# Sprite_Sail_1mx1m.net
KiCad netlist of a schematic drawn in EAGLE
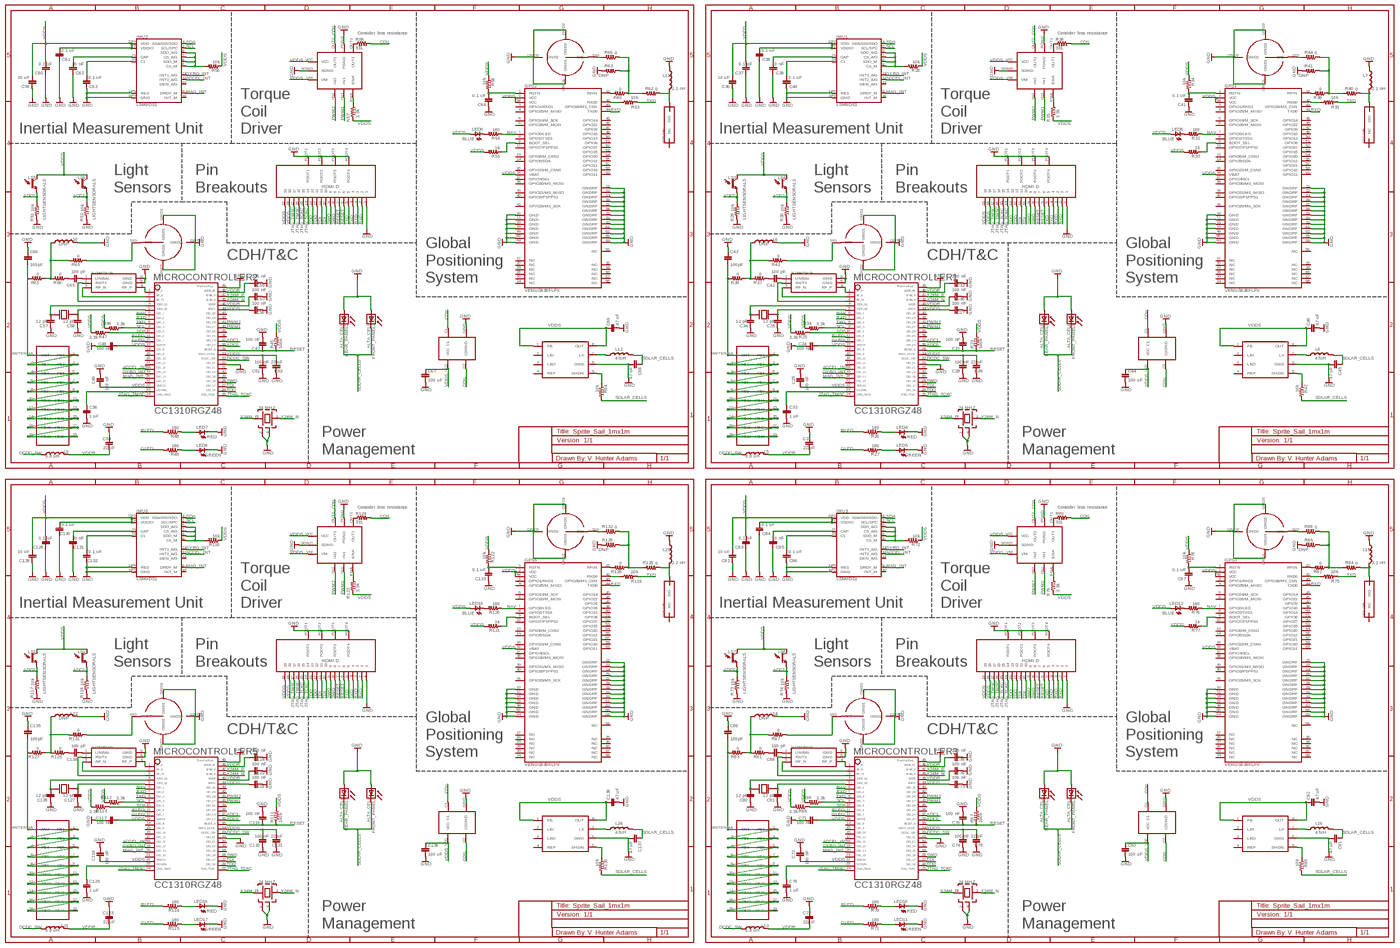
[diagram p0: schematic, sheet 1, overview]
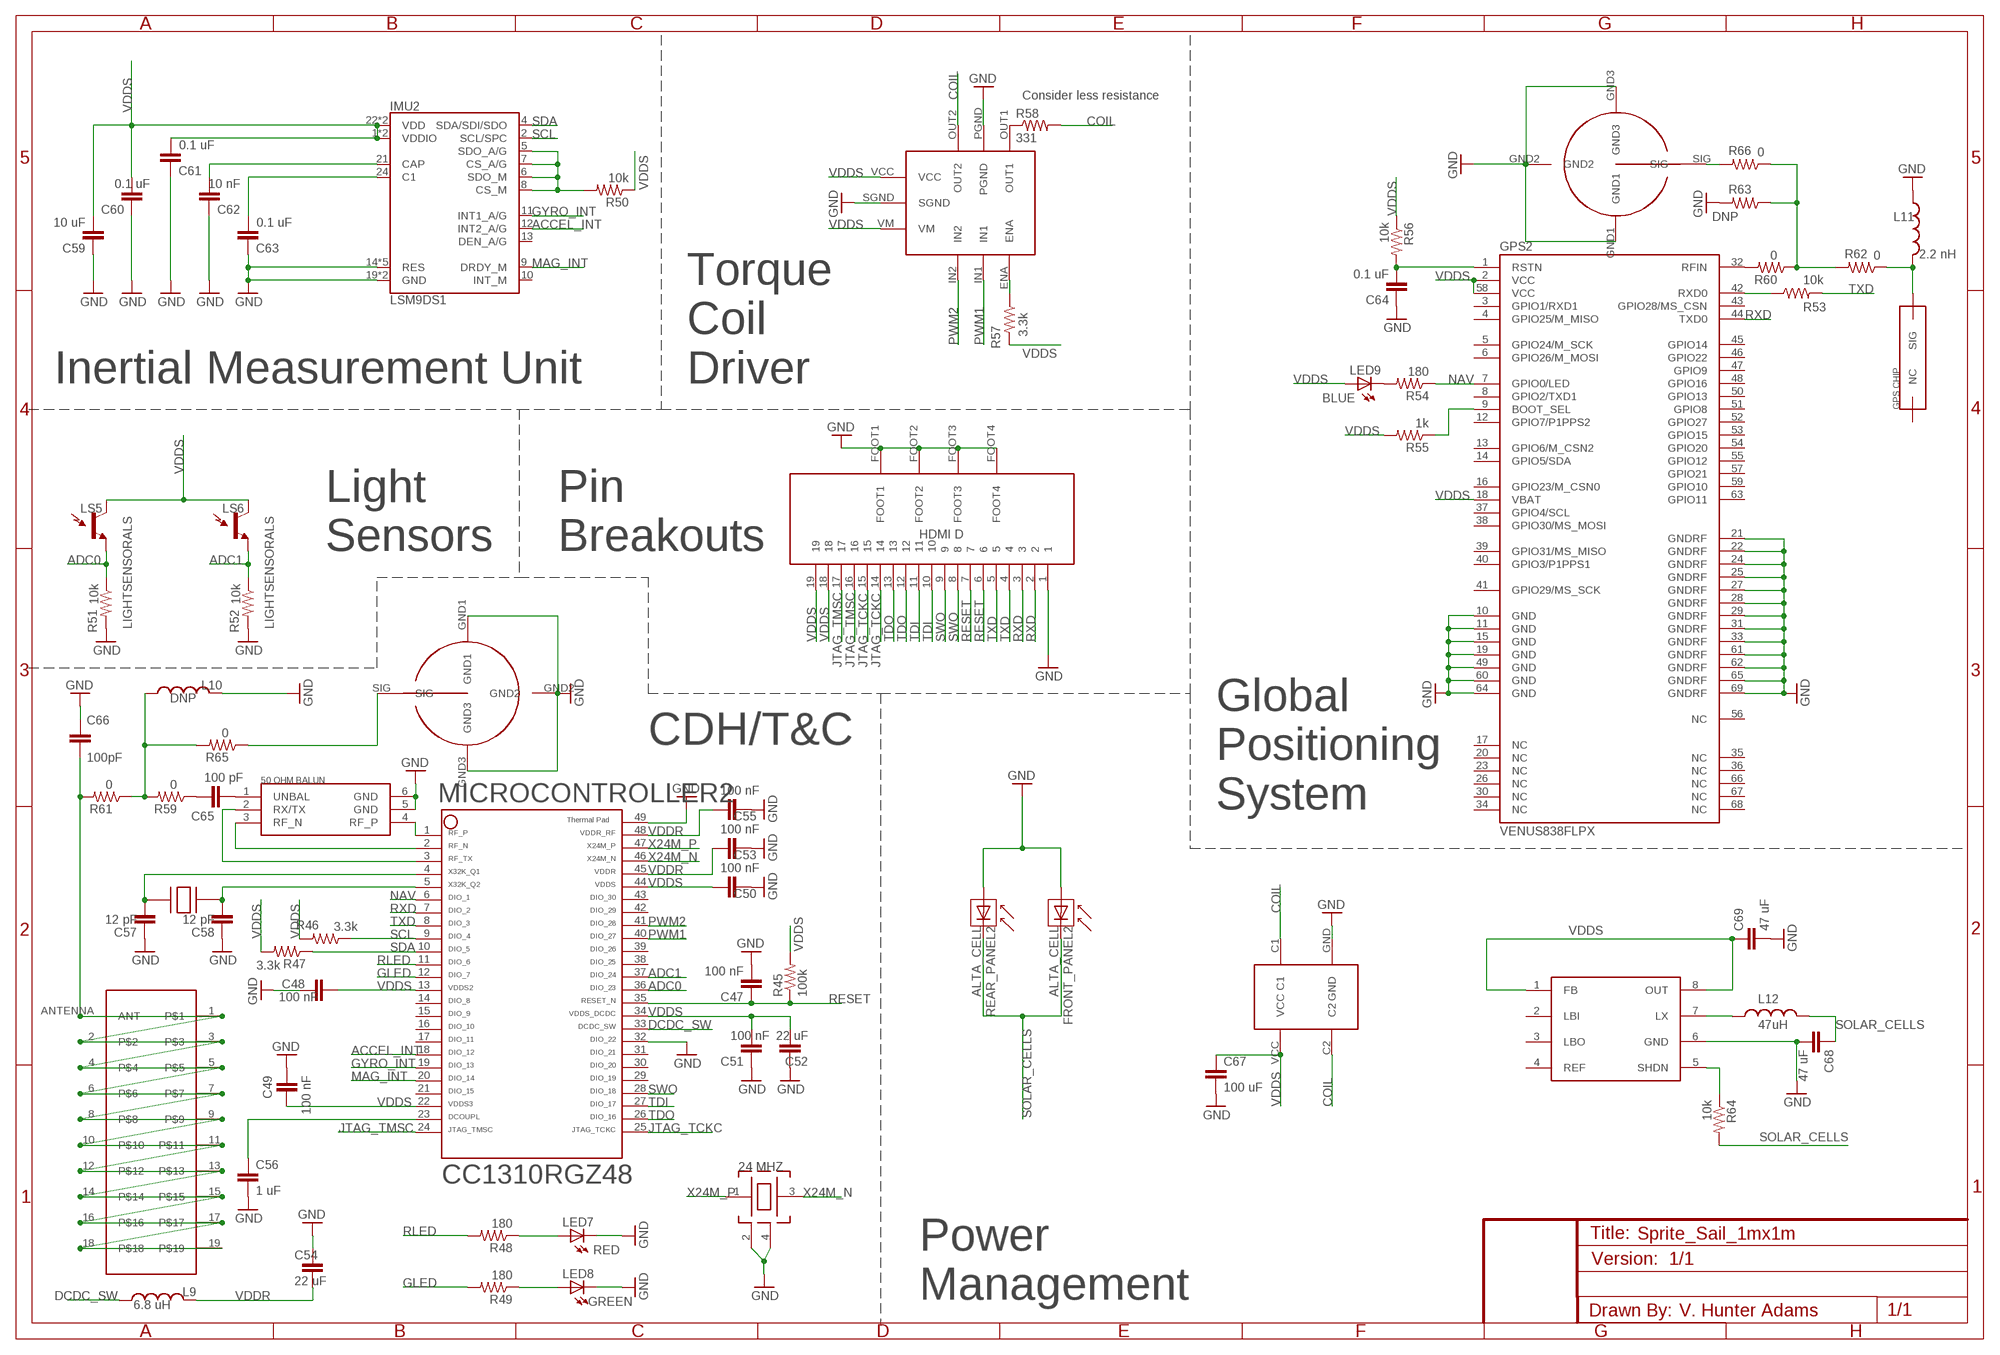
[diagram p1: schematic, sheet 1, part 1 of 4]
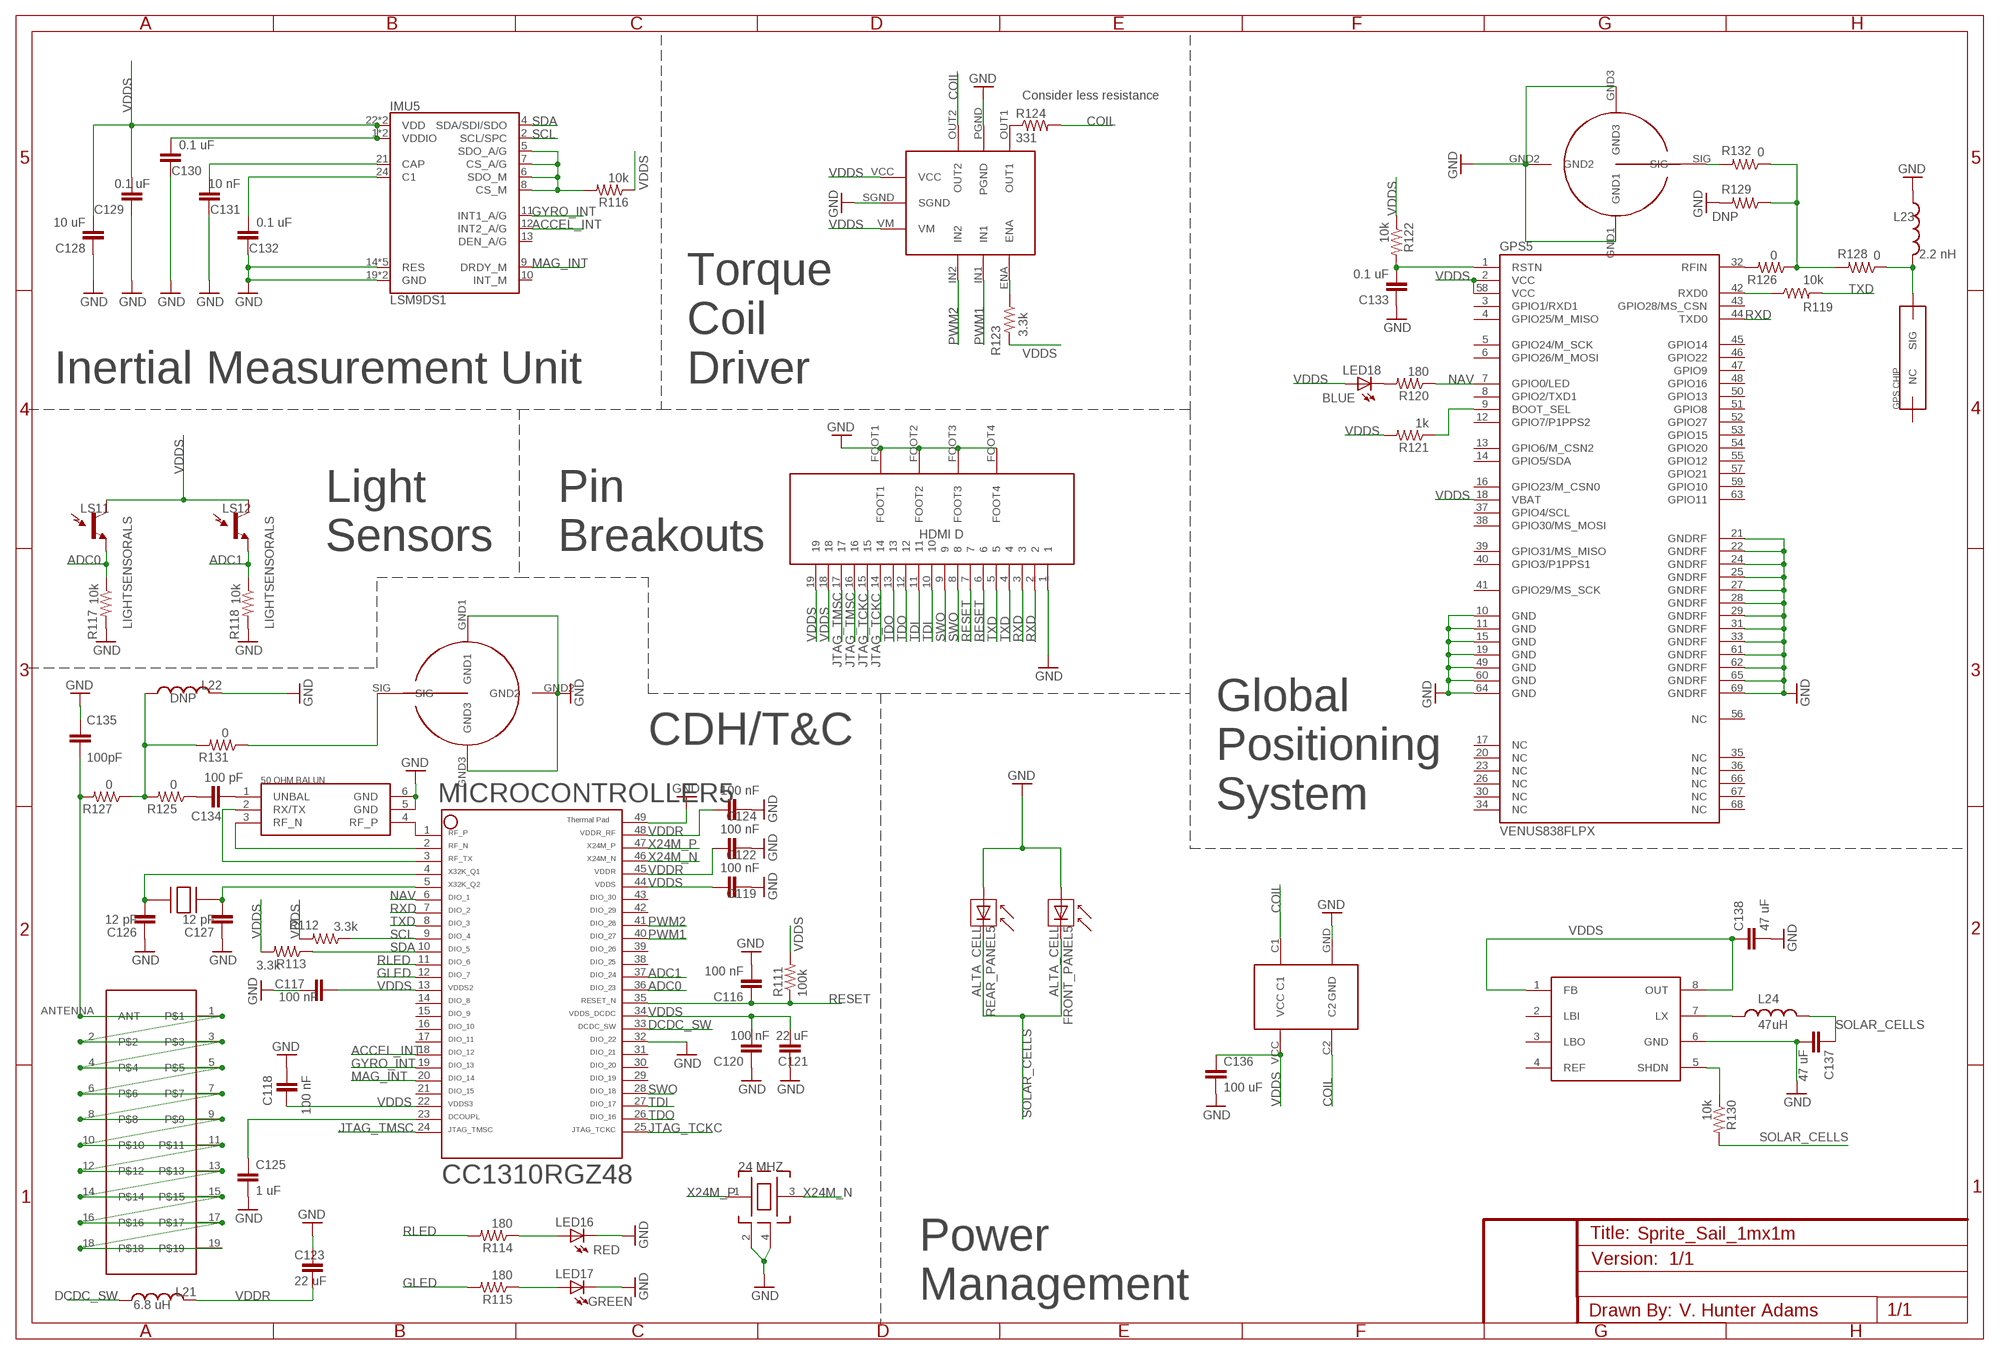
[diagram p2: schematic, sheet 1, part 2 of 4]
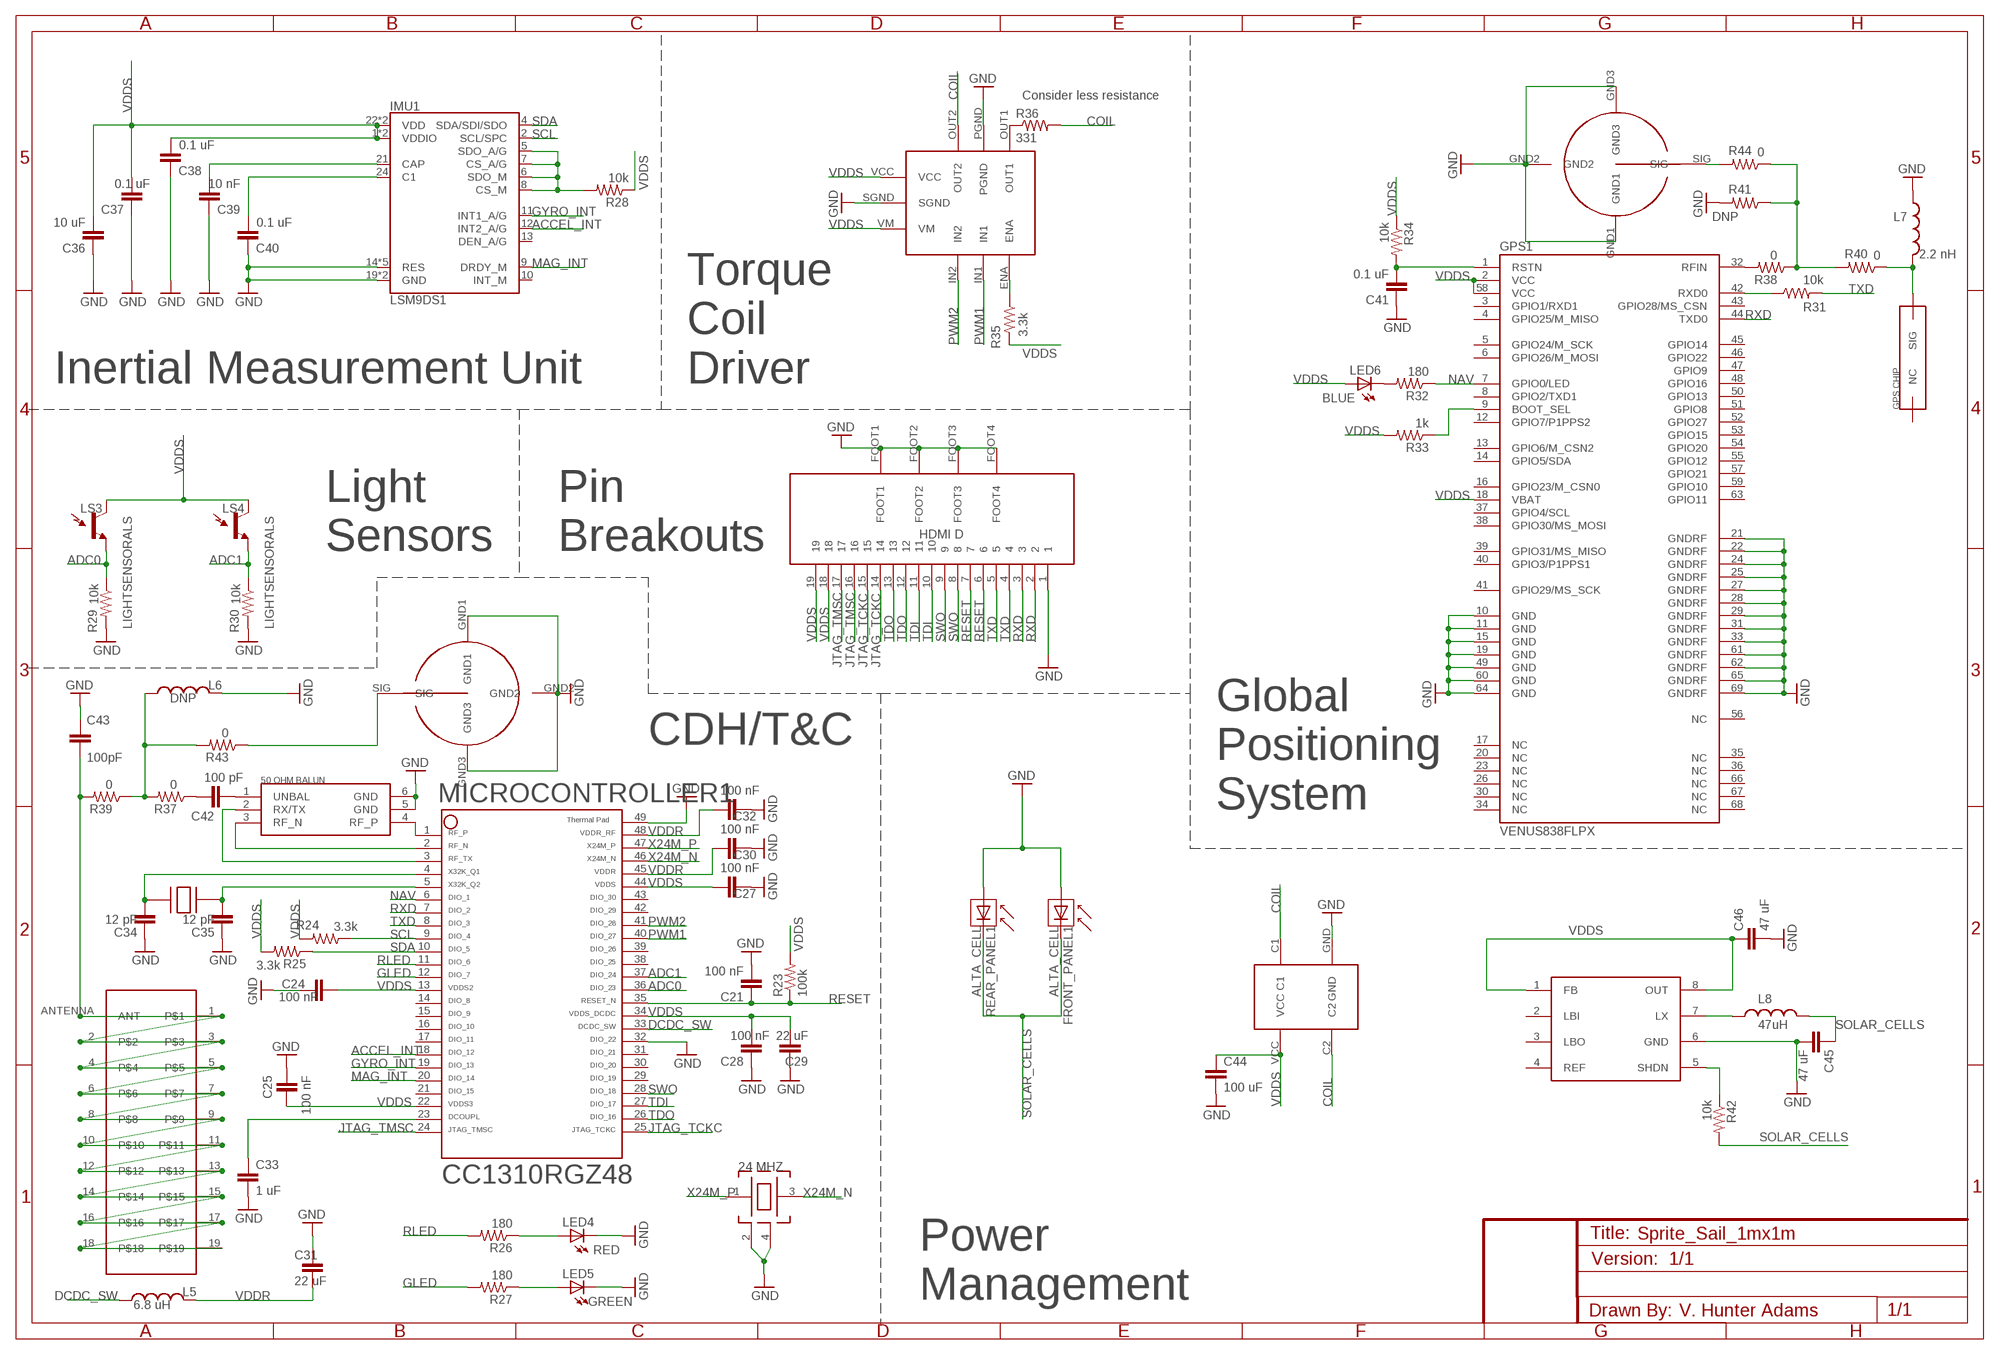
[diagram p3: schematic, sheet 1, part 3 of 4]
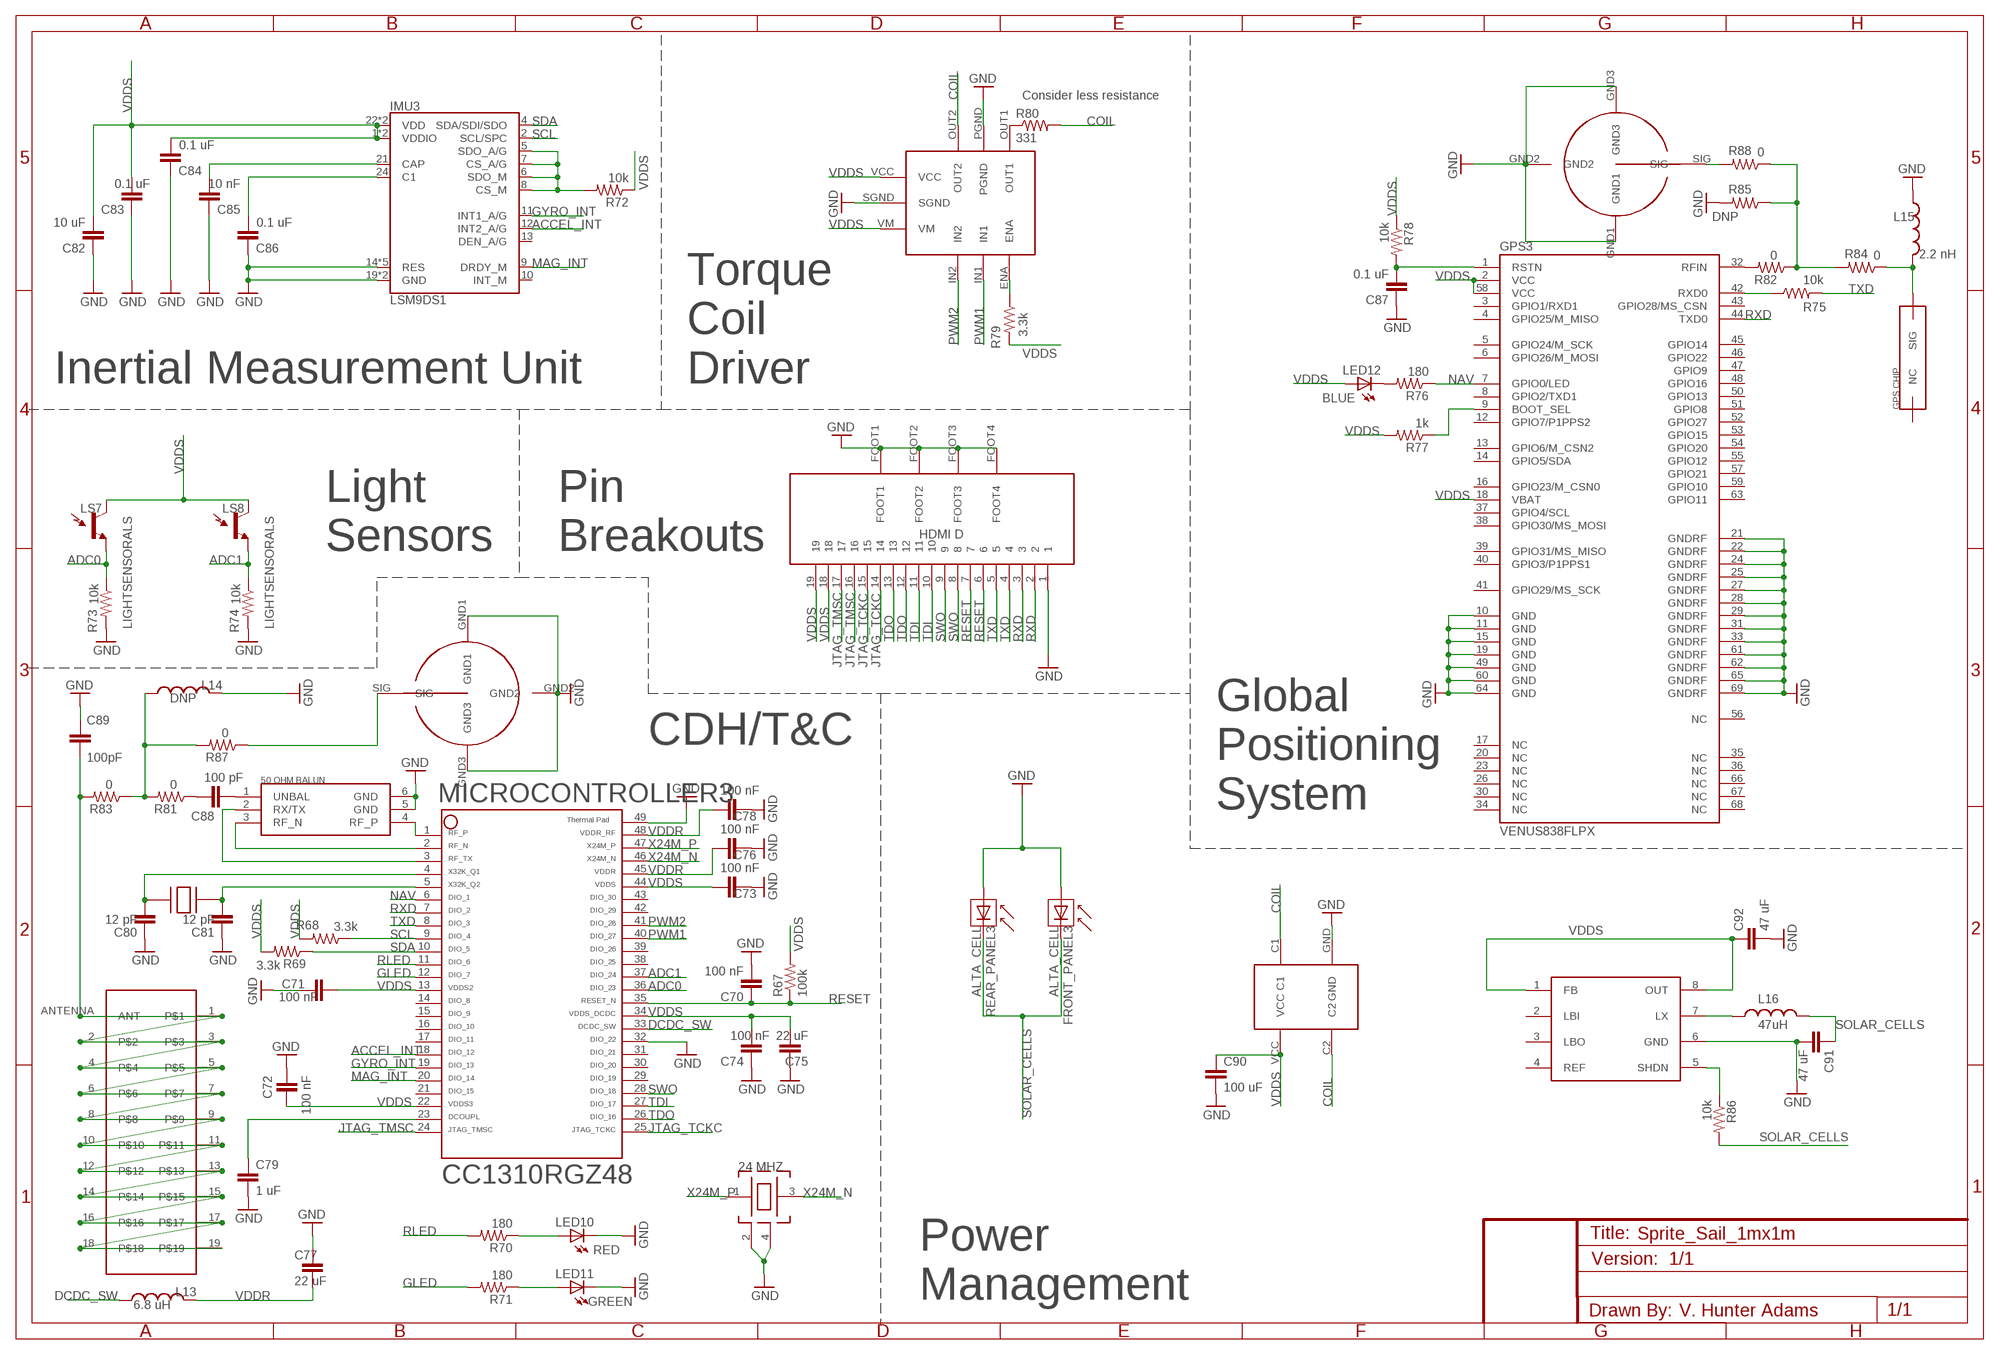
[diagram p4: schematic, sheet 1, part 4 of 4]

(export (version "E")
  (design (tool "Eeschema 10.0.6"))
  (components
    (comp (ref "32.1")
      (value "FC-135")
      (footprint "eagle-import:FC-135")
      (libsource (lib "eagle-import") (part "FC-135"))
    )
    (comp (ref "32.2")
      (value "FC-135")
      (footprint "eagle-import:FC-135")
      (libsource (lib "eagle-import") (part "FC-135"))
    )
    (comp (ref "32.3")
      (value "FC-135")
      (footprint "eagle-import:FC-135")
      (libsource (lib "eagle-import") (part "FC-135"))
    )
    (comp (ref "32.5")
      (value "FC-135")
      (footprint "eagle-import:FC-135")
      (libsource (lib "eagle-import") (part "FC-135"))
    )
    (comp (ref "BALUN1")
      (value "JOHANSON_BALUN")
      (footprint "eagle-import:JOHANSON_BALUN")
      (libsource (lib "eagle-import") (part "JOHANSON_BALUN"))
    )
    (comp (ref "BALUN2")
      (value "JOHANSON_BALUN")
      (footprint "eagle-import:JOHANSON_BALUN")
      (libsource (lib "eagle-import") (part "JOHANSON_BALUN"))
    )
    (comp (ref "BALUN3")
      (value "JOHANSON_BALUN")
      (footprint "eagle-import:JOHANSON_BALUN")
      (libsource (lib "eagle-import") (part "JOHANSON_BALUN"))
    )
    (comp (ref "BALUN5")
      (value "JOHANSON_BALUN")
      (footprint "eagle-import:JOHANSON_BALUN")
      (libsource (lib "eagle-import") (part "JOHANSON_BALUN"))
    )
    (comp (ref "C21")
      (value "100 nF")
      (footprint "eagle-import:0402-CAP")
      (libsource (lib "eagle-import") (part "CAP0402-CAP"))
    )
    (comp (ref "C24")
      (value "100 nF")
      (footprint "eagle-import:0402-CAP")
      (libsource (lib "eagle-import") (part "CAP0402-CAP"))
    )
    (comp (ref "C25")
      (value "100 nF")
      (footprint "eagle-import:0402-CAP")
      (libsource (lib "eagle-import") (part "CAP0402-CAP"))
    )
    (comp (ref "C27")
      (value "100 nF")
      (footprint "eagle-import:0402-CAP")
      (libsource (lib "eagle-import") (part "CAP0402-CAP"))
    )
    (comp (ref "C28")
      (value "100 nF")
      (footprint "eagle-import:0402-CAP")
      (libsource (lib "eagle-import") (part "CAP0402-CAP"))
    )
    (comp (ref "C29")
      (value "22 uF")
      (footprint "eagle-import:0402-CAP")
      (libsource (lib "eagle-import") (part "CAP0402-CAP"))
    )
    (comp (ref "C30")
      (value "100 nF")
      (footprint "eagle-import:0402-CAP")
      (libsource (lib "eagle-import") (part "CAP0402-CAP"))
    )
    (comp (ref "C31")
      (value "22 uF")
      (footprint "eagle-import:0402-CAP")
      (libsource (lib "eagle-import") (part "CAP0402-CAP"))
    )
    (comp (ref "C32")
      (value "100 nF")
      (footprint "eagle-import:0402-CAP")
      (libsource (lib "eagle-import") (part "CAP0402-CAP"))
    )
    (comp (ref "C33")
      (value "1 uF")
      (footprint "eagle-import:0402-CAP")
      (libsource (lib "eagle-import") (part "CAP0402-CAP"))
    )
    (comp (ref "C34")
      (value "12 pF")
      (footprint "eagle-import:0402-CAP")
      (libsource (lib "eagle-import") (part "CAP0402-CAP"))
    )
    (comp (ref "C35")
      (value "12 pF")
      (footprint "eagle-import:0402-CAP")
      (libsource (lib "eagle-import") (part "CAP0402-CAP"))
    )
    (comp (ref "C36")
      (value "10 uF")
      (footprint "eagle-import:0402-CAP")
      (libsource (lib "eagle-import") (part "CAP0402-CAP"))
    )
    (comp (ref "C37")
      (value "0.1 uF")
      (footprint "eagle-import:0402-CAP")
      (libsource (lib "eagle-import") (part "CAP0402-CAP"))
    )
    (comp (ref "C38")
      (value "0.1 uF")
      (footprint "eagle-import:0402-CAP")
      (libsource (lib "eagle-import") (part "CAP0402-CAP"))
    )
    (comp (ref "C39")
      (value "10 nF")
      (footprint "eagle-import:0402-CAP")
      (libsource (lib "eagle-import") (part "CAP0402-CAP"))
    )
    (comp (ref "C40")
      (value "0.1 uF")
      (footprint "eagle-import:0402-CAP")
      (libsource (lib "eagle-import") (part "CAP0402-CAP"))
    )
    (comp (ref "C41")
      (value "0.1 uF")
      (footprint "eagle-import:0402-CAP")
      (libsource (lib "eagle-import") (part "CAP0402-CAP"))
    )
    (comp (ref "C42")
      (value "100 pF")
      (footprint "eagle-import:0402-CAP")
      (libsource (lib "eagle-import") (part "CAP0402-CAP"))
    )
    (comp (ref "C43")
      (value "100pF")
      (footprint "eagle-import:0603-CAP")
      (libsource (lib "eagle-import") (part "CAP0603-CAP"))
    )
    (comp (ref "C44")
      (value "100 uF")
      (footprint "eagle-import:0805")
      (libsource (lib "eagle-import") (part "CAP0805"))
    )
    (comp (ref "C45")
      (value "47 uF")
      (footprint "eagle-import:0805")
      (libsource (lib "eagle-import") (part "CAP0805"))
    )
    (comp (ref "C46")
      (value "47 uF")
      (footprint "eagle-import:0805")
      (libsource (lib "eagle-import") (part "CAP0805"))
    )
    (comp (ref "C47")
      (value "100 nF")
      (footprint "eagle-import:0402-CAP")
      (libsource (lib "eagle-import") (part "CAP0402-CAP"))
    )
    (comp (ref "C48")
      (value "100 nF")
      (footprint "eagle-import:0402-CAP")
      (libsource (lib "eagle-import") (part "CAP0402-CAP"))
    )
    (comp (ref "C49")
      (value "100 nF")
      (footprint "eagle-import:0402-CAP")
      (libsource (lib "eagle-import") (part "CAP0402-CAP"))
    )
    (comp (ref "C50")
      (value "100 nF")
      (footprint "eagle-import:0402-CAP")
      (libsource (lib "eagle-import") (part "CAP0402-CAP"))
    )
    (comp (ref "C51")
      (value "100 nF")
      (footprint "eagle-import:0402-CAP")
      (libsource (lib "eagle-import") (part "CAP0402-CAP"))
    )
    (comp (ref "C52")
      (value "22 uF")
      (footprint "eagle-import:0402-CAP")
      (libsource (lib "eagle-import") (part "CAP0402-CAP"))
    )
    (comp (ref "C53")
      (value "100 nF")
      (footprint "eagle-import:0402-CAP")
      (libsource (lib "eagle-import") (part "CAP0402-CAP"))
    )
    (comp (ref "C54")
      (value "22 uF")
      (footprint "eagle-import:0402-CAP")
      (libsource (lib "eagle-import") (part "CAP0402-CAP"))
    )
    (comp (ref "C55")
      (value "100 nF")
      (footprint "eagle-import:0402-CAP")
      (libsource (lib "eagle-import") (part "CAP0402-CAP"))
    )
    (comp (ref "C56")
      (value "1 uF")
      (footprint "eagle-import:0402-CAP")
      (libsource (lib "eagle-import") (part "CAP0402-CAP"))
    )
    (comp (ref "C57")
      (value "12 pF")
      (footprint "eagle-import:0402-CAP")
      (libsource (lib "eagle-import") (part "CAP0402-CAP"))
    )
    (comp (ref "C58")
      (value "12 pF")
      (footprint "eagle-import:0402-CAP")
      (libsource (lib "eagle-import") (part "CAP0402-CAP"))
    )
    (comp (ref "C59")
      (value "10 uF")
      (footprint "eagle-import:0402-CAP")
      (libsource (lib "eagle-import") (part "CAP0402-CAP"))
    )
    (comp (ref "C60")
      (value "0.1 uF")
      (footprint "eagle-import:0402-CAP")
      (libsource (lib "eagle-import") (part "CAP0402-CAP"))
    )
    (comp (ref "C61")
      (value "0.1 uF")
      (footprint "eagle-import:0402-CAP")
      (libsource (lib "eagle-import") (part "CAP0402-CAP"))
    )
    (comp (ref "C62")
      (value "10 nF")
      (footprint "eagle-import:0402-CAP")
      (libsource (lib "eagle-import") (part "CAP0402-CAP"))
    )
    (comp (ref "C63")
      (value "0.1 uF")
      (footprint "eagle-import:0402-CAP")
      (libsource (lib "eagle-import") (part "CAP0402-CAP"))
    )
    (comp (ref "C64")
      (value "0.1 uF")
      (footprint "eagle-import:0402-CAP")
      (libsource (lib "eagle-import") (part "CAP0402-CAP"))
    )
    (comp (ref "C65")
      (value "100 pF")
      (footprint "eagle-import:0402-CAP")
      (libsource (lib "eagle-import") (part "CAP0402-CAP"))
    )
    (comp (ref "C66")
      (value "100pF")
      (footprint "eagle-import:0603-CAP")
      (libsource (lib "eagle-import") (part "CAP0603-CAP"))
    )
    (comp (ref "C67")
      (value "100 uF")
      (footprint "eagle-import:0805")
      (libsource (lib "eagle-import") (part "CAP0805"))
    )
    (comp (ref "C68")
      (value "47 uF")
      (footprint "eagle-import:0805")
      (libsource (lib "eagle-import") (part "CAP0805"))
    )
    (comp (ref "C69")
      (value "47 uF")
      (footprint "eagle-import:0805")
      (libsource (lib "eagle-import") (part "CAP0805"))
    )
    (comp (ref "C70")
      (value "100 nF")
      (footprint "eagle-import:0402-CAP")
      (libsource (lib "eagle-import") (part "CAP0402-CAP"))
    )
    (comp (ref "C71")
      (value "100 nF")
      (footprint "eagle-import:0402-CAP")
      (libsource (lib "eagle-import") (part "CAP0402-CAP"))
    )
    (comp (ref "C72")
      (value "100 nF")
      (footprint "eagle-import:0402-CAP")
      (libsource (lib "eagle-import") (part "CAP0402-CAP"))
    )
    (comp (ref "C73")
      (value "100 nF")
      (footprint "eagle-import:0402-CAP")
      (libsource (lib "eagle-import") (part "CAP0402-CAP"))
    )
    (comp (ref "C74")
      (value "100 nF")
      (footprint "eagle-import:0402-CAP")
      (libsource (lib "eagle-import") (part "CAP0402-CAP"))
    )
    (comp (ref "C75")
      (value "22 uF")
      (footprint "eagle-import:0402-CAP")
      (libsource (lib "eagle-import") (part "CAP0402-CAP"))
    )
    (comp (ref "C76")
      (value "100 nF")
      (footprint "eagle-import:0402-CAP")
      (libsource (lib "eagle-import") (part "CAP0402-CAP"))
    )
    (comp (ref "C77")
      (value "22 uF")
      (footprint "eagle-import:0402-CAP")
      (libsource (lib "eagle-import") (part "CAP0402-CAP"))
    )
    (comp (ref "C78")
      (value "100 nF")
      (footprint "eagle-import:0402-CAP")
      (libsource (lib "eagle-import") (part "CAP0402-CAP"))
    )
    (comp (ref "C79")
      (value "1 uF")
      (footprint "eagle-import:0402-CAP")
      (libsource (lib "eagle-import") (part "CAP0402-CAP"))
    )
    (comp (ref "C80")
      (value "12 pF")
      (footprint "eagle-import:0402-CAP")
      (libsource (lib "eagle-import") (part "CAP0402-CAP"))
    )
    (comp (ref "C81")
      (value "12 pF")
      (footprint "eagle-import:0402-CAP")
      (libsource (lib "eagle-import") (part "CAP0402-CAP"))
    )
    (comp (ref "C82")
      (value "10 uF")
      (footprint "eagle-import:0402-CAP")
      (libsource (lib "eagle-import") (part "CAP0402-CAP"))
    )
    (comp (ref "C83")
      (value "0.1 uF")
      (footprint "eagle-import:0402-CAP")
      (libsource (lib "eagle-import") (part "CAP0402-CAP"))
    )
    (comp (ref "C84")
      (value "0.1 uF")
      (footprint "eagle-import:0402-CAP")
      (libsource (lib "eagle-import") (part "CAP0402-CAP"))
    )
    (comp (ref "C85")
      (value "10 nF")
      (footprint "eagle-import:0402-CAP")
      (libsource (lib "eagle-import") (part "CAP0402-CAP"))
    )
    (comp (ref "C86")
      (value "0.1 uF")
      (footprint "eagle-import:0402-CAP")
      (libsource (lib "eagle-import") (part "CAP0402-CAP"))
    )
    (comp (ref "C87")
      (value "0.1 uF")
      (footprint "eagle-import:0402-CAP")
      (libsource (lib "eagle-import") (part "CAP0402-CAP"))
    )
    (comp (ref "C88")
      (value "100 pF")
      (footprint "eagle-import:0402-CAP")
      (libsource (lib "eagle-import") (part "CAP0402-CAP"))
    )
    (comp (ref "C89")
      (value "100pF")
      (footprint "eagle-import:0603-CAP")
      (libsource (lib "eagle-import") (part "CAP0603-CAP"))
    )
    (comp (ref "C90")
      (value "100 uF")
      (footprint "eagle-import:0805")
      (libsource (lib "eagle-import") (part "CAP0805"))
    )
    (comp (ref "C91")
      (value "47 uF")
      (footprint "eagle-import:0805")
      (libsource (lib "eagle-import") (part "CAP0805"))
    )
    (comp (ref "C92")
      (value "47 uF")
      (footprint "eagle-import:0805")
      (libsource (lib "eagle-import") (part "CAP0805"))
    )
    (comp (ref "C116")
      (value "100 nF")
      (footprint "eagle-import:0402-CAP")
      (libsource (lib "eagle-import") (part "CAP0402-CAP"))
    )
    (comp (ref "C117")
      (value "100 nF")
      (footprint "eagle-import:0402-CAP")
      (libsource (lib "eagle-import") (part "CAP0402-CAP"))
    )
    (comp (ref "C118")
      (value "100 nF")
      (footprint "eagle-import:0402-CAP")
      (libsource (lib "eagle-import") (part "CAP0402-CAP"))
    )
    (comp (ref "C119")
      (value "100 nF")
      (footprint "eagle-import:0402-CAP")
      (libsource (lib "eagle-import") (part "CAP0402-CAP"))
    )
    (comp (ref "C120")
      (value "100 nF")
      (footprint "eagle-import:0402-CAP")
      (libsource (lib "eagle-import") (part "CAP0402-CAP"))
    )
    (comp (ref "C121")
      (value "22 uF")
      (footprint "eagle-import:0402-CAP")
      (libsource (lib "eagle-import") (part "CAP0402-CAP"))
    )
    (comp (ref "C122")
      (value "100 nF")
      (footprint "eagle-import:0402-CAP")
      (libsource (lib "eagle-import") (part "CAP0402-CAP"))
    )
    (comp (ref "C123")
      (value "22 uF")
      (footprint "eagle-import:0402-CAP")
      (libsource (lib "eagle-import") (part "CAP0402-CAP"))
    )
    (comp (ref "C124")
      (value "100 nF")
      (footprint "eagle-import:0402-CAP")
      (libsource (lib "eagle-import") (part "CAP0402-CAP"))
    )
    (comp (ref "C125")
      (value "1 uF")
      (footprint "eagle-import:0402-CAP")
      (libsource (lib "eagle-import") (part "CAP0402-CAP"))
    )
    (comp (ref "C126")
      (value "12 pF")
      (footprint "eagle-import:0402-CAP")
      (libsource (lib "eagle-import") (part "CAP0402-CAP"))
    )
    (comp (ref "C127")
      (value "12 pF")
      (footprint "eagle-import:0402-CAP")
      (libsource (lib "eagle-import") (part "CAP0402-CAP"))
    )
    (comp (ref "C128")
      (value "10 uF")
      (footprint "eagle-import:0402-CAP")
      (libsource (lib "eagle-import") (part "CAP0402-CAP"))
    )
    (comp (ref "C129")
      (value "0.1 uF")
      (footprint "eagle-import:0402-CAP")
      (libsource (lib "eagle-import") (part "CAP0402-CAP"))
    )
    (comp (ref "C130")
      (value "0.1 uF")
      (footprint "eagle-import:0402-CAP")
      (libsource (lib "eagle-import") (part "CAP0402-CAP"))
    )
    (comp (ref "C131")
      (value "10 nF")
      (footprint "eagle-import:0402-CAP")
      (libsource (lib "eagle-import") (part "CAP0402-CAP"))
    )
    (comp (ref "C132")
      (value "0.1 uF")
      (footprint "eagle-import:0402-CAP")
      (libsource (lib "eagle-import") (part "CAP0402-CAP"))
    )
    (comp (ref "C133")
      (value "0.1 uF")
      (footprint "eagle-import:0402-CAP")
      (libsource (lib "eagle-import") (part "CAP0402-CAP"))
    )
    (comp (ref "C134")
      (value "100 pF")
      (footprint "eagle-import:0402-CAP")
      (libsource (lib "eagle-import") (part "CAP0402-CAP"))
    )
    (comp (ref "C135")
      (value "100pF")
      (footprint "eagle-import:0603-CAP")
      (libsource (lib "eagle-import") (part "CAP0603-CAP"))
    )
    (comp (ref "C136")
      (value "100 uF")
      (footprint "eagle-import:0805")
      (libsource (lib "eagle-import") (part "CAP0805"))
    )
    (comp (ref "C137")
      (value "47 uF")
      (footprint "eagle-import:0805")
      (libsource (lib "eagle-import") (part "CAP0805"))
    )
    (comp (ref "C138")
      (value "47 uF")
      (footprint "eagle-import:0805")
      (libsource (lib "eagle-import") (part "CAP0805"))
    )
    (comp (ref "FRONT_PANEL1")
      (value "ALTA_CELL")
      (footprint "eagle-import:ALTA_CELL")
      (libsource (lib "eagle-import") (part "ALTA_CELL"))
    )
    (comp (ref "FRONT_PANEL2")
      (value "ALTA_CELL")
      (footprint "eagle-import:ALTA_CELL")
      (libsource (lib "eagle-import") (part "ALTA_CELL"))
    )
    (comp (ref "FRONT_PANEL3")
      (value "ALTA_CELL")
      (footprint "eagle-import:ALTA_CELL")
      (libsource (lib "eagle-import") (part "ALTA_CELL"))
    )
    (comp (ref "FRONT_PANEL5")
      (value "ALTA_CELL")
      (footprint "eagle-import:ALTA_CELL")
      (libsource (lib "eagle-import") (part "ALTA_CELL"))
    )
    (comp (ref "GPS1")
      (value "VENUS838FLPX")
      (footprint "eagle-import:VENUS838FLPX")
      (libsource (lib "eagle-import") (part "VENUS838FLPX"))
    )
    (comp (ref "GPS2")
      (value "VENUS838FLPX")
      (footprint "eagle-import:VENUS838FLPX")
      (libsource (lib "eagle-import") (part "VENUS838FLPX"))
    )
    (comp (ref "GPS3")
      (value "VENUS838FLPX")
      (footprint "eagle-import:VENUS838FLPX")
      (libsource (lib "eagle-import") (part "VENUS838FLPX"))
    )
    (comp (ref "GPS5")
      (value "VENUS838FLPX")
      (footprint "eagle-import:VENUS838FLPX")
      (libsource (lib "eagle-import") (part "VENUS838FLPX"))
    )
    (comp (ref "IMU1")
      (value "LSM9DS1")
      (footprint "eagle-import:LGA24-8X4")
      (libsource (lib "eagle-import") (part "LSM9DS1"))
    )
    (comp (ref "IMU2")
      (value "LSM9DS1")
      (footprint "eagle-import:LGA24-8X4")
      (libsource (lib "eagle-import") (part "LSM9DS1"))
    )
    (comp (ref "IMU3")
      (value "LSM9DS1")
      (footprint "eagle-import:LGA24-8X4")
      (libsource (lib "eagle-import") (part "LSM9DS1"))
    )
    (comp (ref "IMU5")
      (value "LSM9DS1")
      (footprint "eagle-import:LGA24-8X4")
      (libsource (lib "eagle-import") (part "LSM9DS1"))
    )
    (comp (ref "L5")
      (value "6.8 uH")
      (footprint "eagle-import:0603")
      (libsource (lib "eagle-import") (part "INDUCTOR0603"))
    )
    (comp (ref "L6")
      (value "DNP")
      (footprint "eagle-import:0603")
      (libsource (lib "eagle-import") (part "INDUCTOR0603"))
    )
    (comp (ref "L7")
      (value "2.2 nH")
      (footprint "eagle-import:0603")
      (libsource (lib "eagle-import") (part "INDUCTOR0603"))
    )
    (comp (ref "L8")
      (value "47uH")
      (footprint "eagle-import:0603")
      (libsource (lib "eagle-import") (part "INDUCTOR0603"))
    )
    (comp (ref "L9")
      (value "6.8 uH")
      (footprint "eagle-import:0603")
      (libsource (lib "eagle-import") (part "INDUCTOR0603"))
    )
    (comp (ref "L10")
      (value "DNP")
      (footprint "eagle-import:0603")
      (libsource (lib "eagle-import") (part "INDUCTOR0603"))
    )
    (comp (ref "L11")
      (value "2.2 nH")
      (footprint "eagle-import:0603")
      (libsource (lib "eagle-import") (part "INDUCTOR0603"))
    )
    (comp (ref "L12")
      (value "47uH")
      (footprint "eagle-import:0603")
      (libsource (lib "eagle-import") (part "INDUCTOR0603"))
    )
    (comp (ref "L13")
      (value "6.8 uH")
      (footprint "eagle-import:0603")
      (libsource (lib "eagle-import") (part "INDUCTOR0603"))
    )
    (comp (ref "L14")
      (value "DNP")
      (footprint "eagle-import:0603")
      (libsource (lib "eagle-import") (part "INDUCTOR0603"))
    )
    (comp (ref "L15")
      (value "2.2 nH")
      (footprint "eagle-import:0603")
      (libsource (lib "eagle-import") (part "INDUCTOR0603"))
    )
    (comp (ref "L16")
      (value "47uH")
      (footprint "eagle-import:0603")
      (libsource (lib "eagle-import") (part "INDUCTOR0603"))
    )
    (comp (ref "L21")
      (value "6.8 uH")
      (footprint "eagle-import:0603")
      (libsource (lib "eagle-import") (part "INDUCTOR0603"))
    )
    (comp (ref "L22")
      (value "DNP")
      (footprint "eagle-import:0603")
      (libsource (lib "eagle-import") (part "INDUCTOR0603"))
    )
    (comp (ref "L23")
      (value "2.2 nH")
      (footprint "eagle-import:0603")
      (libsource (lib "eagle-import") (part "INDUCTOR0603"))
    )
    (comp (ref "L24")
      (value "47uH")
      (footprint "eagle-import:0603")
      (libsource (lib "eagle-import") (part "INDUCTOR0603"))
    )
    (comp (ref "LED4")
      (value "RED")
      (footprint "eagle-import:LED-0603")
      (libsource (lib "eagle-import") (part "LED0603"))
    )
    (comp (ref "LED5")
      (value "GREEN")
      (footprint "eagle-import:LED-0603")
      (libsource (lib "eagle-import") (part "LED0603"))
    )
    (comp (ref "LED6")
      (value "BLUE")
      (footprint "eagle-import:LED-0603")
      (libsource (lib "eagle-import") (part "LED0603"))
    )
    (comp (ref "LED7")
      (value "RED")
      (footprint "eagle-import:LED-0603")
      (libsource (lib "eagle-import") (part "LED0603"))
    )
    (comp (ref "LED8")
      (value "GREEN")
      (footprint "eagle-import:LED-0603")
      (libsource (lib "eagle-import") (part "LED0603"))
    )
    (comp (ref "LED9")
      (value "BLUE")
      (footprint "eagle-import:LED-0603")
      (libsource (lib "eagle-import") (part "LED0603"))
    )
    (comp (ref "LED10")
      (value "RED")
      (footprint "eagle-import:LED-0603")
      (libsource (lib "eagle-import") (part "LED0603"))
    )
    (comp (ref "LED11")
      (value "GREEN")
      (footprint "eagle-import:LED-0603")
      (libsource (lib "eagle-import") (part "LED0603"))
    )
    (comp (ref "LED12")
      (value "BLUE")
      (footprint "eagle-import:LED-0603")
      (libsource (lib "eagle-import") (part "LED0603"))
    )
    (comp (ref "LED16")
      (value "RED")
      (footprint "eagle-import:LED-0603")
      (libsource (lib "eagle-import") (part "LED0603"))
    )
    (comp (ref "LED17")
      (value "GREEN")
      (footprint "eagle-import:LED-0603")
      (libsource (lib "eagle-import") (part "LED0603"))
    )
    (comp (ref "LED18")
      (value "BLUE")
      (footprint "eagle-import:LED-0603")
      (libsource (lib "eagle-import") (part "LED0603"))
    )
    (comp (ref "LS3")
      (value "LIGHTSENSORALS")
      (footprint "eagle-import:ALS-PT19")
      (libsource (lib "eagle-import") (part "LIGHTSENSORALS"))
    )
    (comp (ref "LS4")
      (value "LIGHTSENSORALS")
      (footprint "eagle-import:ALS-PT19")
      (libsource (lib "eagle-import") (part "LIGHTSENSORALS"))
    )
    (comp (ref "LS5")
      (value "LIGHTSENSORALS")
      (footprint "eagle-import:ALS-PT19")
      (libsource (lib "eagle-import") (part "LIGHTSENSORALS"))
    )
    (comp (ref "LS6")
      (value "LIGHTSENSORALS")
      (footprint "eagle-import:ALS-PT19")
      (libsource (lib "eagle-import") (part "LIGHTSENSORALS"))
    )
    (comp (ref "LS7")
      (value "LIGHTSENSORALS")
      (footprint "eagle-import:ALS-PT19")
      (libsource (lib "eagle-import") (part "LIGHTSENSORALS"))
    )
    (comp (ref "LS8")
      (value "LIGHTSENSORALS")
      (footprint "eagle-import:ALS-PT19")
      (libsource (lib "eagle-import") (part "LIGHTSENSORALS"))
    )
    (comp (ref "LS11")
      (value "LIGHTSENSORALS")
      (footprint "eagle-import:ALS-PT19")
      (libsource (lib "eagle-import") (part "LIGHTSENSORALS"))
    )
    (comp (ref "LS12")
      (value "LIGHTSENSORALS")
      (footprint "eagle-import:ALS-PT19")
      (libsource (lib "eagle-import") (part "LIGHTSENSORALS"))
    )
    (comp (ref "MICROCONTROLLER1")
      (value "CC1310")
      (footprint "eagle-import:CC1310")
      (libsource (lib "eagle-import") (part "CC1310"))
    )
    (comp (ref "MICROCONTROLLER2")
      (value "CC1310")
      (footprint "eagle-import:CC1310")
      (libsource (lib "eagle-import") (part "CC1310"))
    )
    (comp (ref "MICROCONTROLLER3")
      (value "CC1310")
      (footprint "eagle-import:CC1310")
      (libsource (lib "eagle-import") (part "CC1310"))
    )
    (comp (ref "MICROCONTROLLER5")
      (value "CC1310")
      (footprint "eagle-import:CC1310")
      (libsource (lib "eagle-import") (part "CC1310"))
    )
    (comp (ref "R23")
      (value "100k")
      (footprint "eagle-import:0402-RES")
      (libsource (lib "eagle-import") (part "RESISTOR0402-RES"))
    )
    (comp (ref "R24")
      (value "3.3k")
      (footprint "eagle-import:0402-RES")
      (libsource (lib "eagle-import") (part "RESISTOR0402-RES"))
    )
    (comp (ref "R25")
      (value "3.3k")
      (footprint "eagle-import:0402-RES")
      (libsource (lib "eagle-import") (part "RESISTOR0402-RES"))
    )
    (comp (ref "R26")
      (value "180")
      (footprint "eagle-import:0402-RES")
      (libsource (lib "eagle-import") (part "RESISTOR0402-RES"))
    )
    (comp (ref "R27")
      (value "180")
      (footprint "eagle-import:0402-RES")
      (libsource (lib "eagle-import") (part "RESISTOR0402-RES"))
    )
    (comp (ref "R28")
      (value "10k")
      (footprint "eagle-import:0402-RES")
      (libsource (lib "eagle-import") (part "RESISTOR0402-RES"))
    )
    (comp (ref "R29")
      (value "10k")
      (footprint "eagle-import:0402-RES")
      (libsource (lib "eagle-import") (part "RESISTOR0402-RES"))
    )
    (comp (ref "R30")
      (value "10k")
      (footprint "eagle-import:0402-RES")
      (libsource (lib "eagle-import") (part "RESISTOR0402-RES"))
    )
    (comp (ref "R31")
      (value "10k")
      (footprint "eagle-import:0402-RES")
      (libsource (lib "eagle-import") (part "RESISTOR0402-RES"))
    )
    (comp (ref "R32")
      (value "180")
      (footprint "eagle-import:0402-RES")
      (libsource (lib "eagle-import") (part "RESISTOR0402-RES"))
    )
    (comp (ref "R33")
      (value "1k")
      (footprint "eagle-import:0402-RES")
      (libsource (lib "eagle-import") (part "RESISTOR0402-RES"))
    )
    (comp (ref "R34")
      (value "10k")
      (footprint "eagle-import:0402-RES")
      (libsource (lib "eagle-import") (part "RESISTOR0402-RES"))
    )
    (comp (ref "R35")
      (value "3.3k")
      (footprint "eagle-import:0402-RES")
      (libsource (lib "eagle-import") (part "RESISTOR0402-RES"))
    )
    (comp (ref "R36")
      (value "331")
      (footprint "eagle-import:0402-RES")
      (libsource (lib "eagle-import") (part "RESISTOR0402-RES"))
    )
    (comp (ref "R37")
      (value "0")
      (footprint "eagle-import:0603-RES")
      (libsource (lib "eagle-import") (part "RESISTOR0603-RES"))
    )
    (comp (ref "R38")
      (value "0")
      (footprint "eagle-import:0603-RES")
      (libsource (lib "eagle-import") (part "RESISTOR0603-RES"))
    )
    (comp (ref "R39")
      (value "0")
      (footprint "eagle-import:0603-RES")
      (libsource (lib "eagle-import") (part "RESISTOR0603-RES"))
    )
    (comp (ref "R40")
      (value "0")
      (footprint "eagle-import:0603-RES")
      (libsource (lib "eagle-import") (part "RESISTOR0603-RES"))
    )
    (comp (ref "R41")
      (value "DNP")
      (footprint "eagle-import:0603-RES")
      (libsource (lib "eagle-import") (part "RESISTOR0603-RES"))
    )
    (comp (ref "R42")
      (value "10k")
      (footprint "eagle-import:0402-RES")
      (libsource (lib "eagle-import") (part "RESISTOR0402-RES"))
    )
    (comp (ref "R43")
      (value "0")
      (footprint "eagle-import:0603-RES")
      (libsource (lib "eagle-import") (part "RESISTOR0603-RES"))
    )
    (comp (ref "R44")
      (value "0")
      (footprint "eagle-import:0603-RES")
      (libsource (lib "eagle-import") (part "RESISTOR0603-RES"))
    )
    (comp (ref "R45")
      (value "100k")
      (footprint "eagle-import:0402-RES")
      (libsource (lib "eagle-import") (part "RESISTOR0402-RES"))
    )
    (comp (ref "R46")
      (value "3.3k")
      (footprint "eagle-import:0402-RES")
      (libsource (lib "eagle-import") (part "RESISTOR0402-RES"))
    )
    (comp (ref "R47")
      (value "3.3k")
      (footprint "eagle-import:0402-RES")
      (libsource (lib "eagle-import") (part "RESISTOR0402-RES"))
    )
    (comp (ref "R48")
      (value "180")
      (footprint "eagle-import:0402-RES")
      (libsource (lib "eagle-import") (part "RESISTOR0402-RES"))
    )
    (comp (ref "R49")
      (value "180")
      (footprint "eagle-import:0402-RES")
      (libsource (lib "eagle-import") (part "RESISTOR0402-RES"))
    )
    (comp (ref "R50")
      (value "10k")
      (footprint "eagle-import:0402-RES")
      (libsource (lib "eagle-import") (part "RESISTOR0402-RES"))
    )
    (comp (ref "R51")
      (value "10k")
      (footprint "eagle-import:0402-RES")
      (libsource (lib "eagle-import") (part "RESISTOR0402-RES"))
    )
    (comp (ref "R52")
      (value "10k")
      (footprint "eagle-import:0402-RES")
      (libsource (lib "eagle-import") (part "RESISTOR0402-RES"))
    )
    (comp (ref "R53")
      (value "10k")
      (footprint "eagle-import:0402-RES")
      (libsource (lib "eagle-import") (part "RESISTOR0402-RES"))
    )
    (comp (ref "R54")
      (value "180")
      (footprint "eagle-import:0402-RES")
      (libsource (lib "eagle-import") (part "RESISTOR0402-RES"))
    )
    (comp (ref "R55")
      (value "1k")
      (footprint "eagle-import:0402-RES")
      (libsource (lib "eagle-import") (part "RESISTOR0402-RES"))
    )
    (comp (ref "R56")
      (value "10k")
      (footprint "eagle-import:0402-RES")
      (libsource (lib "eagle-import") (part "RESISTOR0402-RES"))
    )
    (comp (ref "R57")
      (value "3.3k")
      (footprint "eagle-import:0402-RES")
      (libsource (lib "eagle-import") (part "RESISTOR0402-RES"))
    )
    (comp (ref "R58")
      (value "331")
      (footprint "eagle-import:0402-RES")
      (libsource (lib "eagle-import") (part "RESISTOR0402-RES"))
    )
    (comp (ref "R59")
      (value "0")
      (footprint "eagle-import:0603-RES")
      (libsource (lib "eagle-import") (part "RESISTOR0603-RES"))
    )
    (comp (ref "R60")
      (value "0")
      (footprint "eagle-import:0603-RES")
      (libsource (lib "eagle-import") (part "RESISTOR0603-RES"))
    )
    (comp (ref "R61")
      (value "0")
      (footprint "eagle-import:0603-RES")
      (libsource (lib "eagle-import") (part "RESISTOR0603-RES"))
    )
    (comp (ref "R62")
      (value "0")
      (footprint "eagle-import:0603-RES")
      (libsource (lib "eagle-import") (part "RESISTOR0603-RES"))
    )
    (comp (ref "R63")
      (value "DNP")
      (footprint "eagle-import:0603-RES")
      (libsource (lib "eagle-import") (part "RESISTOR0603-RES"))
    )
    (comp (ref "R64")
      (value "10k")
      (footprint "eagle-import:0402-RES")
      (libsource (lib "eagle-import") (part "RESISTOR0402-RES"))
    )
    (comp (ref "R65")
      (value "0")
      (footprint "eagle-import:0603-RES")
      (libsource (lib "eagle-import") (part "RESISTOR0603-RES"))
    )
    (comp (ref "R66")
      (value "0")
      (footprint "eagle-import:0603-RES")
      (libsource (lib "eagle-import") (part "RESISTOR0603-RES"))
    )
    (comp (ref "R67")
      (value "100k")
      (footprint "eagle-import:0402-RES")
      (libsource (lib "eagle-import") (part "RESISTOR0402-RES"))
    )
    (comp (ref "R68")
      (value "3.3k")
      (footprint "eagle-import:0402-RES")
      (libsource (lib "eagle-import") (part "RESISTOR0402-RES"))
    )
    (comp (ref "R69")
      (value "3.3k")
      (footprint "eagle-import:0402-RES")
      (libsource (lib "eagle-import") (part "RESISTOR0402-RES"))
    )
    (comp (ref "R70")
      (value "180")
      (footprint "eagle-import:0402-RES")
      (libsource (lib "eagle-import") (part "RESISTOR0402-RES"))
    )
    (comp (ref "R71")
      (value "180")
      (footprint "eagle-import:0402-RES")
      (libsource (lib "eagle-import") (part "RESISTOR0402-RES"))
    )
    (comp (ref "R72")
      (value "10k")
      (footprint "eagle-import:0402-RES")
      (libsource (lib "eagle-import") (part "RESISTOR0402-RES"))
    )
    (comp (ref "R73")
      (value "10k")
      (footprint "eagle-import:0402-RES")
      (libsource (lib "eagle-import") (part "RESISTOR0402-RES"))
    )
    (comp (ref "R74")
      (value "10k")
      (footprint "eagle-import:0402-RES")
      (libsource (lib "eagle-import") (part "RESISTOR0402-RES"))
    )
    (comp (ref "R75")
      (value "10k")
      (footprint "eagle-import:0402-RES")
      (libsource (lib "eagle-import") (part "RESISTOR0402-RES"))
    )
    (comp (ref "R76")
      (value "180")
      (footprint "eagle-import:0402-RES")
      (libsource (lib "eagle-import") (part "RESISTOR0402-RES"))
    )
    (comp (ref "R77")
      (value "1k")
      (footprint "eagle-import:0402-RES")
      (libsource (lib "eagle-import") (part "RESISTOR0402-RES"))
    )
    (comp (ref "R78")
      (value "10k")
      (footprint "eagle-import:0402-RES")
      (libsource (lib "eagle-import") (part "RESISTOR0402-RES"))
    )
    (comp (ref "R79")
      (value "3.3k")
      (footprint "eagle-import:0402-RES")
      (libsource (lib "eagle-import") (part "RESISTOR0402-RES"))
    )
    (comp (ref "R80")
      (value "331")
      (footprint "eagle-import:0402-RES")
      (libsource (lib "eagle-import") (part "RESISTOR0402-RES"))
    )
    (comp (ref "R81")
      (value "0")
      (footprint "eagle-import:0603-RES")
      (libsource (lib "eagle-import") (part "RESISTOR0603-RES"))
    )
    (comp (ref "R82")
      (value "0")
      (footprint "eagle-import:0603-RES")
      (libsource (lib "eagle-import") (part "RESISTOR0603-RES"))
    )
    (comp (ref "R83")
      (value "0")
      (footprint "eagle-import:0603-RES")
      (libsource (lib "eagle-import") (part "RESISTOR0603-RES"))
    )
    (comp (ref "R84")
      (value "0")
      (footprint "eagle-import:0603-RES")
      (libsource (lib "eagle-import") (part "RESISTOR0603-RES"))
    )
    (comp (ref "R85")
      (value "DNP")
      (footprint "eagle-import:0603-RES")
      (libsource (lib "eagle-import") (part "RESISTOR0603-RES"))
    )
    (comp (ref "R86")
      (value "10k")
      (footprint "eagle-import:0402-RES")
      (libsource (lib "eagle-import") (part "RESISTOR0402-RES"))
    )
    (comp (ref "R87")
      (value "0")
      (footprint "eagle-import:0603-RES")
      (libsource (lib "eagle-import") (part "RESISTOR0603-RES"))
    )
    (comp (ref "R88")
      (value "0")
      (footprint "eagle-import:0603-RES")
      (libsource (lib "eagle-import") (part "RESISTOR0603-RES"))
    )
    (comp (ref "R111")
      (value "100k")
      (footprint "eagle-import:0402-RES")
      (libsource (lib "eagle-import") (part "RESISTOR0402-RES"))
    )
    (comp (ref "R112")
      (value "3.3k")
      (footprint "eagle-import:0402-RES")
      (libsource (lib "eagle-import") (part "RESISTOR0402-RES"))
    )
    (comp (ref "R113")
      (value "3.3k")
      (footprint "eagle-import:0402-RES")
      (libsource (lib "eagle-import") (part "RESISTOR0402-RES"))
    )
    (comp (ref "R114")
      (value "180")
      (footprint "eagle-import:0402-RES")
      (libsource (lib "eagle-import") (part "RESISTOR0402-RES"))
    )
    (comp (ref "R115")
      (value "180")
      (footprint "eagle-import:0402-RES")
      (libsource (lib "eagle-import") (part "RESISTOR0402-RES"))
    )
    (comp (ref "R116")
      (value "10k")
      (footprint "eagle-import:0402-RES")
      (libsource (lib "eagle-import") (part "RESISTOR0402-RES"))
    )
    (comp (ref "R117")
      (value "10k")
      (footprint "eagle-import:0402-RES")
      (libsource (lib "eagle-import") (part "RESISTOR0402-RES"))
    )
    (comp (ref "R118")
      (value "10k")
      (footprint "eagle-import:0402-RES")
      (libsource (lib "eagle-import") (part "RESISTOR0402-RES"))
    )
    (comp (ref "R119")
      (value "10k")
      (footprint "eagle-import:0402-RES")
      (libsource (lib "eagle-import") (part "RESISTOR0402-RES"))
    )
    (comp (ref "R120")
      (value "180")
      (footprint "eagle-import:0402-RES")
      (libsource (lib "eagle-import") (part "RESISTOR0402-RES"))
    )
    (comp (ref "R121")
      (value "1k")
      (footprint "eagle-import:0402-RES")
      (libsource (lib "eagle-import") (part "RESISTOR0402-RES"))
    )
    (comp (ref "R122")
      (value "10k")
      (footprint "eagle-import:0402-RES")
      (libsource (lib "eagle-import") (part "RESISTOR0402-RES"))
    )
    (comp (ref "R123")
      (value "3.3k")
      (footprint "eagle-import:0402-RES")
      (libsource (lib "eagle-import") (part "RESISTOR0402-RES"))
    )
    (comp (ref "R124")
      (value "331")
      (footprint "eagle-import:0402-RES")
      (libsource (lib "eagle-import") (part "RESISTOR0402-RES"))
    )
    (comp (ref "R125")
      (value "0")
      (footprint "eagle-import:0603-RES")
      (libsource (lib "eagle-import") (part "RESISTOR0603-RES"))
    )
    (comp (ref "R126")
      (value "0")
      (footprint "eagle-import:0603-RES")
      (libsource (lib "eagle-import") (part "RESISTOR0603-RES"))
    )
    (comp (ref "R127")
      (value "0")
      (footprint "eagle-import:0603-RES")
      (libsource (lib "eagle-import") (part "RESISTOR0603-RES"))
    )
    (comp (ref "R128")
      (value "0")
      (footprint "eagle-import:0603-RES")
      (libsource (lib "eagle-import") (part "RESISTOR0603-RES"))
    )
    (comp (ref "R129")
      (value "DNP")
      (footprint "eagle-import:0603-RES")
      (libsource (lib "eagle-import") (part "RESISTOR0603-RES"))
    )
    (comp (ref "R130")
      (value "10k")
      (footprint "eagle-import:0402-RES")
      (libsource (lib "eagle-import") (part "RESISTOR0402-RES"))
    )
    (comp (ref "R131")
      (value "0")
      (footprint "eagle-import:0603-RES")
      (libsource (lib "eagle-import") (part "RESISTOR0603-RES"))
    )
    (comp (ref "R132")
      (value "0")
      (footprint "eagle-import:0603-RES")
      (libsource (lib "eagle-import") (part "RESISTOR0603-RES"))
    )
    (comp (ref "REAR_PANEL1")
      (value "ALTA_CELL")
      (footprint "eagle-import:ALTA_CELL")
      (libsource (lib "eagle-import") (part "ALTA_CELL"))
    )
    (comp (ref "REAR_PANEL2")
      (value "ALTA_CELL")
      (footprint "eagle-import:ALTA_CELL")
      (libsource (lib "eagle-import") (part "ALTA_CELL"))
    )
    (comp (ref "REAR_PANEL3")
      (value "ALTA_CELL")
      (footprint "eagle-import:ALTA_CELL")
      (libsource (lib "eagle-import") (part "ALTA_CELL"))
    )
    (comp (ref "REAR_PANEL5")
      (value "ALTA_CELL")
      (footprint "eagle-import:ALTA_CELL")
      (libsource (lib "eagle-import") (part "ALTA_CELL"))
    )
    (comp (ref "TSX1")
      (value "TSX-3225")
      (footprint "eagle-import:TSX-3225")
      (libsource (lib "eagle-import") (part "TSX-3225"))
    )
    (comp (ref "TSX2")
      (value "TSX-3225")
      (footprint "eagle-import:TSX-3225")
      (libsource (lib "eagle-import") (part "TSX-3225"))
    )
    (comp (ref "TSX3")
      (value "TSX-3225")
      (footprint "eagle-import:TSX-3225")
      (libsource (lib "eagle-import") (part "TSX-3225"))
    )
    (comp (ref "TSX5")
      (value "TSX-3225")
      (footprint "eagle-import:TSX-3225")
      (libsource (lib "eagle-import") (part "TSX-3225"))
    )
    (comp (ref "U$1")
      (value "LV8417CS")
      (footprint "eagle-import:LV8417CS")
      (libsource (lib "eagle-import") (part "LV8417CS"))
    )
    (comp (ref "U$10")
      (value "JOHANSON_GPS_CHIP")
      (footprint "eagle-import:JOHANSON_GPS_CHIP")
      (libsource (lib "eagle-import") (part "JOHANSON_GPS_CHIP"))
    )
    (comp (ref "U$11")
      (value "PANASONIC_RECTIFIER")
      (footprint "eagle-import:PANASONIC_RECTIFIER")
      (libsource (lib "eagle-import") (part "PANASONIC_RECTIFIER"))
    )
    (comp (ref "U$12")
      (value "PCB_ANTENNA")
      (footprint "eagle-import:PCB_ANTENNA")
      (libsource (lib "eagle-import") (part "PCB_ANTENNA"))
    )
    (comp (ref "U$13")
      (value "MM5329-2700")
      (footprint "eagle-import:MM5829-2700")
      (libsource (lib "eagle-import") (part "MM5329-2700"))
    )
    (comp (ref "U$14")
      (value "MM5329-2700")
      (footprint "eagle-import:MM5829-2700")
      (libsource (lib "eagle-import") (part "MM5329-2700"))
    )
    (comp (ref "U$15")
      (value "L6920")
      (footprint "eagle-import:L6920")
      (libsource (lib "eagle-import") (part "L6920"))
    )
    (comp (ref "U$16")
      (value "HDMID")
      (footprint "eagle-import:HDMID")
      (libsource (lib "eagle-import") (part "HDMID"))
    )
    (comp (ref "U$17")
      (value "LV8417CS")
      (footprint "eagle-import:LV8417CS")
      (libsource (lib "eagle-import") (part "LV8417CS"))
    )
    (comp (ref "U$18")
      (value "JOHANSON_GPS_CHIP")
      (footprint "eagle-import:JOHANSON_GPS_CHIP")
      (libsource (lib "eagle-import") (part "JOHANSON_GPS_CHIP"))
    )
    (comp (ref "U$19")
      (value "PANASONIC_RECTIFIER")
      (footprint "eagle-import:PANASONIC_RECTIFIER")
      (libsource (lib "eagle-import") (part "PANASONIC_RECTIFIER"))
    )
    (comp (ref "U$20")
      (value "PCB_ANTENNA")
      (footprint "eagle-import:PCB_ANTENNA")
      (libsource (lib "eagle-import") (part "PCB_ANTENNA"))
    )
    (comp (ref "U$21")
      (value "MM5329-2700")
      (footprint "eagle-import:MM5829-2700")
      (libsource (lib "eagle-import") (part "MM5329-2700"))
    )
    (comp (ref "U$22")
      (value "MM5329-2700")
      (footprint "eagle-import:MM5829-2700")
      (libsource (lib "eagle-import") (part "MM5329-2700"))
    )
    (comp (ref "U$23")
      (value "L6920")
      (footprint "eagle-import:L6920")
      (libsource (lib "eagle-import") (part "L6920"))
    )
    (comp (ref "U$24")
      (value "HDMID")
      (footprint "eagle-import:HDMID")
      (libsource (lib "eagle-import") (part "HDMID"))
    )
    (comp (ref "U$25")
      (value "LV8417CS")
      (footprint "eagle-import:LV8417CS")
      (libsource (lib "eagle-import") (part "LV8417CS"))
    )
    (comp (ref "U$26")
      (value "JOHANSON_GPS_CHIP")
      (footprint "eagle-import:JOHANSON_GPS_CHIP")
      (libsource (lib "eagle-import") (part "JOHANSON_GPS_CHIP"))
    )
    (comp (ref "U$27")
      (value "PANASONIC_RECTIFIER")
      (footprint "eagle-import:PANASONIC_RECTIFIER")
      (libsource (lib "eagle-import") (part "PANASONIC_RECTIFIER"))
    )
    (comp (ref "U$28")
      (value "PCB_ANTENNA")
      (footprint "eagle-import:PCB_ANTENNA")
      (libsource (lib "eagle-import") (part "PCB_ANTENNA"))
    )
    (comp (ref "U$29")
      (value "MM5329-2700")
      (footprint "eagle-import:MM5829-2700")
      (libsource (lib "eagle-import") (part "MM5329-2700"))
    )
    (comp (ref "U$30")
      (value "MM5329-2700")
      (footprint "eagle-import:MM5829-2700")
      (libsource (lib "eagle-import") (part "MM5329-2700"))
    )
    (comp (ref "U$31")
      (value "L6920")
      (footprint "eagle-import:L6920")
      (libsource (lib "eagle-import") (part "L6920"))
    )
    (comp (ref "U$32")
      (value "HDMID")
      (footprint "eagle-import:HDMID")
      (libsource (lib "eagle-import") (part "HDMID"))
    )
    (comp (ref "U$41")
      (value "LV8417CS")
      (footprint "eagle-import:LV8417CS")
      (libsource (lib "eagle-import") (part "LV8417CS"))
    )
    (comp (ref "U$42")
      (value "JOHANSON_GPS_CHIP")
      (footprint "eagle-import:JOHANSON_GPS_CHIP")
      (libsource (lib "eagle-import") (part "JOHANSON_GPS_CHIP"))
    )
    (comp (ref "U$43")
      (value "PANASONIC_RECTIFIER")
      (footprint "eagle-import:PANASONIC_RECTIFIER")
      (libsource (lib "eagle-import") (part "PANASONIC_RECTIFIER"))
    )
    (comp (ref "U$44")
      (value "PCB_ANTENNA")
      (footprint "eagle-import:PCB_ANTENNA")
      (libsource (lib "eagle-import") (part "PCB_ANTENNA"))
    )
    (comp (ref "U$45")
      (value "MM5329-2700")
      (footprint "eagle-import:MM5829-2700")
      (libsource (lib "eagle-import") (part "MM5329-2700"))
    )
    (comp (ref "U$46")
      (value "MM5329-2700")
      (footprint "eagle-import:MM5829-2700")
      (libsource (lib "eagle-import") (part "MM5329-2700"))
    )
    (comp (ref "U$47")
      (value "L6920")
      (footprint "eagle-import:L6920")
      (libsource (lib "eagle-import") (part "L6920"))
    )
    (comp (ref "U$48")
      (value "HDMID")
      (footprint "eagle-import:HDMID")
      (libsource (lib "eagle-import") (part "HDMID"))
    )
  )
  (nets
    (net (code "1") (name "/ACCEL_INT") (class "Default")
      (node (ref "IMU1") (pin "12") (pinfunction "INT2_A/G_12") (pintype "bidirectional"))
      (node (ref "IMU2") (pin "12") (pinfunction "INT2_A/G_12") (pintype "bidirectional"))
      (node (ref "IMU3") (pin "12") (pinfunction "INT2_A/G_12") (pintype "bidirectional"))
      (node (ref "IMU5") (pin "12") (pinfunction "INT2_A/G_12") (pintype "bidirectional"))
      (node (ref "MICROCONTROLLER1") (pin "18") (pinfunction "18_18") (pintype "bidirectional"))
      (node (ref "MICROCONTROLLER2") (pin "18") (pinfunction "18_18") (pintype "bidirectional"))
      (node (ref "MICROCONTROLLER3") (pin "18") (pinfunction "18_18") (pintype "bidirectional"))
      (node (ref "MICROCONTROLLER5") (pin "18") (pinfunction "18_18") (pintype "bidirectional"))
    )
    (net (code "2") (name "/ADC0") (class "Default")
      (node (ref "LS11") (pin "E") (pinfunction "E1_E") (pintype "passive"))
      (node (ref "LS3") (pin "E") (pinfunction "E1_E") (pintype "passive"))
      (node (ref "LS5") (pin "E") (pinfunction "E1_E") (pintype "passive"))
      (node (ref "LS7") (pin "E") (pinfunction "E1_E") (pintype "passive"))
      (node (ref "MICROCONTROLLER1") (pin "36") (pinfunction "36_36") (pintype "bidirectional"))
      (node (ref "MICROCONTROLLER2") (pin "36") (pinfunction "36_36") (pintype "bidirectional"))
      (node (ref "MICROCONTROLLER3") (pin "36") (pinfunction "36_36") (pintype "bidirectional"))
      (node (ref "MICROCONTROLLER5") (pin "36") (pinfunction "36_36") (pintype "bidirectional"))
      (node (ref "R117") (pin "1") (pinfunction "1_1") (pintype "passive"))
      (node (ref "R29") (pin "1") (pinfunction "1_1") (pintype "passive"))
      (node (ref "R51") (pin "1") (pinfunction "1_1") (pintype "passive"))
      (node (ref "R73") (pin "1") (pinfunction "1_1") (pintype "passive"))
    )
    (net (code "3") (name "/ADC1") (class "Default")
      (node (ref "LS12") (pin "E") (pinfunction "E1_E") (pintype "passive"))
      (node (ref "LS4") (pin "E") (pinfunction "E1_E") (pintype "passive"))
      (node (ref "LS6") (pin "E") (pinfunction "E1_E") (pintype "passive"))
      (node (ref "LS8") (pin "E") (pinfunction "E1_E") (pintype "passive"))
      (node (ref "MICROCONTROLLER1") (pin "37") (pinfunction "37_37") (pintype "bidirectional"))
      (node (ref "MICROCONTROLLER2") (pin "37") (pinfunction "37_37") (pintype "bidirectional"))
      (node (ref "MICROCONTROLLER3") (pin "37") (pinfunction "37_37") (pintype "bidirectional"))
      (node (ref "MICROCONTROLLER5") (pin "37") (pinfunction "37_37") (pintype "bidirectional"))
      (node (ref "R118") (pin "1") (pinfunction "1_1") (pintype "passive"))
      (node (ref "R30") (pin "1") (pinfunction "1_1") (pintype "passive"))
      (node (ref "R52") (pin "1") (pinfunction "1_1") (pintype "passive"))
      (node (ref "R74") (pin "1") (pinfunction "1_1") (pintype "passive"))
    )
    (net (code "4") (name "/COIL") (class "Default")
      (node (ref "R124") (pin "2") (pinfunction "2_2") (pintype "passive"))
      (node (ref "R36") (pin "2") (pinfunction "2_2") (pintype "passive"))
      (node (ref "R58") (pin "2") (pinfunction "2_2") (pintype "passive"))
      (node (ref "R80") (pin "2") (pinfunction "2_2") (pintype "passive"))
      (node (ref "U$1") (pin "OUT2") (pinfunction "OUT2_OUT2") (pintype "bidirectional"))
      (node (ref "U$11") (pin "C1") (pinfunction "C1_C1") (pintype "bidirectional"))
      (node (ref "U$11") (pin "C2") (pinfunction "C2_C2") (pintype "bidirectional"))
      (node (ref "U$17") (pin "OUT2") (pinfunction "OUT2_OUT2") (pintype "bidirectional"))
      (node (ref "U$19") (pin "C1") (pinfunction "C1_C1") (pintype "bidirectional"))
      (node (ref "U$19") (pin "C2") (pinfunction "C2_C2") (pintype "bidirectional"))
      (node (ref "U$25") (pin "OUT2") (pinfunction "OUT2_OUT2") (pintype "bidirectional"))
      (node (ref "U$27") (pin "C1") (pinfunction "C1_C1") (pintype "bidirectional"))
      (node (ref "U$27") (pin "C2") (pinfunction "C2_C2") (pintype "bidirectional"))
      (node (ref "U$41") (pin "OUT2") (pinfunction "OUT2_OUT2") (pintype "bidirectional"))
      (node (ref "U$43") (pin "C1") (pinfunction "C1_C1") (pintype "bidirectional"))
      (node (ref "U$43") (pin "C2") (pinfunction "C2_C2") (pintype "bidirectional"))
    )
    (net (code "5") (name "/DCDC_SW") (class "Default")
      (node (ref "L13") (pin "1") (pinfunction "1_1") (pintype "passive"))
      (node (ref "L21") (pin "1") (pinfunction "1_1") (pintype "passive"))
      (node (ref "L5") (pin "1") (pinfunction "1_1") (pintype "passive"))
      (node (ref "L9") (pin "1") (pinfunction "1_1") (pintype "passive"))
      (node (ref "MICROCONTROLLER1") (pin "33") (pinfunction "33_33") (pintype "power_in"))
      (node (ref "MICROCONTROLLER2") (pin "33") (pinfunction "33_33") (pintype "power_in"))
      (node (ref "MICROCONTROLLER3") (pin "33") (pinfunction "33_33") (pintype "power_in"))
      (node (ref "MICROCONTROLLER5") (pin "33") (pinfunction "33_33") (pintype "power_in"))
    )
    (net (code "6") (name "/GLED") (class "Default")
      (node (ref "MICROCONTROLLER1") (pin "12") (pinfunction "12_12") (pintype "bidirectional"))
      (node (ref "MICROCONTROLLER2") (pin "12") (pinfunction "12_12") (pintype "bidirectional"))
      (node (ref "MICROCONTROLLER3") (pin "12") (pinfunction "12_12") (pintype "bidirectional"))
      (node (ref "MICROCONTROLLER5") (pin "12") (pinfunction "12_12") (pintype "bidirectional"))
      (node (ref "R115") (pin "2") (pinfunction "2_2") (pintype "passive"))
      (node (ref "R27") (pin "2") (pinfunction "2_2") (pintype "passive"))
      (node (ref "R49") (pin "2") (pinfunction "2_2") (pintype "passive"))
      (node (ref "R71") (pin "2") (pinfunction "2_2") (pintype "passive"))
    )
    (net (code "7") (name "/GYRO_INT") (class "Default")
      (node (ref "IMU1") (pin "11") (pinfunction "INT1_A/G_11") (pintype "bidirectional"))
      (node (ref "IMU2") (pin "11") (pinfunction "INT1_A/G_11") (pintype "bidirectional"))
      (node (ref "IMU3") (pin "11") (pinfunction "INT1_A/G_11") (pintype "bidirectional"))
      (node (ref "IMU5") (pin "11") (pinfunction "INT1_A/G_11") (pintype "bidirectional"))
      (node (ref "MICROCONTROLLER1") (pin "19") (pinfunction "19_19") (pintype "bidirectional"))
      (node (ref "MICROCONTROLLER2") (pin "19") (pinfunction "19_19") (pintype "bidirectional"))
      (node (ref "MICROCONTROLLER3") (pin "19") (pinfunction "19_19") (pintype "bidirectional"))
      (node (ref "MICROCONTROLLER5") (pin "19") (pinfunction "19_19") (pintype "bidirectional"))
    )
    (net (code "8") (name "/JTAG_TCKC") (class "Default")
      (node (ref "MICROCONTROLLER1") (pin "25") (pinfunction "25_25") (pintype "input"))
      (node (ref "MICROCONTROLLER2") (pin "25") (pinfunction "25_25") (pintype "input"))
      (node (ref "MICROCONTROLLER3") (pin "25") (pinfunction "25_25") (pintype "input"))
      (node (ref "MICROCONTROLLER5") (pin "25") (pinfunction "25_25") (pintype "input"))
      (node (ref "U$16") (pin "14") (pinfunction "14_14") (pintype "bidirectional"))
      (node (ref "U$16") (pin "15") (pinfunction "15_15") (pintype "bidirectional"))
      (node (ref "U$24") (pin "14") (pinfunction "14_14") (pintype "bidirectional"))
      (node (ref "U$24") (pin "15") (pinfunction "15_15") (pintype "bidirectional"))
      (node (ref "U$32") (pin "14") (pinfunction "14_14") (pintype "bidirectional"))
      (node (ref "U$32") (pin "15") (pinfunction "15_15") (pintype "bidirectional"))
      (node (ref "U$48") (pin "14") (pinfunction "14_14") (pintype "bidirectional"))
      (node (ref "U$48") (pin "15") (pinfunction "15_15") (pintype "bidirectional"))
    )
    (net (code "9") (name "/JTAG_TMSC") (class "Default")
      (node (ref "MICROCONTROLLER1") (pin "24") (pinfunction "24_24") (pintype "bidirectional"))
      (node (ref "MICROCONTROLLER2") (pin "24") (pinfunction "24_24") (pintype "bidirectional"))
      (node (ref "MICROCONTROLLER3") (pin "24") (pinfunction "24_24") (pintype "bidirectional"))
      (node (ref "MICROCONTROLLER5") (pin "24") (pinfunction "24_24") (pintype "bidirectional"))
      (node (ref "U$16") (pin "16") (pinfunction "16_16") (pintype "bidirectional"))
      (node (ref "U$16") (pin "17") (pinfunction "17_17") (pintype "bidirectional"))
      (node (ref "U$24") (pin "16") (pinfunction "16_16") (pintype "bidirectional"))
      (node (ref "U$24") (pin "17") (pinfunction "17_17") (pintype "bidirectional"))
      (node (ref "U$32") (pin "16") (pinfunction "16_16") (pintype "bidirectional"))
      (node (ref "U$32") (pin "17") (pinfunction "17_17") (pintype "bidirectional"))
      (node (ref "U$48") (pin "16") (pinfunction "16_16") (pintype "bidirectional"))
      (node (ref "U$48") (pin "17") (pinfunction "17_17") (pintype "bidirectional"))
    )
    (net (code "10") (name "/MAG_INT") (class "Default")
      (node (ref "IMU1") (pin "9") (pinfunction "DRDY_M_9") (pintype "bidirectional"))
      (node (ref "IMU2") (pin "9") (pinfunction "DRDY_M_9") (pintype "bidirectional"))
      (node (ref "IMU3") (pin "9") (pinfunction "DRDY_M_9") (pintype "bidirectional"))
      (node (ref "IMU5") (pin "9") (pinfunction "DRDY_M_9") (pintype "bidirectional"))
      (node (ref "MICROCONTROLLER1") (pin "20") (pinfunction "20_20") (pintype "bidirectional"))
      (node (ref "MICROCONTROLLER2") (pin "20") (pinfunction "20_20") (pintype "bidirectional"))
      (node (ref "MICROCONTROLLER3") (pin "20") (pinfunction "20_20") (pintype "bidirectional"))
      (node (ref "MICROCONTROLLER5") (pin "20") (pinfunction "20_20") (pintype "bidirectional"))
    )
    (net (code "11") (name "/NAV") (class "Default")
      (node (ref "GPS1") (pin "7") (pinfunction "GPIO0/LED_7") (pintype "bidirectional"))
      (node (ref "GPS2") (pin "7") (pinfunction "GPIO0/LED_7") (pintype "bidirectional"))
      (node (ref "GPS3") (pin "7") (pinfunction "GPIO0/LED_7") (pintype "bidirectional"))
      (node (ref "GPS5") (pin "7") (pinfunction "GPIO0/LED_7") (pintype "bidirectional"))
      (node (ref "MICROCONTROLLER1") (pin "6") (pinfunction "6_6") (pintype "bidirectional"))
      (node (ref "MICROCONTROLLER2") (pin "6") (pinfunction "6_6") (pintype "bidirectional"))
      (node (ref "MICROCONTROLLER3") (pin "6") (pinfunction "6_6") (pintype "bidirectional"))
      (node (ref "MICROCONTROLLER5") (pin "6") (pinfunction "6_6") (pintype "bidirectional"))
      (node (ref "R120") (pin "1") (pinfunction "1_1") (pintype "passive"))
      (node (ref "R32") (pin "1") (pinfunction "1_1") (pintype "passive"))
      (node (ref "R54") (pin "1") (pinfunction "1_1") (pintype "passive"))
      (node (ref "R76") (pin "1") (pinfunction "1_1") (pintype "passive"))
    )
    (net (code "12") (name "/PWM1") (class "Default")
      (node (ref "MICROCONTROLLER1") (pin "40") (pinfunction "40_40") (pintype "bidirectional"))
      (node (ref "MICROCONTROLLER2") (pin "40") (pinfunction "40_40") (pintype "bidirectional"))
      (node (ref "MICROCONTROLLER3") (pin "40") (pinfunction "40_40") (pintype "bidirectional"))
      (node (ref "MICROCONTROLLER5") (pin "40") (pinfunction "40_40") (pintype "bidirectional"))
      (node (ref "U$1") (pin "IN1") (pinfunction "IN1_IN1") (pintype "bidirectional"))
      (node (ref "U$17") (pin "IN1") (pinfunction "IN1_IN1") (pintype "bidirectional"))
      (node (ref "U$25") (pin "IN1") (pinfunction "IN1_IN1") (pintype "bidirectional"))
      (node (ref "U$41") (pin "IN1") (pinfunction "IN1_IN1") (pintype "bidirectional"))
    )
    (net (code "13") (name "/PWM2") (class "Default")
      (node (ref "MICROCONTROLLER1") (pin "41") (pinfunction "41_41") (pintype "bidirectional"))
      (node (ref "MICROCONTROLLER2") (pin "41") (pinfunction "41_41") (pintype "bidirectional"))
      (node (ref "MICROCONTROLLER3") (pin "41") (pinfunction "41_41") (pintype "bidirectional"))
      (node (ref "MICROCONTROLLER5") (pin "41") (pinfunction "41_41") (pintype "bidirectional"))
      (node (ref "U$1") (pin "IN2") (pinfunction "IN2_IN2") (pintype "bidirectional"))
      (node (ref "U$17") (pin "IN2") (pinfunction "IN2_IN2") (pintype "bidirectional"))
      (node (ref "U$25") (pin "IN2") (pinfunction "IN2_IN2") (pintype "bidirectional"))
      (node (ref "U$41") (pin "IN2") (pinfunction "IN2_IN2") (pintype "bidirectional"))
    )
    (net (code "14") (name "/RESET") (class "Default")
      (node (ref "C116") (pin "1") (pinfunction "1_1") (pintype "passive"))
      (node (ref "C21") (pin "1") (pinfunction "1_1") (pintype "passive"))
      (node (ref "C47") (pin "1") (pinfunction "1_1") (pintype "passive"))
      (node (ref "C70") (pin "1") (pinfunction "1_1") (pintype "passive"))
      (node (ref "MICROCONTROLLER1") (pin "35") (pinfunction "35_35") (pintype "input"))
      (node (ref "MICROCONTROLLER2") (pin "35") (pinfunction "35_35") (pintype "input"))
      (node (ref "MICROCONTROLLER3") (pin "35") (pinfunction "35_35") (pintype "input"))
      (node (ref "MICROCONTROLLER5") (pin "35") (pinfunction "35_35") (pintype "input"))
      (node (ref "R111") (pin "1") (pinfunction "1_1") (pintype "passive"))
      (node (ref "R23") (pin "1") (pinfunction "1_1") (pintype "passive"))
      (node (ref "R45") (pin "1") (pinfunction "1_1") (pintype "passive"))
      (node (ref "R67") (pin "1") (pinfunction "1_1") (pintype "passive"))
      (node (ref "U$16") (pin "6") (pinfunction "6_6") (pintype "bidirectional"))
      (node (ref "U$16") (pin "7") (pinfunction "7_7") (pintype "bidirectional"))
      (node (ref "U$24") (pin "6") (pinfunction "6_6") (pintype "bidirectional"))
      (node (ref "U$24") (pin "7") (pinfunction "7_7") (pintype "bidirectional"))
      (node (ref "U$32") (pin "6") (pinfunction "6_6") (pintype "bidirectional"))
      (node (ref "U$32") (pin "7") (pinfunction "7_7") (pintype "bidirectional"))
      (node (ref "U$48") (pin "6") (pinfunction "6_6") (pintype "bidirectional"))
      (node (ref "U$48") (pin "7") (pinfunction "7_7") (pintype "bidirectional"))
    )
    (net (code "15") (name "/RLED") (class "Default")
      (node (ref "MICROCONTROLLER1") (pin "11") (pinfunction "11_11") (pintype "bidirectional"))
      (node (ref "MICROCONTROLLER2") (pin "11") (pinfunction "11_11") (pintype "bidirectional"))
      (node (ref "MICROCONTROLLER3") (pin "11") (pinfunction "11_11") (pintype "bidirectional"))
      (node (ref "MICROCONTROLLER5") (pin "11") (pinfunction "11_11") (pintype "bidirectional"))
      (node (ref "R114") (pin "2") (pinfunction "2_2") (pintype "passive"))
      (node (ref "R26") (pin "2") (pinfunction "2_2") (pintype "passive"))
      (node (ref "R48") (pin "2") (pinfunction "2_2") (pintype "passive"))
      (node (ref "R70") (pin "2") (pinfunction "2_2") (pintype "passive"))
    )
    (net (code "16") (name "/RXD") (class "Default")
      (node (ref "GPS1") (pin "44") (pinfunction "TXD0_44") (pintype "bidirectional"))
      (node (ref "GPS2") (pin "44") (pinfunction "TXD0_44") (pintype "bidirectional"))
      (node (ref "GPS3") (pin "44") (pinfunction "TXD0_44") (pintype "bidirectional"))
      (node (ref "GPS5") (pin "44") (pinfunction "TXD0_44") (pintype "bidirectional"))
      (node (ref "MICROCONTROLLER1") (pin "7") (pinfunction "7_7") (pintype "bidirectional"))
      (node (ref "MICROCONTROLLER2") (pin "7") (pinfunction "7_7") (pintype "bidirectional"))
      (node (ref "MICROCONTROLLER3") (pin "7") (pinfunction "7_7") (pintype "bidirectional"))
      (node (ref "MICROCONTROLLER5") (pin "7") (pinfunction "7_7") (pintype "bidirectional"))
      (node (ref "U$16") (pin "2") (pinfunction "2_2") (pintype "bidirectional"))
      (node (ref "U$16") (pin "3") (pinfunction "3_3") (pintype "bidirectional"))
      (node (ref "U$24") (pin "2") (pinfunction "2_2") (pintype "bidirectional"))
      (node (ref "U$24") (pin "3") (pinfunction "3_3") (pintype "bidirectional"))
      (node (ref "U$32") (pin "2") (pinfunction "2_2") (pintype "bidirectional"))
      (node (ref "U$32") (pin "3") (pinfunction "3_3") (pintype "bidirectional"))
      (node (ref "U$48") (pin "2") (pinfunction "2_2") (pintype "bidirectional"))
      (node (ref "U$48") (pin "3") (pinfunction "3_3") (pintype "bidirectional"))
    )
    (net (code "17") (name "/SCL") (class "Default")
      (node (ref "IMU1") (pin "2") (pinfunction "SCL/SPC_2") (pintype "bidirectional"))
      (node (ref "IMU2") (pin "2") (pinfunction "SCL/SPC_2") (pintype "bidirectional"))
      (node (ref "IMU3") (pin "2") (pinfunction "SCL/SPC_2") (pintype "bidirectional"))
      (node (ref "IMU5") (pin "2") (pinfunction "SCL/SPC_2") (pintype "bidirectional"))
      (node (ref "MICROCONTROLLER1") (pin "9") (pinfunction "9_9") (pintype "bidirectional"))
      (node (ref "MICROCONTROLLER2") (pin "9") (pinfunction "9_9") (pintype "bidirectional"))
      (node (ref "MICROCONTROLLER3") (pin "9") (pinfunction "9_9") (pintype "bidirectional"))
      (node (ref "MICROCONTROLLER5") (pin "9") (pinfunction "9_9") (pintype "bidirectional"))
      (node (ref "R112") (pin "1") (pinfunction "1_1") (pintype "passive"))
      (node (ref "R24") (pin "1") (pinfunction "1_1") (pintype "passive"))
      (node (ref "R46") (pin "1") (pinfunction "1_1") (pintype "passive"))
      (node (ref "R68") (pin "1") (pinfunction "1_1") (pintype "passive"))
    )
    (net (code "18") (name "/SDA") (class "Default")
      (node (ref "IMU1") (pin "4") (pinfunction "SDA/SDI/SDO_4") (pintype "bidirectional"))
      (node (ref "IMU2") (pin "4") (pinfunction "SDA/SDI/SDO_4") (pintype "bidirectional"))
      (node (ref "IMU3") (pin "4") (pinfunction "SDA/SDI/SDO_4") (pintype "bidirectional"))
      (node (ref "IMU5") (pin "4") (pinfunction "SDA/SDI/SDO_4") (pintype "bidirectional"))
      (node (ref "MICROCONTROLLER1") (pin "10") (pinfunction "10_10") (pintype "bidirectional"))
      (node (ref "MICROCONTROLLER2") (pin "10") (pinfunction "10_10") (pintype "bidirectional"))
      (node (ref "MICROCONTROLLER3") (pin "10") (pinfunction "10_10") (pintype "bidirectional"))
      (node (ref "MICROCONTROLLER5") (pin "10") (pinfunction "10_10") (pintype "bidirectional"))
      (node (ref "R113") (pin "1") (pinfunction "1_1") (pintype "passive"))
      (node (ref "R25") (pin "1") (pinfunction "1_1") (pintype "passive"))
      (node (ref "R47") (pin "1") (pinfunction "1_1") (pintype "passive"))
      (node (ref "R69") (pin "1") (pinfunction "1_1") (pintype "passive"))
    )
    (net (code "19") (name "/SOLAR_CELLS") (class "Default")
      (node (ref "C137") (pin "1") (pinfunction "1_1") (pintype "passive"))
      (node (ref "C45") (pin "1") (pinfunction "1_1") (pintype "passive"))
      (node (ref "C68") (pin "1") (pinfunction "1_1") (pintype "passive"))
      (node (ref "C91") (pin "1") (pinfunction "1_1") (pintype "passive"))
      (node (ref "FRONT_PANEL1") (pin "+") (pinfunction "+_+") (pintype "passive"))
      (node (ref "FRONT_PANEL2") (pin "+") (pinfunction "+_+") (pintype "passive"))
      (node (ref "FRONT_PANEL3") (pin "+") (pinfunction "+_+") (pintype "passive"))
      (node (ref "FRONT_PANEL5") (pin "+") (pinfunction "+_+") (pintype "passive"))
      (node (ref "L12") (pin "2") (pinfunction "2_2") (pintype "passive"))
      (node (ref "L16") (pin "2") (pinfunction "2_2") (pintype "passive"))
      (node (ref "L24") (pin "2") (pinfunction "2_2") (pintype "passive"))
      (node (ref "L8") (pin "2") (pinfunction "2_2") (pintype "passive"))
      (node (ref "R130") (pin "2") (pinfunction "2_2") (pintype "passive"))
      (node (ref "R42") (pin "2") (pinfunction "2_2") (pintype "passive"))
      (node (ref "R64") (pin "2") (pinfunction "2_2") (pintype "passive"))
      (node (ref "R86") (pin "2") (pinfunction "2_2") (pintype "passive"))
      (node (ref "REAR_PANEL1") (pin "+") (pinfunction "+_+") (pintype "passive"))
      (node (ref "REAR_PANEL2") (pin "+") (pinfunction "+_+") (pintype "passive"))
      (node (ref "REAR_PANEL3") (pin "+") (pinfunction "+_+") (pintype "passive"))
      (node (ref "REAR_PANEL5") (pin "+") (pinfunction "+_+") (pintype "passive"))
    )
    (net (code "20") (name "/SWO") (class "Default")
      (node (ref "MICROCONTROLLER1") (pin "28") (pinfunction "28_28") (pintype "bidirectional"))
      (node (ref "MICROCONTROLLER2") (pin "28") (pinfunction "28_28") (pintype "bidirectional"))
      (node (ref "MICROCONTROLLER3") (pin "28") (pinfunction "28_28") (pintype "bidirectional"))
      (node (ref "MICROCONTROLLER5") (pin "28") (pinfunction "28_28") (pintype "bidirectional"))
      (node (ref "U$16") (pin "8") (pinfunction "8_8") (pintype "bidirectional"))
      (node (ref "U$16") (pin "9") (pinfunction "9_9") (pintype "bidirectional"))
      (node (ref "U$24") (pin "8") (pinfunction "8_8") (pintype "bidirectional"))
      (node (ref "U$24") (pin "9") (pinfunction "9_9") (pintype "bidirectional"))
      (node (ref "U$32") (pin "8") (pinfunction "8_8") (pintype "bidirectional"))
      (node (ref "U$32") (pin "9") (pinfunction "9_9") (pintype "bidirectional"))
      (node (ref "U$48") (pin "8") (pinfunction "8_8") (pintype "bidirectional"))
      (node (ref "U$48") (pin "9") (pinfunction "9_9") (pintype "bidirectional"))
    )
    (net (code "21") (name "/TDI") (class "Default")
      (node (ref "MICROCONTROLLER1") (pin "27") (pinfunction "27_27") (pintype "bidirectional"))
      (node (ref "MICROCONTROLLER2") (pin "27") (pinfunction "27_27") (pintype "bidirectional"))
      (node (ref "MICROCONTROLLER3") (pin "27") (pinfunction "27_27") (pintype "bidirectional"))
      (node (ref "MICROCONTROLLER5") (pin "27") (pinfunction "27_27") (pintype "bidirectional"))
      (node (ref "U$16") (pin "10") (pinfunction "10_10") (pintype "bidirectional"))
      (node (ref "U$16") (pin "11") (pinfunction "11_11") (pintype "bidirectional"))
      (node (ref "U$24") (pin "10") (pinfunction "10_10") (pintype "bidirectional"))
      (node (ref "U$24") (pin "11") (pinfunction "11_11") (pintype "bidirectional"))
      (node (ref "U$32") (pin "10") (pinfunction "10_10") (pintype "bidirectional"))
      (node (ref "U$32") (pin "11") (pinfunction "11_11") (pintype "bidirectional"))
      (node (ref "U$48") (pin "10") (pinfunction "10_10") (pintype "bidirectional"))
      (node (ref "U$48") (pin "11") (pinfunction "11_11") (pintype "bidirectional"))
    )
    (net (code "22") (name "/TDO") (class "Default")
      (node (ref "MICROCONTROLLER1") (pin "26") (pinfunction "26_26") (pintype "bidirectional"))
      (node (ref "MICROCONTROLLER2") (pin "26") (pinfunction "26_26") (pintype "bidirectional"))
      (node (ref "MICROCONTROLLER3") (pin "26") (pinfunction "26_26") (pintype "bidirectional"))
      (node (ref "MICROCONTROLLER5") (pin "26") (pinfunction "26_26") (pintype "bidirectional"))
      (node (ref "U$16") (pin "12") (pinfunction "12_12") (pintype "bidirectional"))
      (node (ref "U$16") (pin "13") (pinfunction "13_13") (pintype "bidirectional"))
      (node (ref "U$24") (pin "12") (pinfunction "12_12") (pintype "bidirectional"))
      (node (ref "U$24") (pin "13") (pinfunction "13_13") (pintype "bidirectional"))
      (node (ref "U$32") (pin "12") (pinfunction "12_12") (pintype "bidirectional"))
      (node (ref "U$32") (pin "13") (pinfunction "13_13") (pintype "bidirectional"))
      (node (ref "U$48") (pin "12") (pinfunction "12_12") (pintype "bidirectional"))
      (node (ref "U$48") (pin "13") (pinfunction "13_13") (pintype "bidirectional"))
    )
    (net (code "23") (name "/TXD") (class "Default")
      (node (ref "MICROCONTROLLER1") (pin "8") (pinfunction "8_8") (pintype "bidirectional"))
      (node (ref "MICROCONTROLLER2") (pin "8") (pinfunction "8_8") (pintype "bidirectional"))
      (node (ref "MICROCONTROLLER3") (pin "8") (pinfunction "8_8") (pintype "bidirectional"))
      (node (ref "MICROCONTROLLER5") (pin "8") (pinfunction "8_8") (pintype "bidirectional"))
      (node (ref "R119") (pin "2") (pinfunction "2_2") (pintype "passive"))
      (node (ref "R31") (pin "2") (pinfunction "2_2") (pintype "passive"))
      (node (ref "R53") (pin "2") (pinfunction "2_2") (pintype "passive"))
      (node (ref "R75") (pin "2") (pinfunction "2_2") (pintype "passive"))
      (node (ref "U$16") (pin "4") (pinfunction "4_4") (pintype "bidirectional"))
      (node (ref "U$16") (pin "5") (pinfunction "5_5") (pintype "bidirectional"))
      (node (ref "U$24") (pin "4") (pinfunction "4_4") (pintype "bidirectional"))
      (node (ref "U$24") (pin "5") (pinfunction "5_5") (pintype "bidirectional"))
      (node (ref "U$32") (pin "4") (pinfunction "4_4") (pintype "bidirectional"))
      (node (ref "U$32") (pin "5") (pinfunction "5_5") (pintype "bidirectional"))
      (node (ref "U$48") (pin "4") (pinfunction "4_4") (pintype "bidirectional"))
      (node (ref "U$48") (pin "5") (pinfunction "5_5") (pintype "bidirectional"))
    )
    (net (code "24") (name "/VDDR") (class "Default")
      (node (ref "C122") (pin "1") (pinfunction "1_1") (pintype "passive"))
      (node (ref "C123") (pin "1") (pinfunction "1_1") (pintype "passive"))
      (node (ref "C124") (pin "1") (pinfunction "1_1") (pintype "passive"))
      (node (ref "C30") (pin "1") (pinfunction "1_1") (pintype "passive"))
      (node (ref "C31") (pin "1") (pinfunction "1_1") (pintype "passive"))
      (node (ref "C32") (pin "1") (pinfunction "1_1") (pintype "passive"))
      (node (ref "C53") (pin "1") (pinfunction "1_1") (pintype "passive"))
      (node (ref "C54") (pin "1") (pinfunction "1_1") (pintype "passive"))
      (node (ref "C55") (pin "1") (pinfunction "1_1") (pintype "passive"))
      (node (ref "C76") (pin "1") (pinfunction "1_1") (pintype "passive"))
      (node (ref "C77") (pin "1") (pinfunction "1_1") (pintype "passive"))
      (node (ref "C78") (pin "1") (pinfunction "1_1") (pintype "passive"))
      (node (ref "L13") (pin "2") (pinfunction "2_2") (pintype "passive"))
      (node (ref "L21") (pin "2") (pinfunction "2_2") (pintype "passive"))
      (node (ref "L5") (pin "2") (pinfunction "2_2") (pintype "passive"))
      (node (ref "L9") (pin "2") (pinfunction "2_2") (pintype "passive"))
      (node (ref "MICROCONTROLLER1") (pin "45") (pinfunction "45_45") (pintype "power_in"))
      (node (ref "MICROCONTROLLER1") (pin "48") (pinfunction "48_48") (pintype "power_in"))
      (node (ref "MICROCONTROLLER2") (pin "45") (pinfunction "45_45") (pintype "power_in"))
      (node (ref "MICROCONTROLLER2") (pin "48") (pinfunction "48_48") (pintype "power_in"))
      (node (ref "MICROCONTROLLER3") (pin "45") (pinfunction "45_45") (pintype "power_in"))
      (node (ref "MICROCONTROLLER3") (pin "48") (pinfunction "48_48") (pintype "power_in"))
      (node (ref "MICROCONTROLLER5") (pin "45") (pinfunction "45_45") (pintype "power_in"))
      (node (ref "MICROCONTROLLER5") (pin "48") (pinfunction "48_48") (pintype "power_in"))
    )
    (net (code "25") (name "/VDDS") (class "Default")
      (node (ref "C117") (pin "1") (pinfunction "1_1") (pintype "passive"))
      (node (ref "C118") (pin "1") (pinfunction "1_1") (pintype "passive"))
      (node (ref "C119") (pin "1") (pinfunction "1_1") (pintype "passive"))
      (node (ref "C120") (pin "1") (pinfunction "1_1") (pintype "passive"))
      (node (ref "C121") (pin "1") (pinfunction "1_1") (pintype "passive"))
      (node (ref "C128") (pin "1") (pinfunction "1_1") (pintype "passive"))
      (node (ref "C129") (pin "1") (pinfunction "1_1") (pintype "passive"))
      (node (ref "C130") (pin "1") (pinfunction "1_1") (pintype "passive"))
      (node (ref "C136") (pin "1") (pinfunction "1_1") (pintype "passive"))
      (node (ref "C138") (pin "1") (pinfunction "1_1") (pintype "passive"))
      (node (ref "C24") (pin "1") (pinfunction "1_1") (pintype "passive"))
      (node (ref "C25") (pin "1") (pinfunction "1_1") (pintype "passive"))
      (node (ref "C27") (pin "1") (pinfunction "1_1") (pintype "passive"))
      (node (ref "C28") (pin "1") (pinfunction "1_1") (pintype "passive"))
      (node (ref "C29") (pin "1") (pinfunction "1_1") (pintype "passive"))
      (node (ref "C36") (pin "1") (pinfunction "1_1") (pintype "passive"))
      (node (ref "C37") (pin "1") (pinfunction "1_1") (pintype "passive"))
      (node (ref "C38") (pin "1") (pinfunction "1_1") (pintype "passive"))
      (node (ref "C44") (pin "1") (pinfunction "1_1") (pintype "passive"))
      (node (ref "C46") (pin "1") (pinfunction "1_1") (pintype "passive"))
      (node (ref "C48") (pin "1") (pinfunction "1_1") (pintype "passive"))
      (node (ref "C49") (pin "1") (pinfunction "1_1") (pintype "passive"))
      (node (ref "C50") (pin "1") (pinfunction "1_1") (pintype "passive"))
      (node (ref "C51") (pin "1") (pinfunction "1_1") (pintype "passive"))
      (node (ref "C52") (pin "1") (pinfunction "1_1") (pintype "passive"))
      (node (ref "C59") (pin "1") (pinfunction "1_1") (pintype "passive"))
      (node (ref "C60") (pin "1") (pinfunction "1_1") (pintype "passive"))
      (node (ref "C61") (pin "1") (pinfunction "1_1") (pintype "passive"))
      (node (ref "C67") (pin "1") (pinfunction "1_1") (pintype "passive"))
      (node (ref "C69") (pin "1") (pinfunction "1_1") (pintype "passive"))
      (node (ref "C71") (pin "1") (pinfunction "1_1") (pintype "passive"))
      (node (ref "C72") (pin "1") (pinfunction "1_1") (pintype "passive"))
      (node (ref "C73") (pin "1") (pinfunction "1_1") (pintype "passive"))
      (node (ref "C74") (pin "1") (pinfunction "1_1") (pintype "passive"))
      (node (ref "C75") (pin "1") (pinfunction "1_1") (pintype "passive"))
      (node (ref "C82") (pin "1") (pinfunction "1_1") (pintype "passive"))
      (node (ref "C83") (pin "1") (pinfunction "1_1") (pintype "passive"))
      (node (ref "C84") (pin "1") (pinfunction "1_1") (pintype "passive"))
      (node (ref "C90") (pin "1") (pinfunction "1_1") (pintype "passive"))
      (node (ref "C92") (pin "1") (pinfunction "1_1") (pintype "passive"))
      (node (ref "GPS1") (pin "18") (pinfunction "VBAT_18") (pintype "bidirectional"))
      (node (ref "GPS1") (pin "2") (pinfunction "VCC_2") (pintype "bidirectional"))
      (node (ref "GPS1") (pin "58") (pinfunction "VCC_58") (pintype "bidirectional"))
      (node (ref "GPS2") (pin "18") (pinfunction "VBAT_18") (pintype "bidirectional"))
      (node (ref "GPS2") (pin "2") (pinfunction "VCC_2") (pintype "bidirectional"))
      (node (ref "GPS2") (pin "58") (pinfunction "VCC_58") (pintype "bidirectional"))
      (node (ref "GPS3") (pin "18") (pinfunction "VBAT_18") (pintype "bidirectional"))
      (node (ref "GPS3") (pin "2") (pinfunction "VCC_2") (pintype "bidirectional"))
      (node (ref "GPS3") (pin "58") (pinfunction "VCC_58") (pintype "bidirectional"))
      (node (ref "GPS5") (pin "18") (pinfunction "VBAT_18") (pintype "bidirectional"))
      (node (ref "GPS5") (pin "2") (pinfunction "VCC_2") (pintype "bidirectional"))
      (node (ref "GPS5") (pin "58") (pinfunction "VCC_58") (pintype "bidirectional"))
      (node (ref "IMU1") (pin "1") (pinfunction "VDDIO_1") (pintype "bidirectional"))
      (node (ref "IMU1") (pin "22") (pinfunction "VDD_22") (pintype "bidirectional"))
      (node (ref "IMU1") (pin "23") (pinfunction "VDD_23") (pintype "bidirectional"))
      (node (ref "IMU1") (pin "3") (pinfunction "VDDIO_3") (pintype "bidirectional"))
      (node (ref "IMU2") (pin "1") (pinfunction "VDDIO_1") (pintype "bidirectional"))
      (node (ref "IMU2") (pin "22") (pinfunction "VDD_22") (pintype "bidirectional"))
      (node (ref "IMU2") (pin "23") (pinfunction "VDD_23") (pintype "bidirectional"))
      (node (ref "IMU2") (pin "3") (pinfunction "VDDIO_3") (pintype "bidirectional"))
      (node (ref "IMU3") (pin "1") (pinfunction "VDDIO_1") (pintype "bidirectional"))
      (node (ref "IMU3") (pin "22") (pinfunction "VDD_22") (pintype "bidirectional"))
      (node (ref "IMU3") (pin "23") (pinfunction "VDD_23") (pintype "bidirectional"))
      (node (ref "IMU3") (pin "3") (pinfunction "VDDIO_3") (pintype "bidirectional"))
      (node (ref "IMU5") (pin "1") (pinfunction "VDDIO_1") (pintype "bidirectional"))
      (node (ref "IMU5") (pin "22") (pinfunction "VDD_22") (pintype "bidirectional"))
      (node (ref "IMU5") (pin "23") (pinfunction "VDD_23") (pintype "bidirectional"))
      (node (ref "IMU5") (pin "3") (pinfunction "VDDIO_3") (pintype "bidirectional"))
      (node (ref "LED12") (pin "A") (pinfunction "A_A") (pintype "passive"))
      (node (ref "LED18") (pin "A") (pinfunction "A_A") (pintype "passive"))
      (node (ref "LED6") (pin "A") (pinfunction "A_A") (pintype "passive"))
      (node (ref "LED9") (pin "A") (pinfunction "A_A") (pintype "passive"))
      (node (ref "LS11") (pin "C") (pinfunction "C1_C") (pintype "passive"))
      (node (ref "LS12") (pin "C") (pinfunction "C1_C") (pintype "passive"))
      (node (ref "LS3") (pin "C") (pinfunction "C1_C") (pintype "passive"))
      (node (ref "LS4") (pin "C") (pinfunction "C1_C") (pintype "passive"))
      (node (ref "LS5") (pin "C") (pinfunction "C1_C") (pintype "passive"))
      (node (ref "LS6") (pin "C") (pinfunction "C1_C") (pintype "passive"))
      (node (ref "LS7") (pin "C") (pinfunction "C1_C") (pintype "passive"))
      (node (ref "LS8") (pin "C") (pinfunction "C1_C") (pintype "passive"))
      (node (ref "MICROCONTROLLER1") (pin "13") (pinfunction "13_13") (pintype "bidirectional"))
      (node (ref "MICROCONTROLLER1") (pin "22") (pinfunction "22_22") (pintype "power_in"))
      (node (ref "MICROCONTROLLER1") (pin "34") (pinfunction "34_34") (pintype "power_in"))
      (node (ref "MICROCONTROLLER1") (pin "44") (pinfunction "44_44") (pintype "power_in"))
      (node (ref "MICROCONTROLLER2") (pin "13") (pinfunction "13_13") (pintype "bidirectional"))
      (node (ref "MICROCONTROLLER2") (pin "22") (pinfunction "22_22") (pintype "power_in"))
      (node (ref "MICROCONTROLLER2") (pin "34") (pinfunction "34_34") (pintype "power_in"))
      (node (ref "MICROCONTROLLER2") (pin "44") (pinfunction "44_44") (pintype "power_in"))
      (node (ref "MICROCONTROLLER3") (pin "13") (pinfunction "13_13") (pintype "bidirectional"))
      (node (ref "MICROCONTROLLER3") (pin "22") (pinfunction "22_22") (pintype "power_in"))
      (node (ref "MICROCONTROLLER3") (pin "34") (pinfunction "34_34") (pintype "power_in"))
      (node (ref "MICROCONTROLLER3") (pin "44") (pinfunction "44_44") (pintype "power_in"))
      (node (ref "MICROCONTROLLER5") (pin "13") (pinfunction "13_13") (pintype "bidirectional"))
      (node (ref "MICROCONTROLLER5") (pin "22") (pinfunction "22_22") (pintype "power_in"))
      (node (ref "MICROCONTROLLER5") (pin "34") (pinfunction "34_34") (pintype "power_in"))
      (node (ref "MICROCONTROLLER5") (pin "44") (pinfunction "44_44") (pintype "power_in"))
      (node (ref "R111") (pin "2") (pinfunction "2_2") (pintype "passive"))
      (node (ref "R112") (pin "2") (pinfunction "2_2") (pintype "passive"))
      (node (ref "R113") (pin "2") (pinfunction "2_2") (pintype "passive"))
      (node (ref "R116") (pin "1") (pinfunction "1_1") (pintype "passive"))
      (node (ref "R121") (pin "2") (pinfunction "2_2") (pintype "passive"))
      (node (ref "R122") (pin "1") (pinfunction "1_1") (pintype "passive"))
      (node (ref "R123") (pin "2") (pinfunction "2_2") (pintype "passive"))
      (node (ref "R23") (pin "2") (pinfunction "2_2") (pintype "passive"))
      (node (ref "R24") (pin "2") (pinfunction "2_2") (pintype "passive"))
      (node (ref "R25") (pin "2") (pinfunction "2_2") (pintype "passive"))
      (node (ref "R28") (pin "1") (pinfunction "1_1") (pintype "passive"))
      (node (ref "R33") (pin "2") (pinfunction "2_2") (pintype "passive"))
      (node (ref "R34") (pin "1") (pinfunction "1_1") (pintype "passive"))
      (node (ref "R35") (pin "2") (pinfunction "2_2") (pintype "passive"))
      (node (ref "R45") (pin "2") (pinfunction "2_2") (pintype "passive"))
      (node (ref "R46") (pin "2") (pinfunction "2_2") (pintype "passive"))
      (node (ref "R47") (pin "2") (pinfunction "2_2") (pintype "passive"))
      (node (ref "R50") (pin "1") (pinfunction "1_1") (pintype "passive"))
      (node (ref "R55") (pin "2") (pinfunction "2_2") (pintype "passive"))
      (node (ref "R56") (pin "1") (pinfunction "1_1") (pintype "passive"))
      (node (ref "R57") (pin "2") (pinfunction "2_2") (pintype "passive"))
      (node (ref "R67") (pin "2") (pinfunction "2_2") (pintype "passive"))
      (node (ref "R68") (pin "2") (pinfunction "2_2") (pintype "passive"))
      (node (ref "R69") (pin "2") (pinfunction "2_2") (pintype "passive"))
      (node (ref "R72") (pin "1") (pinfunction "1_1") (pintype "passive"))
      (node (ref "R77") (pin "2") (pinfunction "2_2") (pintype "passive"))
      (node (ref "R78") (pin "1") (pinfunction "1_1") (pintype "passive"))
      (node (ref "R79") (pin "2") (pinfunction "2_2") (pintype "passive"))
      (node (ref "U$1") (pin "VCC") (pinfunction "VCC_VCC") (pintype "bidirectional"))
      (node (ref "U$1") (pin "VM") (pinfunction "VM_VM") (pintype "bidirectional"))
      (node (ref "U$11") (pin "VCC") (pinfunction "VCC_VCC") (pintype "bidirectional"))
      (node (ref "U$15") (pin "1") (pinfunction "FB_1") (pintype "bidirectional"))
      (node (ref "U$15") (pin "8") (pinfunction "OUT_8") (pintype "bidirectional"))
      (node (ref "U$16") (pin "18") (pinfunction "18_18") (pintype "bidirectional"))
      (node (ref "U$16") (pin "19") (pinfunction "19_19") (pintype "bidirectional"))
      (node (ref "U$17") (pin "VCC") (pinfunction "VCC_VCC") (pintype "bidirectional"))
      (node (ref "U$17") (pin "VM") (pinfunction "VM_VM") (pintype "bidirectional"))
      (node (ref "U$19") (pin "VCC") (pinfunction "VCC_VCC") (pintype "bidirectional"))
      (node (ref "U$23") (pin "1") (pinfunction "FB_1") (pintype "bidirectional"))
      (node (ref "U$23") (pin "8") (pinfunction "OUT_8") (pintype "bidirectional"))
      (node (ref "U$24") (pin "18") (pinfunction "18_18") (pintype "bidirectional"))
      (node (ref "U$24") (pin "19") (pinfunction "19_19") (pintype "bidirectional"))
      (node (ref "U$25") (pin "VCC") (pinfunction "VCC_VCC") (pintype "bidirectional"))
      (node (ref "U$25") (pin "VM") (pinfunction "VM_VM") (pintype "bidirectional"))
      (node (ref "U$27") (pin "VCC") (pinfunction "VCC_VCC") (pintype "bidirectional"))
      (node (ref "U$31") (pin "1") (pinfunction "FB_1") (pintype "bidirectional"))
      (node (ref "U$31") (pin "8") (pinfunction "OUT_8") (pintype "bidirectional"))
      (node (ref "U$32") (pin "18") (pinfunction "18_18") (pintype "bidirectional"))
      (node (ref "U$32") (pin "19") (pinfunction "19_19") (pintype "bidirectional"))
      (node (ref "U$41") (pin "VCC") (pinfunction "VCC_VCC") (pintype "bidirectional"))
      (node (ref "U$41") (pin "VM") (pinfunction "VM_VM") (pintype "bidirectional"))
      (node (ref "U$43") (pin "VCC") (pinfunction "VCC_VCC") (pintype "bidirectional"))
      (node (ref "U$47") (pin "1") (pinfunction "FB_1") (pintype "bidirectional"))
      (node (ref "U$47") (pin "8") (pinfunction "OUT_8") (pintype "bidirectional"))
      (node (ref "U$48") (pin "18") (pinfunction "18_18") (pintype "bidirectional"))
      (node (ref "U$48") (pin "19") (pinfunction "19_19") (pintype "bidirectional"))
    )
    (net (code "26") (name "/X24M_N") (class "Default")
      (node (ref "MICROCONTROLLER1") (pin "46") (pinfunction "46_46") (pintype "bidirectional"))
      (node (ref "MICROCONTROLLER2") (pin "46") (pinfunction "46_46") (pintype "bidirectional"))
      (node (ref "MICROCONTROLLER3") (pin "46") (pinfunction "46_46") (pintype "bidirectional"))
      (node (ref "MICROCONTROLLER5") (pin "46") (pinfunction "46_46") (pintype "bidirectional"))
      (node (ref "TSX1") (pin "3") (pinfunction "3_3") (pintype "bidirectional"))
      (node (ref "TSX2") (pin "3") (pinfunction "3_3") (pintype "bidirectional"))
      (node (ref "TSX3") (pin "3") (pinfunction "3_3") (pintype "bidirectional"))
      (node (ref "TSX5") (pin "3") (pinfunction "3_3") (pintype "bidirectional"))
    )
    (net (code "27") (name "/X24M_P") (class "Default")
      (node (ref "MICROCONTROLLER1") (pin "47") (pinfunction "47_47") (pintype "input"))
      (node (ref "MICROCONTROLLER2") (pin "47") (pinfunction "47_47") (pintype "input"))
      (node (ref "MICROCONTROLLER3") (pin "47") (pinfunction "47_47") (pintype "input"))
      (node (ref "MICROCONTROLLER5") (pin "47") (pinfunction "47_47") (pintype "input"))
      (node (ref "TSX1") (pin "1") (pinfunction "1_1") (pintype "bidirectional"))
      (node (ref "TSX2") (pin "1") (pinfunction "1_1") (pintype "bidirectional"))
      (node (ref "TSX3") (pin "1") (pinfunction "1_1") (pintype "bidirectional"))
      (node (ref "TSX5") (pin "1") (pinfunction "1_1") (pintype "bidirectional"))
    )
    (net (code "28") (name "GND") (class "Default")
      (node (ref "BALUN1") (pin "5") (pinfunction "GND_5") (pintype "bidirectional"))
      (node (ref "BALUN1") (pin "6") (pinfunction "GND_6") (pintype "bidirectional"))
      (node (ref "BALUN2") (pin "5") (pinfunction "GND_5") (pintype "bidirectional"))
      (node (ref "BALUN2") (pin "6") (pinfunction "GND_6") (pintype "bidirectional"))
      (node (ref "BALUN3") (pin "5") (pinfunction "GND_5") (pintype "bidirectional"))
      (node (ref "BALUN3") (pin "6") (pinfunction "GND_6") (pintype "bidirectional"))
      (node (ref "BALUN5") (pin "5") (pinfunction "GND_5") (pintype "bidirectional"))
      (node (ref "BALUN5") (pin "6") (pinfunction "GND_6") (pintype "bidirectional"))
      (node (ref "C116") (pin "2") (pinfunction "2_2") (pintype "passive"))
      (node (ref "C117") (pin "2") (pinfunction "2_2") (pintype "passive"))
      (node (ref "C118") (pin "2") (pinfunction "2_2") (pintype "passive"))
      (node (ref "C119") (pin "2") (pinfunction "2_2") (pintype "passive"))
      (node (ref "C120") (pin "2") (pinfunction "2_2") (pintype "passive"))
      (node (ref "C121") (pin "2") (pinfunction "2_2") (pintype "passive"))
      (node (ref "C122") (pin "2") (pinfunction "2_2") (pintype "passive"))
      (node (ref "C123") (pin "2") (pinfunction "2_2") (pintype "passive"))
      (node (ref "C124") (pin "2") (pinfunction "2_2") (pintype "passive"))
      (node (ref "C125") (pin "2") (pinfunction "2_2") (pintype "passive"))
      (node (ref "C126") (pin "2") (pinfunction "2_2") (pintype "passive"))
      (node (ref "C127") (pin "2") (pinfunction "2_2") (pintype "passive"))
      (node (ref "C128") (pin "2") (pinfunction "2_2") (pintype "passive"))
      (node (ref "C129") (pin "2") (pinfunction "2_2") (pintype "passive"))
      (node (ref "C130") (pin "2") (pinfunction "2_2") (pintype "passive"))
      (node (ref "C131") (pin "2") (pinfunction "2_2") (pintype "passive"))
      (node (ref "C132") (pin "2") (pinfunction "2_2") (pintype "passive"))
      (node (ref "C133") (pin "2") (pinfunction "2_2") (pintype "passive"))
      (node (ref "C135") (pin "1") (pinfunction "1_1") (pintype "passive"))
      (node (ref "C136") (pin "2") (pinfunction "2_2") (pintype "passive"))
      (node (ref "C137") (pin "2") (pinfunction "2_2") (pintype "passive"))
      (node (ref "C138") (pin "2") (pinfunction "2_2") (pintype "passive"))
      (node (ref "C21") (pin "2") (pinfunction "2_2") (pintype "passive"))
      (node (ref "C24") (pin "2") (pinfunction "2_2") (pintype "passive"))
      (node (ref "C25") (pin "2") (pinfunction "2_2") (pintype "passive"))
      (node (ref "C27") (pin "2") (pinfunction "2_2") (pintype "passive"))
      (node (ref "C28") (pin "2") (pinfunction "2_2") (pintype "passive"))
      (node (ref "C29") (pin "2") (pinfunction "2_2") (pintype "passive"))
      (node (ref "C30") (pin "2") (pinfunction "2_2") (pintype "passive"))
      (node (ref "C31") (pin "2") (pinfunction "2_2") (pintype "passive"))
      (node (ref "C32") (pin "2") (pinfunction "2_2") (pintype "passive"))
      (node (ref "C33") (pin "2") (pinfunction "2_2") (pintype "passive"))
      (node (ref "C34") (pin "2") (pinfunction "2_2") (pintype "passive"))
      (node (ref "C35") (pin "2") (pinfunction "2_2") (pintype "passive"))
      (node (ref "C36") (pin "2") (pinfunction "2_2") (pintype "passive"))
      (node (ref "C37") (pin "2") (pinfunction "2_2") (pintype "passive"))
      (node (ref "C38") (pin "2") (pinfunction "2_2") (pintype "passive"))
      (node (ref "C39") (pin "2") (pinfunction "2_2") (pintype "passive"))
      (node (ref "C40") (pin "2") (pinfunction "2_2") (pintype "passive"))
      (node (ref "C41") (pin "2") (pinfunction "2_2") (pintype "passive"))
      (node (ref "C43") (pin "1") (pinfunction "1_1") (pintype "passive"))
      (node (ref "C44") (pin "2") (pinfunction "2_2") (pintype "passive"))
      (node (ref "C45") (pin "2") (pinfunction "2_2") (pintype "passive"))
      (node (ref "C46") (pin "2") (pinfunction "2_2") (pintype "passive"))
      (node (ref "C47") (pin "2") (pinfunction "2_2") (pintype "passive"))
      (node (ref "C48") (pin "2") (pinfunction "2_2") (pintype "passive"))
      (node (ref "C49") (pin "2") (pinfunction "2_2") (pintype "passive"))
      (node (ref "C50") (pin "2") (pinfunction "2_2") (pintype "passive"))
      (node (ref "C51") (pin "2") (pinfunction "2_2") (pintype "passive"))
      (node (ref "C52") (pin "2") (pinfunction "2_2") (pintype "passive"))
      (node (ref "C53") (pin "2") (pinfunction "2_2") (pintype "passive"))
      (node (ref "C54") (pin "2") (pinfunction "2_2") (pintype "passive"))
      (node (ref "C55") (pin "2") (pinfunction "2_2") (pintype "passive"))
      (node (ref "C56") (pin "2") (pinfunction "2_2") (pintype "passive"))
      (node (ref "C57") (pin "2") (pinfunction "2_2") (pintype "passive"))
      (node (ref "C58") (pin "2") (pinfunction "2_2") (pintype "passive"))
      (node (ref "C59") (pin "2") (pinfunction "2_2") (pintype "passive"))
      (node (ref "C60") (pin "2") (pinfunction "2_2") (pintype "passive"))
      (node (ref "C61") (pin "2") (pinfunction "2_2") (pintype "passive"))
      (node (ref "C62") (pin "2") (pinfunction "2_2") (pintype "passive"))
      (node (ref "C63") (pin "2") (pinfunction "2_2") (pintype "passive"))
      (node (ref "C64") (pin "2") (pinfunction "2_2") (pintype "passive"))
      (node (ref "C66") (pin "1") (pinfunction "1_1") (pintype "passive"))
      (node (ref "C67") (pin "2") (pinfunction "2_2") (pintype "passive"))
      (node (ref "C68") (pin "2") (pinfunction "2_2") (pintype "passive"))
      (node (ref "C69") (pin "2") (pinfunction "2_2") (pintype "passive"))
      (node (ref "C70") (pin "2") (pinfunction "2_2") (pintype "passive"))
      (node (ref "C71") (pin "2") (pinfunction "2_2") (pintype "passive"))
      (node (ref "C72") (pin "2") (pinfunction "2_2") (pintype "passive"))
      (node (ref "C73") (pin "2") (pinfunction "2_2") (pintype "passive"))
      (node (ref "C74") (pin "2") (pinfunction "2_2") (pintype "passive"))
      (node (ref "C75") (pin "2") (pinfunction "2_2") (pintype "passive"))
      (node (ref "C76") (pin "2") (pinfunction "2_2") (pintype "passive"))
      (node (ref "C77") (pin "2") (pinfunction "2_2") (pintype "passive"))
      (node (ref "C78") (pin "2") (pinfunction "2_2") (pintype "passive"))
      (node (ref "C79") (pin "2") (pinfunction "2_2") (pintype "passive"))
      (node (ref "C80") (pin "2") (pinfunction "2_2") (pintype "passive"))
      (node (ref "C81") (pin "2") (pinfunction "2_2") (pintype "passive"))
      (node (ref "C82") (pin "2") (pinfunction "2_2") (pintype "passive"))
      (node (ref "C83") (pin "2") (pinfunction "2_2") (pintype "passive"))
      (node (ref "C84") (pin "2") (pinfunction "2_2") (pintype "passive"))
      (node (ref "C85") (pin "2") (pinfunction "2_2") (pintype "passive"))
      (node (ref "C86") (pin "2") (pinfunction "2_2") (pintype "passive"))
      (node (ref "C87") (pin "2") (pinfunction "2_2") (pintype "passive"))
      (node (ref "C89") (pin "1") (pinfunction "1_1") (pintype "passive"))
      (node (ref "C90") (pin "2") (pinfunction "2_2") (pintype "passive"))
      (node (ref "C91") (pin "2") (pinfunction "2_2") (pintype "passive"))
      (node (ref "C92") (pin "2") (pinfunction "2_2") (pintype "passive"))
      (node (ref "FRONT_PANEL1") (pin "-") (pinfunction "-_-") (pintype "passive"))
      (node (ref "FRONT_PANEL2") (pin "-") (pinfunction "-_-") (pintype "passive"))
      (node (ref "FRONT_PANEL3") (pin "-") (pinfunction "-_-") (pintype "passive"))
      (node (ref "FRONT_PANEL5") (pin "-") (pinfunction "-_-") (pintype "passive"))
      (node (ref "GPS1") (pin "10") (pinfunction "GND_10") (pintype "bidirectional"))
      (node (ref "GPS1") (pin "11") (pinfunction "GND_11") (pintype "bidirectional"))
      (node (ref "GPS1") (pin "15") (pinfunction "GND_15") (pintype "bidirectional"))
      (node (ref "GPS1") (pin "19") (pinfunction "GND_19") (pintype "bidirectional"))
      (node (ref "GPS1") (pin "21") (pinfunction "GNDRF_21") (pintype "bidirectional"))
      (node (ref "GPS1") (pin "22") (pinfunction "GNDRF_22") (pintype "bidirectional"))
      (node (ref "GPS1") (pin "24") (pinfunction "GNDRF_24") (pintype "bidirectional"))
      (node (ref "GPS1") (pin "25") (pinfunction "GNDRF_25") (pintype "bidirectional"))
      (node (ref "GPS1") (pin "27") (pinfunction "GNDRF_27") (pintype "bidirectional"))
      (node (ref "GPS1") (pin "28") (pinfunction "GNDRF_28") (pintype "bidirectional"))
      (node (ref "GPS1") (pin "29") (pinfunction "GNDRF_29") (pintype "bidirectional"))
      (node (ref "GPS1") (pin "31") (pinfunction "GNDRF_31") (pintype "bidirectional"))
      (node (ref "GPS1") (pin "33") (pinfunction "GNDRF_33") (pintype "bidirectional"))
      (node (ref "GPS1") (pin "49") (pinfunction "GND_49") (pintype "bidirectional"))
      (node (ref "GPS1") (pin "60") (pinfunction "GND_60") (pintype "bidirectional"))
      (node (ref "GPS1") (pin "61") (pinfunction "GNDRF_61") (pintype "bidirectional"))
      (node (ref "GPS1") (pin "62") (pinfunction "GNDRF_62") (pintype "bidirectional"))
      (node (ref "GPS1") (pin "64") (pinfunction "GND_64") (pintype "bidirectional"))
      (node (ref "GPS1") (pin "65") (pinfunction "GNDRF_65") (pintype "bidirectional"))
      (node (ref "GPS1") (pin "69") (pinfunction "GNDRF_69") (pintype "bidirectional"))
      (node (ref "GPS2") (pin "10") (pinfunction "GND_10") (pintype "bidirectional"))
      (node (ref "GPS2") (pin "11") (pinfunction "GND_11") (pintype "bidirectional"))
      (node (ref "GPS2") (pin "15") (pinfunction "GND_15") (pintype "bidirectional"))
      (node (ref "GPS2") (pin "19") (pinfunction "GND_19") (pintype "bidirectional"))
      (node (ref "GPS2") (pin "21") (pinfunction "GNDRF_21") (pintype "bidirectional"))
      (node (ref "GPS2") (pin "22") (pinfunction "GNDRF_22") (pintype "bidirectional"))
      (node (ref "GPS2") (pin "24") (pinfunction "GNDRF_24") (pintype "bidirectional"))
      (node (ref "GPS2") (pin "25") (pinfunction "GNDRF_25") (pintype "bidirectional"))
      (node (ref "GPS2") (pin "27") (pinfunction "GNDRF_27") (pintype "bidirectional"))
      (node (ref "GPS2") (pin "28") (pinfunction "GNDRF_28") (pintype "bidirectional"))
      (node (ref "GPS2") (pin "29") (pinfunction "GNDRF_29") (pintype "bidirectional"))
      (node (ref "GPS2") (pin "31") (pinfunction "GNDRF_31") (pintype "bidirectional"))
      (node (ref "GPS2") (pin "33") (pinfunction "GNDRF_33") (pintype "bidirectional"))
      (node (ref "GPS2") (pin "49") (pinfunction "GND_49") (pintype "bidirectional"))
      (node (ref "GPS2") (pin "60") (pinfunction "GND_60") (pintype "bidirectional"))
      (node (ref "GPS2") (pin "61") (pinfunction "GNDRF_61") (pintype "bidirectional"))
      (node (ref "GPS2") (pin "62") (pinfunction "GNDRF_62") (pintype "bidirectional"))
      (node (ref "GPS2") (pin "64") (pinfunction "GND_64") (pintype "bidirectional"))
      (node (ref "GPS2") (pin "65") (pinfunction "GNDRF_65") (pintype "bidirectional"))
      (node (ref "GPS2") (pin "69") (pinfunction "GNDRF_69") (pintype "bidirectional"))
      (node (ref "GPS3") (pin "10") (pinfunction "GND_10") (pintype "bidirectional"))
      (node (ref "GPS3") (pin "11") (pinfunction "GND_11") (pintype "bidirectional"))
      (node (ref "GPS3") (pin "15") (pinfunction "GND_15") (pintype "bidirectional"))
      (node (ref "GPS3") (pin "19") (pinfunction "GND_19") (pintype "bidirectional"))
      (node (ref "GPS3") (pin "21") (pinfunction "GNDRF_21") (pintype "bidirectional"))
      (node (ref "GPS3") (pin "22") (pinfunction "GNDRF_22") (pintype "bidirectional"))
      (node (ref "GPS3") (pin "24") (pinfunction "GNDRF_24") (pintype "bidirectional"))
      (node (ref "GPS3") (pin "25") (pinfunction "GNDRF_25") (pintype "bidirectional"))
      (node (ref "GPS3") (pin "27") (pinfunction "GNDRF_27") (pintype "bidirectional"))
      (node (ref "GPS3") (pin "28") (pinfunction "GNDRF_28") (pintype "bidirectional"))
      (node (ref "GPS3") (pin "29") (pinfunction "GNDRF_29") (pintype "bidirectional"))
      (node (ref "GPS3") (pin "31") (pinfunction "GNDRF_31") (pintype "bidirectional"))
      (node (ref "GPS3") (pin "33") (pinfunction "GNDRF_33") (pintype "bidirectional"))
      (node (ref "GPS3") (pin "49") (pinfunction "GND_49") (pintype "bidirectional"))
      (node (ref "GPS3") (pin "60") (pinfunction "GND_60") (pintype "bidirectional"))
      (node (ref "GPS3") (pin "61") (pinfunction "GNDRF_61") (pintype "bidirectional"))
      (node (ref "GPS3") (pin "62") (pinfunction "GNDRF_62") (pintype "bidirectional"))
      (node (ref "GPS3") (pin "64") (pinfunction "GND_64") (pintype "bidirectional"))
      (node (ref "GPS3") (pin "65") (pinfunction "GNDRF_65") (pintype "bidirectional"))
      (node (ref "GPS3") (pin "69") (pinfunction "GNDRF_69") (pintype "bidirectional"))
      (node (ref "GPS5") (pin "10") (pinfunction "GND_10") (pintype "bidirectional"))
      (node (ref "GPS5") (pin "11") (pinfunction "GND_11") (pintype "bidirectional"))
      (node (ref "GPS5") (pin "15") (pinfunction "GND_15") (pintype "bidirectional"))
      (node (ref "GPS5") (pin "19") (pinfunction "GND_19") (pintype "bidirectional"))
      (node (ref "GPS5") (pin "21") (pinfunction "GNDRF_21") (pintype "bidirectional"))
      (node (ref "GPS5") (pin "22") (pinfunction "GNDRF_22") (pintype "bidirectional"))
      (node (ref "GPS5") (pin "24") (pinfunction "GNDRF_24") (pintype "bidirectional"))
      (node (ref "GPS5") (pin "25") (pinfunction "GNDRF_25") (pintype "bidirectional"))
      (node (ref "GPS5") (pin "27") (pinfunction "GNDRF_27") (pintype "bidirectional"))
      (node (ref "GPS5") (pin "28") (pinfunction "GNDRF_28") (pintype "bidirectional"))
      (node (ref "GPS5") (pin "29") (pinfunction "GNDRF_29") (pintype "bidirectional"))
      (node (ref "GPS5") (pin "31") (pinfunction "GNDRF_31") (pintype "bidirectional"))
      (node (ref "GPS5") (pin "33") (pinfunction "GNDRF_33") (pintype "bidirectional"))
      (node (ref "GPS5") (pin "49") (pinfunction "GND_49") (pintype "bidirectional"))
      (node (ref "GPS5") (pin "60") (pinfunction "GND_60") (pintype "bidirectional"))
      (node (ref "GPS5") (pin "61") (pinfunction "GNDRF_61") (pintype "bidirectional"))
      (node (ref "GPS5") (pin "62") (pinfunction "GNDRF_62") (pintype "bidirectional"))
      (node (ref "GPS5") (pin "64") (pinfunction "GND_64") (pintype "bidirectional"))
      (node (ref "GPS5") (pin "65") (pinfunction "GNDRF_65") (pintype "bidirectional"))
      (node (ref "GPS5") (pin "69") (pinfunction "GNDRF_69") (pintype "bidirectional"))
      (node (ref "IMU1") (pin "14") (pinfunction "RES_14") (pintype "bidirectional"))
      (node (ref "IMU1") (pin "15") (pinfunction "RES_15") (pintype "bidirectional"))
      (node (ref "IMU1") (pin "16") (pinfunction "RES_16") (pintype "bidirectional"))
      (node (ref "IMU1") (pin "17") (pinfunction "RES_17") (pintype "bidirectional"))
      (node (ref "IMU1") (pin "18") (pinfunction "RES_18") (pintype "bidirectional"))
      (node (ref "IMU1") (pin "19") (pinfunction "GND_19") (pintype "bidirectional"))
      (node (ref "IMU1") (pin "20") (pinfunction "GND_20") (pintype "bidirectional"))
      (node (ref "IMU2") (pin "14") (pinfunction "RES_14") (pintype "bidirectional"))
      (node (ref "IMU2") (pin "15") (pinfunction "RES_15") (pintype "bidirectional"))
      (node (ref "IMU2") (pin "16") (pinfunction "RES_16") (pintype "bidirectional"))
      (node (ref "IMU2") (pin "17") (pinfunction "RES_17") (pintype "bidirectional"))
      (node (ref "IMU2") (pin "18") (pinfunction "RES_18") (pintype "bidirectional"))
      (node (ref "IMU2") (pin "19") (pinfunction "GND_19") (pintype "bidirectional"))
      (node (ref "IMU2") (pin "20") (pinfunction "GND_20") (pintype "bidirectional"))
      (node (ref "IMU3") (pin "14") (pinfunction "RES_14") (pintype "bidirectional"))
      (node (ref "IMU3") (pin "15") (pinfunction "RES_15") (pintype "bidirectional"))
      (node (ref "IMU3") (pin "16") (pinfunction "RES_16") (pintype "bidirectional"))
      (node (ref "IMU3") (pin "17") (pinfunction "RES_17") (pintype "bidirectional"))
      (node (ref "IMU3") (pin "18") (pinfunction "RES_18") (pintype "bidirectional"))
      (node (ref "IMU3") (pin "19") (pinfunction "GND_19") (pintype "bidirectional"))
      (node (ref "IMU3") (pin "20") (pinfunction "GND_20") (pintype "bidirectional"))
      (node (ref "IMU5") (pin "14") (pinfunction "RES_14") (pintype "bidirectional"))
      (node (ref "IMU5") (pin "15") (pinfunction "RES_15") (pintype "bidirectional"))
      (node (ref "IMU5") (pin "16") (pinfunction "RES_16") (pintype "bidirectional"))
      (node (ref "IMU5") (pin "17") (pinfunction "RES_17") (pintype "bidirectional"))
      (node (ref "IMU5") (pin "18") (pinfunction "RES_18") (pintype "bidirectional"))
      (node (ref "IMU5") (pin "19") (pinfunction "GND_19") (pintype "bidirectional"))
      (node (ref "IMU5") (pin "20") (pinfunction "GND_20") (pintype "bidirectional"))
      (node (ref "L10") (pin "2") (pinfunction "2_2") (pintype "passive"))
      (node (ref "L11") (pin "1") (pinfunction "1_1") (pintype "passive"))
      (node (ref "L14") (pin "2") (pinfunction "2_2") (pintype "passive"))
      (node (ref "L15") (pin "1") (pinfunction "1_1") (pintype "passive"))
      (node (ref "L22") (pin "2") (pinfunction "2_2") (pintype "passive"))
      (node (ref "L23") (pin "1") (pinfunction "1_1") (pintype "passive"))
      (node (ref "L6") (pin "2") (pinfunction "2_2") (pintype "passive"))
      (node (ref "L7") (pin "1") (pinfunction "1_1") (pintype "passive"))
      (node (ref "LED10") (pin "C") (pinfunction "C_C") (pintype "passive"))
      (node (ref "LED11") (pin "C") (pinfunction "C_C") (pintype "passive"))
      (node (ref "LED16") (pin "C") (pinfunction "C_C") (pintype "passive"))
      (node (ref "LED17") (pin "C") (pinfunction "C_C") (pintype "passive"))
      (node (ref "LED4") (pin "C") (pinfunction "C_C") (pintype "passive"))
      (node (ref "LED5") (pin "C") (pinfunction "C_C") (pintype "passive"))
      (node (ref "LED7") (pin "C") (pinfunction "C_C") (pintype "passive"))
      (node (ref "LED8") (pin "C") (pinfunction "C_C") (pintype "passive"))
      (node (ref "MICROCONTROLLER1") (pin "32") (pinfunction "32_32") (pintype "bidirectional"))
      (node (ref "MICROCONTROLLER1") (pin "49") (pinfunction "49_49") (pintype "input"))
      (node (ref "MICROCONTROLLER2") (pin "32") (pinfunction "32_32") (pintype "bidirectional"))
      (node (ref "MICROCONTROLLER2") (pin "49") (pinfunction "49_49") (pintype "input"))
      (node (ref "MICROCONTROLLER3") (pin "32") (pinfunction "32_32") (pintype "bidirectional"))
      (node (ref "MICROCONTROLLER3") (pin "49") (pinfunction "49_49") (pintype "input"))
      (node (ref "MICROCONTROLLER5") (pin "32") (pinfunction "32_32") (pintype "bidirectional"))
      (node (ref "MICROCONTROLLER5") (pin "49") (pinfunction "49_49") (pintype "input"))
      (node (ref "R117") (pin "2") (pinfunction "2_2") (pintype "passive"))
      (node (ref "R118") (pin "2") (pinfunction "2_2") (pintype "passive"))
      (node (ref "R129") (pin "2") (pinfunction "2_2") (pintype "passive"))
      (node (ref "R29") (pin "2") (pinfunction "2_2") (pintype "passive"))
      (node (ref "R30") (pin "2") (pinfunction "2_2") (pintype "passive"))
      (node (ref "R41") (pin "2") (pinfunction "2_2") (pintype "passive"))
      (node (ref "R51") (pin "2") (pinfunction "2_2") (pintype "passive"))
      (node (ref "R52") (pin "2") (pinfunction "2_2") (pintype "passive"))
      (node (ref "R63") (pin "2") (pinfunction "2_2") (pintype "passive"))
      (node (ref "R73") (pin "2") (pinfunction "2_2") (pintype "passive"))
      (node (ref "R74") (pin "2") (pinfunction "2_2") (pintype "passive"))
      (node (ref "R85") (pin "2") (pinfunction "2_2") (pintype "passive"))
      (node (ref "REAR_PANEL1") (pin "-") (pinfunction "-_-") (pintype "passive"))
      (node (ref "REAR_PANEL2") (pin "-") (pinfunction "-_-") (pintype "passive"))
      (node (ref "REAR_PANEL3") (pin "-") (pinfunction "-_-") (pintype "passive"))
      (node (ref "REAR_PANEL5") (pin "-") (pinfunction "-_-") (pintype "passive"))
      (node (ref "TSX1") (pin "2") (pinfunction "2_2") (pintype "bidirectional"))
      (node (ref "TSX1") (pin "4") (pinfunction "4_4") (pintype "bidirectional"))
      (node (ref "TSX2") (pin "2") (pinfunction "2_2") (pintype "bidirectional"))
      (node (ref "TSX2") (pin "4") (pinfunction "4_4") (pintype "bidirectional"))
      (node (ref "TSX3") (pin "2") (pinfunction "2_2") (pintype "bidirectional"))
      (node (ref "TSX3") (pin "4") (pinfunction "4_4") (pintype "bidirectional"))
      (node (ref "TSX5") (pin "2") (pinfunction "2_2") (pintype "bidirectional"))
      (node (ref "TSX5") (pin "4") (pinfunction "4_4") (pintype "bidirectional"))
      (node (ref "U$1") (pin "PGND") (pinfunction "PGND_PGND") (pintype "bidirectional"))
      (node (ref "U$1") (pin "SGND") (pinfunction "SGND_SGND") (pintype "bidirectional"))
      (node (ref "U$11") (pin "GND") (pinfunction "GND_GND") (pintype "bidirectional"))
      (node (ref "U$13") (pin "GND1") (pinfunction "GND1_GND1") (pintype "bidirectional"))
      (node (ref "U$13") (pin "GND2") (pinfunction "GND2_GND2") (pintype "bidirectional"))
      (node (ref "U$13") (pin "GND3") (pinfunction "GND3_GND3") (pintype "bidirectional"))
      (node (ref "U$14") (pin "GND1") (pinfunction "GND1_GND1") (pintype "bidirectional"))
      (node (ref "U$14") (pin "GND2") (pinfunction "GND2_GND2") (pintype "bidirectional"))
      (node (ref "U$14") (pin "GND3") (pinfunction "GND3_GND3") (pintype "bidirectional"))
      (node (ref "U$15") (pin "6") (pinfunction "GND_6") (pintype "bidirectional"))
      (node (ref "U$16") (pin "1") (pinfunction "1_1") (pintype "bidirectional"))
      (node (ref "U$16") (pin "FOOT1") (pinfunction "FOOT1_FOOT1") (pintype "bidirectional"))
      (node (ref "U$16") (pin "FOOT2") (pinfunction "FOOT2_FOOT2") (pintype "bidirectional"))
      (node (ref "U$16") (pin "FOOT3") (pinfunction "FOOT3_FOOT3") (pintype "bidirectional"))
      (node (ref "U$16") (pin "FOOT4") (pinfunction "FOOT4_FOOT4") (pintype "bidirectional"))
      (node (ref "U$17") (pin "PGND") (pinfunction "PGND_PGND") (pintype "bidirectional"))
      (node (ref "U$17") (pin "SGND") (pinfunction "SGND_SGND") (pintype "bidirectional"))
      (node (ref "U$19") (pin "GND") (pinfunction "GND_GND") (pintype "bidirectional"))
      (node (ref "U$21") (pin "GND1") (pinfunction "GND1_GND1") (pintype "bidirectional"))
      (node (ref "U$21") (pin "GND2") (pinfunction "GND2_GND2") (pintype "bidirectional"))
      (node (ref "U$21") (pin "GND3") (pinfunction "GND3_GND3") (pintype "bidirectional"))
      (node (ref "U$22") (pin "GND1") (pinfunction "GND1_GND1") (pintype "bidirectional"))
      (node (ref "U$22") (pin "GND2") (pinfunction "GND2_GND2") (pintype "bidirectional"))
      (node (ref "U$22") (pin "GND3") (pinfunction "GND3_GND3") (pintype "bidirectional"))
      (node (ref "U$23") (pin "6") (pinfunction "GND_6") (pintype "bidirectional"))
      (node (ref "U$24") (pin "1") (pinfunction "1_1") (pintype "bidirectional"))
      (node (ref "U$24") (pin "FOOT1") (pinfunction "FOOT1_FOOT1") (pintype "bidirectional"))
      (node (ref "U$24") (pin "FOOT2") (pinfunction "FOOT2_FOOT2") (pintype "bidirectional"))
      (node (ref "U$24") (pin "FOOT3") (pinfunction "FOOT3_FOOT3") (pintype "bidirectional"))
      (node (ref "U$24") (pin "FOOT4") (pinfunction "FOOT4_FOOT4") (pintype "bidirectional"))
      (node (ref "U$25") (pin "PGND") (pinfunction "PGND_PGND") (pintype "bidirectional"))
      (node (ref "U$25") (pin "SGND") (pinfunction "SGND_SGND") (pintype "bidirectional"))
      (node (ref "U$27") (pin "GND") (pinfunction "GND_GND") (pintype "bidirectional"))
      (node (ref "U$29") (pin "GND1") (pinfunction "GND1_GND1") (pintype "bidirectional"))
      (node (ref "U$29") (pin "GND2") (pinfunction "GND2_GND2") (pintype "bidirectional"))
      (node (ref "U$29") (pin "GND3") (pinfunction "GND3_GND3") (pintype "bidirectional"))
      (node (ref "U$30") (pin "GND1") (pinfunction "GND1_GND1") (pintype "bidirectional"))
      (node (ref "U$30") (pin "GND2") (pinfunction "GND2_GND2") (pintype "bidirectional"))
      (node (ref "U$30") (pin "GND3") (pinfunction "GND3_GND3") (pintype "bidirectional"))
      (node (ref "U$31") (pin "6") (pinfunction "GND_6") (pintype "bidirectional"))
      (node (ref "U$32") (pin "1") (pinfunction "1_1") (pintype "bidirectional"))
      (node (ref "U$32") (pin "FOOT1") (pinfunction "FOOT1_FOOT1") (pintype "bidirectional"))
      (node (ref "U$32") (pin "FOOT2") (pinfunction "FOOT2_FOOT2") (pintype "bidirectional"))
      (node (ref "U$32") (pin "FOOT3") (pinfunction "FOOT3_FOOT3") (pintype "bidirectional"))
      (node (ref "U$32") (pin "FOOT4") (pinfunction "FOOT4_FOOT4") (pintype "bidirectional"))
      (node (ref "U$41") (pin "PGND") (pinfunction "PGND_PGND") (pintype "bidirectional"))
      (node (ref "U$41") (pin "SGND") (pinfunction "SGND_SGND") (pintype "bidirectional"))
      (node (ref "U$43") (pin "GND") (pinfunction "GND_GND") (pintype "bidirectional"))
      (node (ref "U$45") (pin "GND1") (pinfunction "GND1_GND1") (pintype "bidirectional"))
      (node (ref "U$45") (pin "GND2") (pinfunction "GND2_GND2") (pintype "bidirectional"))
      (node (ref "U$45") (pin "GND3") (pinfunction "GND3_GND3") (pintype "bidirectional"))
      (node (ref "U$46") (pin "GND1") (pinfunction "GND1_GND1") (pintype "bidirectional"))
      (node (ref "U$46") (pin "GND2") (pinfunction "GND2_GND2") (pintype "bidirectional"))
      (node (ref "U$46") (pin "GND3") (pinfunction "GND3_GND3") (pintype "bidirectional"))
      (node (ref "U$47") (pin "6") (pinfunction "GND_6") (pintype "bidirectional"))
      (node (ref "U$48") (pin "1") (pinfunction "1_1") (pintype "bidirectional"))
      (node (ref "U$48") (pin "FOOT1") (pinfunction "FOOT1_FOOT1") (pintype "bidirectional"))
      (node (ref "U$48") (pin "FOOT2") (pinfunction "FOOT2_FOOT2") (pintype "bidirectional"))
      (node (ref "U$48") (pin "FOOT3") (pinfunction "FOOT3_FOOT3") (pintype "bidirectional"))
      (node (ref "U$48") (pin "FOOT4") (pinfunction "FOOT4_FOOT4") (pintype "bidirectional"))
    )
    (net (code "29") (name "Net-(32.1-PadP1)") (class "Default")
      (node (ref "32.1") (pin "P1") (pinfunction "P1_P1") (pintype "bidirectional"))
      (node (ref "C35") (pin "1") (pinfunction "1_1") (pintype "passive"))
      (node (ref "MICROCONTROLLER1") (pin "5") (pinfunction "5_5") (pintype "bidirectional"))
    )
    (net (code "30") (name "Net-(32.1-PadP2)") (class "Default")
      (node (ref "32.1") (pin "P2") (pinfunction "P2_P2") (pintype "bidirectional"))
      (node (ref "C34") (pin "1") (pinfunction "1_1") (pintype "passive"))
      (node (ref "MICROCONTROLLER1") (pin "4") (pinfunction "4_4") (pintype "bidirectional"))
    )
    (net (code "31") (name "Net-(32.2-PadP1)") (class "Default")
      (node (ref "32.2") (pin "P1") (pinfunction "P1_P1") (pintype "bidirectional"))
      (node (ref "C58") (pin "1") (pinfunction "1_1") (pintype "passive"))
      (node (ref "MICROCONTROLLER2") (pin "5") (pinfunction "5_5") (pintype "bidirectional"))
    )
    (net (code "32") (name "Net-(32.2-PadP2)") (class "Default")
      (node (ref "32.2") (pin "P2") (pinfunction "P2_P2") (pintype "bidirectional"))
      (node (ref "C57") (pin "1") (pinfunction "1_1") (pintype "passive"))
      (node (ref "MICROCONTROLLER2") (pin "4") (pinfunction "4_4") (pintype "bidirectional"))
    )
    (net (code "33") (name "Net-(32.3-PadP1)") (class "Default")
      (node (ref "32.3") (pin "P1") (pinfunction "P1_P1") (pintype "bidirectional"))
      (node (ref "C81") (pin "1") (pinfunction "1_1") (pintype "passive"))
      (node (ref "MICROCONTROLLER3") (pin "5") (pinfunction "5_5") (pintype "bidirectional"))
    )
    (net (code "34") (name "Net-(32.3-PadP2)") (class "Default")
      (node (ref "32.3") (pin "P2") (pinfunction "P2_P2") (pintype "bidirectional"))
      (node (ref "C80") (pin "1") (pinfunction "1_1") (pintype "passive"))
      (node (ref "MICROCONTROLLER3") (pin "4") (pinfunction "4_4") (pintype "bidirectional"))
    )
    (net (code "35") (name "Net-(32.5-PadP1)") (class "Default")
      (node (ref "32.5") (pin "P1") (pinfunction "P1_P1") (pintype "bidirectional"))
      (node (ref "C127") (pin "1") (pinfunction "1_1") (pintype "passive"))
      (node (ref "MICROCONTROLLER5") (pin "5") (pinfunction "5_5") (pintype "bidirectional"))
    )
    (net (code "36") (name "Net-(32.5-PadP2)") (class "Default")
      (node (ref "32.5") (pin "P2") (pinfunction "P2_P2") (pintype "bidirectional"))
      (node (ref "C126") (pin "1") (pinfunction "1_1") (pintype "passive"))
      (node (ref "MICROCONTROLLER5") (pin "4") (pinfunction "4_4") (pintype "bidirectional"))
    )
    (net (code "37") (name "Net-(BALUN1-RF_N)") (class "Default")
      (node (ref "BALUN1") (pin "3") (pinfunction "RF_N_3") (pintype "bidirectional"))
      (node (ref "MICROCONTROLLER1") (pin "2") (pinfunction "2_2") (pintype "bidirectional"))
    )
    (net (code "38") (name "Net-(BALUN1-RF_P)") (class "Default")
      (node (ref "BALUN1") (pin "4") (pinfunction "RF_P_4") (pintype "bidirectional"))
      (node (ref "MICROCONTROLLER1") (pin "1") (pinfunction "1_1") (pintype "bidirectional"))
    )
    (net (code "39") (name "Net-(BALUN1-RX{slash}TX)") (class "Default")
      (node (ref "BALUN1") (pin "2") (pinfunction "RX/TX_2") (pintype "bidirectional"))
      (node (ref "MICROCONTROLLER1") (pin "3") (pinfunction "3_3") (pintype "bidirectional"))
    )
    (net (code "40") (name "Net-(BALUN1-UNBAL)") (class "Default")
      (node (ref "BALUN1") (pin "1") (pinfunction "UNBAL_1") (pintype "bidirectional"))
      (node (ref "C42") (pin "2") (pinfunction "2_2") (pintype "passive"))
    )
    (net (code "41") (name "Net-(BALUN2-RF_N)") (class "Default")
      (node (ref "BALUN2") (pin "3") (pinfunction "RF_N_3") (pintype "bidirectional"))
      (node (ref "MICROCONTROLLER2") (pin "2") (pinfunction "2_2") (pintype "bidirectional"))
    )
    (net (code "42") (name "Net-(BALUN2-RF_P)") (class "Default")
      (node (ref "BALUN2") (pin "4") (pinfunction "RF_P_4") (pintype "bidirectional"))
      (node (ref "MICROCONTROLLER2") (pin "1") (pinfunction "1_1") (pintype "bidirectional"))
    )
    (net (code "43") (name "Net-(BALUN2-RX{slash}TX)") (class "Default")
      (node (ref "BALUN2") (pin "2") (pinfunction "RX/TX_2") (pintype "bidirectional"))
      (node (ref "MICROCONTROLLER2") (pin "3") (pinfunction "3_3") (pintype "bidirectional"))
    )
    (net (code "44") (name "Net-(BALUN2-UNBAL)") (class "Default")
      (node (ref "BALUN2") (pin "1") (pinfunction "UNBAL_1") (pintype "bidirectional"))
      (node (ref "C65") (pin "2") (pinfunction "2_2") (pintype "passive"))
    )
    (net (code "45") (name "Net-(BALUN3-RF_N)") (class "Default")
      (node (ref "BALUN3") (pin "3") (pinfunction "RF_N_3") (pintype "bidirectional"))
      (node (ref "MICROCONTROLLER3") (pin "2") (pinfunction "2_2") (pintype "bidirectional"))
    )
    (net (code "46") (name "Net-(BALUN3-RF_P)") (class "Default")
      (node (ref "BALUN3") (pin "4") (pinfunction "RF_P_4") (pintype "bidirectional"))
      (node (ref "MICROCONTROLLER3") (pin "1") (pinfunction "1_1") (pintype "bidirectional"))
    )
    (net (code "47") (name "Net-(BALUN3-RX{slash}TX)") (class "Default")
      (node (ref "BALUN3") (pin "2") (pinfunction "RX/TX_2") (pintype "bidirectional"))
      (node (ref "MICROCONTROLLER3") (pin "3") (pinfunction "3_3") (pintype "bidirectional"))
    )
    (net (code "48") (name "Net-(BALUN3-UNBAL)") (class "Default")
      (node (ref "BALUN3") (pin "1") (pinfunction "UNBAL_1") (pintype "bidirectional"))
      (node (ref "C88") (pin "2") (pinfunction "2_2") (pintype "passive"))
    )
    (net (code "49") (name "Net-(BALUN5-RF_N)") (class "Default")
      (node (ref "BALUN5") (pin "3") (pinfunction "RF_N_3") (pintype "bidirectional"))
      (node (ref "MICROCONTROLLER5") (pin "2") (pinfunction "2_2") (pintype "bidirectional"))
    )
    (net (code "50") (name "Net-(BALUN5-RF_P)") (class "Default")
      (node (ref "BALUN5") (pin "4") (pinfunction "RF_P_4") (pintype "bidirectional"))
      (node (ref "MICROCONTROLLER5") (pin "1") (pinfunction "1_1") (pintype "bidirectional"))
    )
    (net (code "51") (name "Net-(BALUN5-RX{slash}TX)") (class "Default")
      (node (ref "BALUN5") (pin "2") (pinfunction "RX/TX_2") (pintype "bidirectional"))
      (node (ref "MICROCONTROLLER5") (pin "3") (pinfunction "3_3") (pintype "bidirectional"))
    )
    (net (code "52") (name "Net-(BALUN5-UNBAL)") (class "Default")
      (node (ref "BALUN5") (pin "1") (pinfunction "UNBAL_1") (pintype "bidirectional"))
      (node (ref "C134") (pin "2") (pinfunction "2_2") (pintype "passive"))
    )
    (net (code "53") (name "Net-(C33-Pad1)") (class "Default")
      (node (ref "C33") (pin "1") (pinfunction "1_1") (pintype "passive"))
      (node (ref "MICROCONTROLLER1") (pin "23") (pinfunction "23_23") (pintype "bidirectional"))
    )
    (net (code "54") (name "Net-(C42-Pad1)") (class "Default")
      (node (ref "C42") (pin "1") (pinfunction "1_1") (pintype "passive"))
      (node (ref "R37") (pin "1") (pinfunction "1_1") (pintype "passive"))
    )
    (net (code "55") (name "Net-(C56-Pad1)") (class "Default")
      (node (ref "C56") (pin "1") (pinfunction "1_1") (pintype "passive"))
      (node (ref "MICROCONTROLLER2") (pin "23") (pinfunction "23_23") (pintype "bidirectional"))
    )
    (net (code "56") (name "Net-(C65-Pad1)") (class "Default")
      (node (ref "C65") (pin "1") (pinfunction "1_1") (pintype "passive"))
      (node (ref "R59") (pin "1") (pinfunction "1_1") (pintype "passive"))
    )
    (net (code "57") (name "Net-(C79-Pad1)") (class "Default")
      (node (ref "C79") (pin "1") (pinfunction "1_1") (pintype "passive"))
      (node (ref "MICROCONTROLLER3") (pin "23") (pinfunction "23_23") (pintype "bidirectional"))
    )
    (net (code "58") (name "Net-(C88-Pad1)") (class "Default")
      (node (ref "C88") (pin "1") (pinfunction "1_1") (pintype "passive"))
      (node (ref "R81") (pin "1") (pinfunction "1_1") (pintype "passive"))
    )
    (net (code "59") (name "Net-(C125-Pad1)") (class "Default")
      (node (ref "C125") (pin "1") (pinfunction "1_1") (pintype "passive"))
      (node (ref "MICROCONTROLLER5") (pin "23") (pinfunction "23_23") (pintype "bidirectional"))
    )
    (net (code "60") (name "Net-(C134-Pad1)") (class "Default")
      (node (ref "C134") (pin "1") (pinfunction "1_1") (pintype "passive"))
      (node (ref "R125") (pin "1") (pinfunction "1_1") (pintype "passive"))
    )
    (net (code "61") (name "Net-(GPS1-BOOT_SEL)") (class "Default")
      (node (ref "GPS1") (pin "9") (pinfunction "BOOT_SEL_9") (pintype "bidirectional"))
      (node (ref "R33") (pin "1") (pinfunction "1_1") (pintype "passive"))
    )
    (net (code "62") (name "Net-(GPS1-RFIN)") (class "Default")
      (node (ref "GPS1") (pin "32") (pinfunction "RFIN_32") (pintype "bidirectional"))
      (node (ref "R38") (pin "2") (pinfunction "2_2") (pintype "passive"))
    )
    (net (code "63") (name "Net-(GPS1-RSTN)") (class "Default")
      (node (ref "C41") (pin "1") (pinfunction "1_1") (pintype "passive"))
      (node (ref "GPS1") (pin "1") (pinfunction "RSTN_1") (pintype "bidirectional"))
      (node (ref "R34") (pin "2") (pinfunction "2_2") (pintype "passive"))
    )
    (net (code "64") (name "Net-(GPS1-RXD0)") (class "Default")
      (node (ref "GPS1") (pin "42") (pinfunction "RXD0_42") (pintype "bidirectional"))
      (node (ref "R31") (pin "1") (pinfunction "1_1") (pintype "passive"))
    )
    (net (code "65") (name "Net-(GPS2-BOOT_SEL)") (class "Default")
      (node (ref "GPS2") (pin "9") (pinfunction "BOOT_SEL_9") (pintype "bidirectional"))
      (node (ref "R55") (pin "1") (pinfunction "1_1") (pintype "passive"))
    )
    (net (code "66") (name "Net-(GPS2-RFIN)") (class "Default")
      (node (ref "GPS2") (pin "32") (pinfunction "RFIN_32") (pintype "bidirectional"))
      (node (ref "R60") (pin "2") (pinfunction "2_2") (pintype "passive"))
    )
    (net (code "67") (name "Net-(GPS2-RSTN)") (class "Default")
      (node (ref "C64") (pin "1") (pinfunction "1_1") (pintype "passive"))
      (node (ref "GPS2") (pin "1") (pinfunction "RSTN_1") (pintype "bidirectional"))
      (node (ref "R56") (pin "2") (pinfunction "2_2") (pintype "passive"))
    )
    (net (code "68") (name "Net-(GPS2-RXD0)") (class "Default")
      (node (ref "GPS2") (pin "42") (pinfunction "RXD0_42") (pintype "bidirectional"))
      (node (ref "R53") (pin "1") (pinfunction "1_1") (pintype "passive"))
    )
    (net (code "69") (name "Net-(GPS3-BOOT_SEL)") (class "Default")
      (node (ref "GPS3") (pin "9") (pinfunction "BOOT_SEL_9") (pintype "bidirectional"))
      (node (ref "R77") (pin "1") (pinfunction "1_1") (pintype "passive"))
    )
    (net (code "70") (name "Net-(GPS3-RFIN)") (class "Default")
      (node (ref "GPS3") (pin "32") (pinfunction "RFIN_32") (pintype "bidirectional"))
      (node (ref "R82") (pin "2") (pinfunction "2_2") (pintype "passive"))
    )
    (net (code "71") (name "Net-(GPS3-RSTN)") (class "Default")
      (node (ref "C87") (pin "1") (pinfunction "1_1") (pintype "passive"))
      (node (ref "GPS3") (pin "1") (pinfunction "RSTN_1") (pintype "bidirectional"))
      (node (ref "R78") (pin "2") (pinfunction "2_2") (pintype "passive"))
    )
    (net (code "72") (name "Net-(GPS3-RXD0)") (class "Default")
      (node (ref "GPS3") (pin "42") (pinfunction "RXD0_42") (pintype "bidirectional"))
      (node (ref "R75") (pin "1") (pinfunction "1_1") (pintype "passive"))
    )
    (net (code "73") (name "Net-(GPS5-BOOT_SEL)") (class "Default")
      (node (ref "GPS5") (pin "9") (pinfunction "BOOT_SEL_9") (pintype "bidirectional"))
      (node (ref "R121") (pin "1") (pinfunction "1_1") (pintype "passive"))
    )
    (net (code "74") (name "Net-(GPS5-RFIN)") (class "Default")
      (node (ref "GPS5") (pin "32") (pinfunction "RFIN_32") (pintype "bidirectional"))
      (node (ref "R126") (pin "2") (pinfunction "2_2") (pintype "passive"))
    )
    (net (code "75") (name "Net-(GPS5-RSTN)") (class "Default")
      (node (ref "C133") (pin "1") (pinfunction "1_1") (pintype "passive"))
      (node (ref "GPS5") (pin "1") (pinfunction "RSTN_1") (pintype "bidirectional"))
      (node (ref "R122") (pin "2") (pinfunction "2_2") (pintype "passive"))
    )
    (net (code "76") (name "Net-(GPS5-RXD0)") (class "Default")
      (node (ref "GPS5") (pin "42") (pinfunction "RXD0_42") (pintype "bidirectional"))
      (node (ref "R119") (pin "1") (pinfunction "1_1") (pintype "passive"))
    )
    (net (code "77") (name "Net-(IMU1-C1)") (class "Default")
      (node (ref "C40") (pin "1") (pinfunction "1_1") (pintype "passive"))
      (node (ref "IMU1") (pin "24") (pinfunction "C1_24") (pintype "bidirectional"))
    )
    (net (code "78") (name "Net-(IMU1-CAP)") (class "Default")
      (node (ref "C39") (pin "1") (pinfunction "1_1") (pintype "passive"))
      (node (ref "IMU1") (pin "21") (pinfunction "CAP_21") (pintype "bidirectional"))
    )
    (net (code "79") (name "Net-(IMU1-CS_A{slash}G)") (class "Default")
      (node (ref "IMU1") (pin "5") (pinfunction "SDO_A/G_5") (pintype "bidirectional"))
      (node (ref "IMU1") (pin "6") (pinfunction "SDO_M_6") (pintype "bidirectional"))
      (node (ref "IMU1") (pin "7") (pinfunction "CS_A/G_7") (pintype "bidirectional"))
      (node (ref "IMU1") (pin "8") (pinfunction "CS_M_8") (pintype "bidirectional"))
      (node (ref "R28") (pin "2") (pinfunction "2_2") (pintype "passive"))
    )
    (net (code "80") (name "Net-(IMU2-C1)") (class "Default")
      (node (ref "C63") (pin "1") (pinfunction "1_1") (pintype "passive"))
      (node (ref "IMU2") (pin "24") (pinfunction "C1_24") (pintype "bidirectional"))
    )
    (net (code "81") (name "Net-(IMU2-CAP)") (class "Default")
      (node (ref "C62") (pin "1") (pinfunction "1_1") (pintype "passive"))
      (node (ref "IMU2") (pin "21") (pinfunction "CAP_21") (pintype "bidirectional"))
    )
    (net (code "82") (name "Net-(IMU2-CS_A{slash}G)") (class "Default")
      (node (ref "IMU2") (pin "5") (pinfunction "SDO_A/G_5") (pintype "bidirectional"))
      (node (ref "IMU2") (pin "6") (pinfunction "SDO_M_6") (pintype "bidirectional"))
      (node (ref "IMU2") (pin "7") (pinfunction "CS_A/G_7") (pintype "bidirectional"))
      (node (ref "IMU2") (pin "8") (pinfunction "CS_M_8") (pintype "bidirectional"))
      (node (ref "R50") (pin "2") (pinfunction "2_2") (pintype "passive"))
    )
    (net (code "83") (name "Net-(IMU3-C1)") (class "Default")
      (node (ref "C86") (pin "1") (pinfunction "1_1") (pintype "passive"))
      (node (ref "IMU3") (pin "24") (pinfunction "C1_24") (pintype "bidirectional"))
    )
    (net (code "84") (name "Net-(IMU3-CAP)") (class "Default")
      (node (ref "C85") (pin "1") (pinfunction "1_1") (pintype "passive"))
      (node (ref "IMU3") (pin "21") (pinfunction "CAP_21") (pintype "bidirectional"))
    )
    (net (code "85") (name "Net-(IMU3-CS_A{slash}G)") (class "Default")
      (node (ref "IMU3") (pin "5") (pinfunction "SDO_A/G_5") (pintype "bidirectional"))
      (node (ref "IMU3") (pin "6") (pinfunction "SDO_M_6") (pintype "bidirectional"))
      (node (ref "IMU3") (pin "7") (pinfunction "CS_A/G_7") (pintype "bidirectional"))
      (node (ref "IMU3") (pin "8") (pinfunction "CS_M_8") (pintype "bidirectional"))
      (node (ref "R72") (pin "2") (pinfunction "2_2") (pintype "passive"))
    )
    (net (code "86") (name "Net-(IMU5-C1)") (class "Default")
      (node (ref "C132") (pin "1") (pinfunction "1_1") (pintype "passive"))
      (node (ref "IMU5") (pin "24") (pinfunction "C1_24") (pintype "bidirectional"))
    )
    (net (code "87") (name "Net-(IMU5-CAP)") (class "Default")
      (node (ref "C131") (pin "1") (pinfunction "1_1") (pintype "passive"))
      (node (ref "IMU5") (pin "21") (pinfunction "CAP_21") (pintype "bidirectional"))
    )
    (net (code "88") (name "Net-(IMU5-CS_A{slash}G)") (class "Default")
      (node (ref "IMU5") (pin "5") (pinfunction "SDO_A/G_5") (pintype "bidirectional"))
      (node (ref "IMU5") (pin "6") (pinfunction "SDO_M_6") (pintype "bidirectional"))
      (node (ref "IMU5") (pin "7") (pinfunction "CS_A/G_7") (pintype "bidirectional"))
      (node (ref "IMU5") (pin "8") (pinfunction "CS_M_8") (pintype "bidirectional"))
      (node (ref "R116") (pin "2") (pinfunction "2_2") (pintype "passive"))
    )
    (net (code "89") (name "Net-(L6-Pad1)") (class "Default")
      (node (ref "L6") (pin "1") (pinfunction "1_1") (pintype "passive"))
      (node (ref "R37") (pin "2") (pinfunction "2_2") (pintype "passive"))
      (node (ref "R39") (pin "1") (pinfunction "1_1") (pintype "passive"))
      (node (ref "R43") (pin "2") (pinfunction "2_2") (pintype "passive"))
    )
    (net (code "90") (name "Net-(L7-Pad2)") (class "Default")
      (node (ref "L7") (pin "2") (pinfunction "2_2") (pintype "passive"))
      (node (ref "R40") (pin "1") (pinfunction "1_1") (pintype "passive"))
      (node (ref "U$10") (pin "SIG") (pinfunction "SIG_SIG") (pintype "bidirectional"))
    )
    (net (code "91") (name "Net-(L10-Pad1)") (class "Default")
      (node (ref "L10") (pin "1") (pinfunction "1_1") (pintype "passive"))
      (node (ref "R59") (pin "2") (pinfunction "2_2") (pintype "passive"))
      (node (ref "R61") (pin "1") (pinfunction "1_1") (pintype "passive"))
      (node (ref "R65") (pin "2") (pinfunction "2_2") (pintype "passive"))
    )
    (net (code "92") (name "Net-(L11-Pad2)") (class "Default")
      (node (ref "L11") (pin "2") (pinfunction "2_2") (pintype "passive"))
      (node (ref "R62") (pin "1") (pinfunction "1_1") (pintype "passive"))
      (node (ref "U$18") (pin "SIG") (pinfunction "SIG_SIG") (pintype "bidirectional"))
    )
    (net (code "93") (name "Net-(L14-Pad1)") (class "Default")
      (node (ref "L14") (pin "1") (pinfunction "1_1") (pintype "passive"))
      (node (ref "R81") (pin "2") (pinfunction "2_2") (pintype "passive"))
      (node (ref "R83") (pin "1") (pinfunction "1_1") (pintype "passive"))
      (node (ref "R87") (pin "2") (pinfunction "2_2") (pintype "passive"))
    )
    (net (code "94") (name "Net-(L15-Pad2)") (class "Default")
      (node (ref "L15") (pin "2") (pinfunction "2_2") (pintype "passive"))
      (node (ref "R84") (pin "1") (pinfunction "1_1") (pintype "passive"))
      (node (ref "U$26") (pin "SIG") (pinfunction "SIG_SIG") (pintype "bidirectional"))
    )
    (net (code "95") (name "Net-(L22-Pad1)") (class "Default")
      (node (ref "L22") (pin "1") (pinfunction "1_1") (pintype "passive"))
      (node (ref "R125") (pin "2") (pinfunction "2_2") (pintype "passive"))
      (node (ref "R127") (pin "1") (pinfunction "1_1") (pintype "passive"))
      (node (ref "R131") (pin "2") (pinfunction "2_2") (pintype "passive"))
    )
    (net (code "96") (name "Net-(L23-Pad2)") (class "Default")
      (node (ref "L23") (pin "2") (pinfunction "2_2") (pintype "passive"))
      (node (ref "R128") (pin "1") (pinfunction "1_1") (pintype "passive"))
      (node (ref "U$42") (pin "SIG") (pinfunction "SIG_SIG") (pintype "bidirectional"))
    )
    (net (code "97") (name "Net-(LED4-PadA)") (class "Default")
      (node (ref "LED4") (pin "A") (pinfunction "A_A") (pintype "passive"))
      (node (ref "R26") (pin "1") (pinfunction "1_1") (pintype "passive"))
    )
    (net (code "98") (name "Net-(LED5-PadA)") (class "Default")
      (node (ref "LED5") (pin "A") (pinfunction "A_A") (pintype "passive"))
      (node (ref "R27") (pin "1") (pinfunction "1_1") (pintype "passive"))
    )
    (net (code "99") (name "Net-(LED6-PadC)") (class "Default")
      (node (ref "LED6") (pin "C") (pinfunction "C_C") (pintype "passive"))
      (node (ref "R32") (pin "2") (pinfunction "2_2") (pintype "passive"))
    )
    (net (code "100") (name "Net-(LED7-PadA)") (class "Default")
      (node (ref "LED7") (pin "A") (pinfunction "A_A") (pintype "passive"))
      (node (ref "R48") (pin "1") (pinfunction "1_1") (pintype "passive"))
    )
    (net (code "101") (name "Net-(LED8-PadA)") (class "Default")
      (node (ref "LED8") (pin "A") (pinfunction "A_A") (pintype "passive"))
      (node (ref "R49") (pin "1") (pinfunction "1_1") (pintype "passive"))
    )
    (net (code "102") (name "Net-(LED9-PadC)") (class "Default")
      (node (ref "LED9") (pin "C") (pinfunction "C_C") (pintype "passive"))
      (node (ref "R54") (pin "2") (pinfunction "2_2") (pintype "passive"))
    )
    (net (code "103") (name "Net-(LED10-PadA)") (class "Default")
      (node (ref "LED10") (pin "A") (pinfunction "A_A") (pintype "passive"))
      (node (ref "R70") (pin "1") (pinfunction "1_1") (pintype "passive"))
    )
    (net (code "104") (name "Net-(LED11-PadA)") (class "Default")
      (node (ref "LED11") (pin "A") (pinfunction "A_A") (pintype "passive"))
      (node (ref "R71") (pin "1") (pinfunction "1_1") (pintype "passive"))
    )
    (net (code "105") (name "Net-(LED12-PadC)") (class "Default")
      (node (ref "LED12") (pin "C") (pinfunction "C_C") (pintype "passive"))
      (node (ref "R76") (pin "2") (pinfunction "2_2") (pintype "passive"))
    )
    (net (code "106") (name "Net-(LED16-PadA)") (class "Default")
      (node (ref "LED16") (pin "A") (pinfunction "A_A") (pintype "passive"))
      (node (ref "R114") (pin "1") (pinfunction "1_1") (pintype "passive"))
    )
    (net (code "107") (name "Net-(LED17-PadA)") (class "Default")
      (node (ref "LED17") (pin "A") (pinfunction "A_A") (pintype "passive"))
      (node (ref "R115") (pin "1") (pinfunction "1_1") (pintype "passive"))
    )
    (net (code "108") (name "Net-(LED18-PadC)") (class "Default")
      (node (ref "LED18") (pin "C") (pinfunction "C_C") (pintype "passive"))
      (node (ref "R120") (pin "2") (pinfunction "2_2") (pintype "passive"))
    )
    (net (code "109") (name "Net-(R35-Pad1)") (class "Default")
      (node (ref "R35") (pin "1") (pinfunction "1_1") (pintype "passive"))
      (node (ref "U$1") (pin "ENA") (pinfunction "ENA_ENA") (pintype "bidirectional"))
    )
    (net (code "110") (name "Net-(R36-Pad1)") (class "Default")
      (node (ref "R36") (pin "1") (pinfunction "1_1") (pintype "passive"))
      (node (ref "U$1") (pin "OUT1") (pinfunction "OUT1_OUT1") (pintype "bidirectional"))
    )
    (net (code "111") (name "Net-(R38-Pad1)") (class "Default")
      (node (ref "R38") (pin "1") (pinfunction "1_1") (pintype "passive"))
      (node (ref "R40") (pin "2") (pinfunction "2_2") (pintype "passive"))
      (node (ref "R41") (pin "1") (pinfunction "1_1") (pintype "passive"))
      (node (ref "R44") (pin "1") (pinfunction "1_1") (pintype "passive"))
    )
    (net (code "112") (name "Net-(R43-Pad1)") (class "Default")
      (node (ref "R43") (pin "1") (pinfunction "1_1") (pintype "passive"))
      (node (ref "U$13") (pin "SIG") (pinfunction "SIG_SIG") (pintype "bidirectional"))
    )
    (net (code "113") (name "Net-(R44-Pad2)") (class "Default")
      (node (ref "R44") (pin "2") (pinfunction "2_2") (pintype "passive"))
      (node (ref "U$14") (pin "SIG") (pinfunction "SIG_SIG") (pintype "bidirectional"))
    )
    (net (code "114") (name "Net-(R57-Pad1)") (class "Default")
      (node (ref "R57") (pin "1") (pinfunction "1_1") (pintype "passive"))
      (node (ref "U$17") (pin "ENA") (pinfunction "ENA_ENA") (pintype "bidirectional"))
    )
    (net (code "115") (name "Net-(R58-Pad1)") (class "Default")
      (node (ref "R58") (pin "1") (pinfunction "1_1") (pintype "passive"))
      (node (ref "U$17") (pin "OUT1") (pinfunction "OUT1_OUT1") (pintype "bidirectional"))
    )
    (net (code "116") (name "Net-(R60-Pad1)") (class "Default")
      (node (ref "R60") (pin "1") (pinfunction "1_1") (pintype "passive"))
      (node (ref "R62") (pin "2") (pinfunction "2_2") (pintype "passive"))
      (node (ref "R63") (pin "1") (pinfunction "1_1") (pintype "passive"))
      (node (ref "R66") (pin "1") (pinfunction "1_1") (pintype "passive"))
    )
    (net (code "117") (name "Net-(R65-Pad1)") (class "Default")
      (node (ref "R65") (pin "1") (pinfunction "1_1") (pintype "passive"))
      (node (ref "U$21") (pin "SIG") (pinfunction "SIG_SIG") (pintype "bidirectional"))
    )
    (net (code "118") (name "Net-(R66-Pad2)") (class "Default")
      (node (ref "R66") (pin "2") (pinfunction "2_2") (pintype "passive"))
      (node (ref "U$22") (pin "SIG") (pinfunction "SIG_SIG") (pintype "bidirectional"))
    )
    (net (code "119") (name "Net-(R79-Pad1)") (class "Default")
      (node (ref "R79") (pin "1") (pinfunction "1_1") (pintype "passive"))
      (node (ref "U$25") (pin "ENA") (pinfunction "ENA_ENA") (pintype "bidirectional"))
    )
    (net (code "120") (name "Net-(R80-Pad1)") (class "Default")
      (node (ref "R80") (pin "1") (pinfunction "1_1") (pintype "passive"))
      (node (ref "U$25") (pin "OUT1") (pinfunction "OUT1_OUT1") (pintype "bidirectional"))
    )
    (net (code "121") (name "Net-(R82-Pad1)") (class "Default")
      (node (ref "R82") (pin "1") (pinfunction "1_1") (pintype "passive"))
      (node (ref "R84") (pin "2") (pinfunction "2_2") (pintype "passive"))
      (node (ref "R85") (pin "1") (pinfunction "1_1") (pintype "passive"))
      (node (ref "R88") (pin "1") (pinfunction "1_1") (pintype "passive"))
    )
    (net (code "122") (name "Net-(R87-Pad1)") (class "Default")
      (node (ref "R87") (pin "1") (pinfunction "1_1") (pintype "passive"))
      (node (ref "U$29") (pin "SIG") (pinfunction "SIG_SIG") (pintype "bidirectional"))
    )
    (net (code "123") (name "Net-(R88-Pad2)") (class "Default")
      (node (ref "R88") (pin "2") (pinfunction "2_2") (pintype "passive"))
      (node (ref "U$30") (pin "SIG") (pinfunction "SIG_SIG") (pintype "bidirectional"))
    )
    (net (code "124") (name "Net-(R123-Pad1)") (class "Default")
      (node (ref "R123") (pin "1") (pinfunction "1_1") (pintype "passive"))
      (node (ref "U$41") (pin "ENA") (pinfunction "ENA_ENA") (pintype "bidirectional"))
    )
    (net (code "125") (name "Net-(R124-Pad1)") (class "Default")
      (node (ref "R124") (pin "1") (pinfunction "1_1") (pintype "passive"))
      (node (ref "U$41") (pin "OUT1") (pinfunction "OUT1_OUT1") (pintype "bidirectional"))
    )
    (net (code "126") (name "Net-(R126-Pad1)") (class "Default")
      (node (ref "R126") (pin "1") (pinfunction "1_1") (pintype "passive"))
      (node (ref "R128") (pin "2") (pinfunction "2_2") (pintype "passive"))
      (node (ref "R129") (pin "1") (pinfunction "1_1") (pintype "passive"))
      (node (ref "R132") (pin "1") (pinfunction "1_1") (pintype "passive"))
    )
    (net (code "127") (name "Net-(R131-Pad1)") (class "Default")
      (node (ref "R131") (pin "1") (pinfunction "1_1") (pintype "passive"))
      (node (ref "U$45") (pin "SIG") (pinfunction "SIG_SIG") (pintype "bidirectional"))
    )
    (net (code "128") (name "Net-(R132-Pad2)") (class "Default")
      (node (ref "R132") (pin "2") (pinfunction "2_2") (pintype "passive"))
      (node (ref "U$46") (pin "SIG") (pinfunction "SIG_SIG") (pintype "bidirectional"))
    )
    (net (code "129") (name "Net-(U$12-ANT)") (class "Default")
      (node (ref "C43") (pin "2") (pinfunction "2_2") (pintype "passive"))
      (node (ref "R39") (pin "2") (pinfunction "2_2") (pintype "passive"))
      (node (ref "U$12") (pin "1") (pinfunction "P$1_1") (pintype "bidirectional"))
      (node (ref "U$12") (pin "10") (pinfunction "P$10_10") (pintype "bidirectional"))
      (node (ref "U$12") (pin "11") (pinfunction "P$11_11") (pintype "bidirectional"))
      (node (ref "U$12") (pin "12") (pinfunction "P$12_12") (pintype "bidirectional"))
      (node (ref "U$12") (pin "13") (pinfunction "P$13_13") (pintype "bidirectional"))
      (node (ref "U$12") (pin "14") (pinfunction "P$14_14") (pintype "bidirectional"))
      (node (ref "U$12") (pin "15") (pinfunction "P$15_15") (pintype "bidirectional"))
      (node (ref "U$12") (pin "16") (pinfunction "P$16_16") (pintype "bidirectional"))
      (node (ref "U$12") (pin "17") (pinfunction "P$17_17") (pintype "bidirectional"))
      (node (ref "U$12") (pin "18") (pinfunction "P$18_18") (pintype "bidirectional"))
      (node (ref "U$12") (pin "19") (pinfunction "P$19_19") (pintype "bidirectional"))
      (node (ref "U$12") (pin "2") (pinfunction "P$2_2") (pintype "bidirectional"))
      (node (ref "U$12") (pin "3") (pinfunction "P$3_3") (pintype "bidirectional"))
      (node (ref "U$12") (pin "4") (pinfunction "P$4_4") (pintype "bidirectional"))
      (node (ref "U$12") (pin "5") (pinfunction "P$5_5") (pintype "bidirectional"))
      (node (ref "U$12") (pin "6") (pinfunction "P$6_6") (pintype "bidirectional"))
      (node (ref "U$12") (pin "7") (pinfunction "P$7_7") (pintype "bidirectional"))
      (node (ref "U$12") (pin "8") (pinfunction "P$8_8") (pintype "bidirectional"))
      (node (ref "U$12") (pin "9") (pinfunction "P$9_9") (pintype "bidirectional"))
      (node (ref "U$12") (pin "ANTENNA") (pinfunction "ANT_ANTENNA") (pintype "bidirectional"))
    )
    (net (code "130") (name "Net-(U$15-LX)") (class "Default")
      (node (ref "L8") (pin "1") (pinfunction "1_1") (pintype "passive"))
      (node (ref "U$15") (pin "7") (pinfunction "LX_7") (pintype "bidirectional"))
    )
    (net (code "131") (name "Net-(U$15-SHDN)") (class "Default")
      (node (ref "R42") (pin "1") (pinfunction "1_1") (pintype "passive"))
      (node (ref "U$15") (pin "5") (pinfunction "SHDN_5") (pintype "bidirectional"))
    )
    (net (code "132") (name "Net-(U$20-ANT)") (class "Default")
      (node (ref "C66") (pin "2") (pinfunction "2_2") (pintype "passive"))
      (node (ref "R61") (pin "2") (pinfunction "2_2") (pintype "passive"))
      (node (ref "U$20") (pin "1") (pinfunction "P$1_1") (pintype "bidirectional"))
      (node (ref "U$20") (pin "10") (pinfunction "P$10_10") (pintype "bidirectional"))
      (node (ref "U$20") (pin "11") (pinfunction "P$11_11") (pintype "bidirectional"))
      (node (ref "U$20") (pin "12") (pinfunction "P$12_12") (pintype "bidirectional"))
      (node (ref "U$20") (pin "13") (pinfunction "P$13_13") (pintype "bidirectional"))
      (node (ref "U$20") (pin "14") (pinfunction "P$14_14") (pintype "bidirectional"))
      (node (ref "U$20") (pin "15") (pinfunction "P$15_15") (pintype "bidirectional"))
      (node (ref "U$20") (pin "16") (pinfunction "P$16_16") (pintype "bidirectional"))
      (node (ref "U$20") (pin "17") (pinfunction "P$17_17") (pintype "bidirectional"))
      (node (ref "U$20") (pin "18") (pinfunction "P$18_18") (pintype "bidirectional"))
      (node (ref "U$20") (pin "19") (pinfunction "P$19_19") (pintype "bidirectional"))
      (node (ref "U$20") (pin "2") (pinfunction "P$2_2") (pintype "bidirectional"))
      (node (ref "U$20") (pin "3") (pinfunction "P$3_3") (pintype "bidirectional"))
      (node (ref "U$20") (pin "4") (pinfunction "P$4_4") (pintype "bidirectional"))
      (node (ref "U$20") (pin "5") (pinfunction "P$5_5") (pintype "bidirectional"))
      (node (ref "U$20") (pin "6") (pinfunction "P$6_6") (pintype "bidirectional"))
      (node (ref "U$20") (pin "7") (pinfunction "P$7_7") (pintype "bidirectional"))
      (node (ref "U$20") (pin "8") (pinfunction "P$8_8") (pintype "bidirectional"))
      (node (ref "U$20") (pin "9") (pinfunction "P$9_9") (pintype "bidirectional"))
      (node (ref "U$20") (pin "ANTENNA") (pinfunction "ANT_ANTENNA") (pintype "bidirectional"))
    )
    (net (code "133") (name "Net-(U$23-LX)") (class "Default")
      (node (ref "L12") (pin "1") (pinfunction "1_1") (pintype "passive"))
      (node (ref "U$23") (pin "7") (pinfunction "LX_7") (pintype "bidirectional"))
    )
    (net (code "134") (name "Net-(U$23-SHDN)") (class "Default")
      (node (ref "R64") (pin "1") (pinfunction "1_1") (pintype "passive"))
      (node (ref "U$23") (pin "5") (pinfunction "SHDN_5") (pintype "bidirectional"))
    )
    (net (code "135") (name "Net-(U$28-ANT)") (class "Default")
      (node (ref "C89") (pin "2") (pinfunction "2_2") (pintype "passive"))
      (node (ref "R83") (pin "2") (pinfunction "2_2") (pintype "passive"))
      (node (ref "U$28") (pin "1") (pinfunction "P$1_1") (pintype "bidirectional"))
      (node (ref "U$28") (pin "10") (pinfunction "P$10_10") (pintype "bidirectional"))
      (node (ref "U$28") (pin "11") (pinfunction "P$11_11") (pintype "bidirectional"))
      (node (ref "U$28") (pin "12") (pinfunction "P$12_12") (pintype "bidirectional"))
      (node (ref "U$28") (pin "13") (pinfunction "P$13_13") (pintype "bidirectional"))
      (node (ref "U$28") (pin "14") (pinfunction "P$14_14") (pintype "bidirectional"))
      (node (ref "U$28") (pin "15") (pinfunction "P$15_15") (pintype "bidirectional"))
      (node (ref "U$28") (pin "16") (pinfunction "P$16_16") (pintype "bidirectional"))
      (node (ref "U$28") (pin "17") (pinfunction "P$17_17") (pintype "bidirectional"))
      (node (ref "U$28") (pin "18") (pinfunction "P$18_18") (pintype "bidirectional"))
      (node (ref "U$28") (pin "19") (pinfunction "P$19_19") (pintype "bidirectional"))
      (node (ref "U$28") (pin "2") (pinfunction "P$2_2") (pintype "bidirectional"))
      (node (ref "U$28") (pin "3") (pinfunction "P$3_3") (pintype "bidirectional"))
      (node (ref "U$28") (pin "4") (pinfunction "P$4_4") (pintype "bidirectional"))
      (node (ref "U$28") (pin "5") (pinfunction "P$5_5") (pintype "bidirectional"))
      (node (ref "U$28") (pin "6") (pinfunction "P$6_6") (pintype "bidirectional"))
      (node (ref "U$28") (pin "7") (pinfunction "P$7_7") (pintype "bidirectional"))
      (node (ref "U$28") (pin "8") (pinfunction "P$8_8") (pintype "bidirectional"))
      (node (ref "U$28") (pin "9") (pinfunction "P$9_9") (pintype "bidirectional"))
      (node (ref "U$28") (pin "ANTENNA") (pinfunction "ANT_ANTENNA") (pintype "bidirectional"))
    )
    (net (code "136") (name "Net-(U$31-LX)") (class "Default")
      (node (ref "L16") (pin "1") (pinfunction "1_1") (pintype "passive"))
      (node (ref "U$31") (pin "7") (pinfunction "LX_7") (pintype "bidirectional"))
    )
    (net (code "137") (name "Net-(U$31-SHDN)") (class "Default")
      (node (ref "R86") (pin "1") (pinfunction "1_1") (pintype "passive"))
      (node (ref "U$31") (pin "5") (pinfunction "SHDN_5") (pintype "bidirectional"))
    )
    (net (code "138") (name "Net-(U$44-ANT)") (class "Default")
      (node (ref "C135") (pin "2") (pinfunction "2_2") (pintype "passive"))
      (node (ref "R127") (pin "2") (pinfunction "2_2") (pintype "passive"))
      (node (ref "U$44") (pin "1") (pinfunction "P$1_1") (pintype "bidirectional"))
      (node (ref "U$44") (pin "10") (pinfunction "P$10_10") (pintype "bidirectional"))
      (node (ref "U$44") (pin "11") (pinfunction "P$11_11") (pintype "bidirectional"))
      (node (ref "U$44") (pin "12") (pinfunction "P$12_12") (pintype "bidirectional"))
      (node (ref "U$44") (pin "13") (pinfunction "P$13_13") (pintype "bidirectional"))
      (node (ref "U$44") (pin "14") (pinfunction "P$14_14") (pintype "bidirectional"))
      (node (ref "U$44") (pin "15") (pinfunction "P$15_15") (pintype "bidirectional"))
      (node (ref "U$44") (pin "16") (pinfunction "P$16_16") (pintype "bidirectional"))
      (node (ref "U$44") (pin "17") (pinfunction "P$17_17") (pintype "bidirectional"))
      (node (ref "U$44") (pin "18") (pinfunction "P$18_18") (pintype "bidirectional"))
      (node (ref "U$44") (pin "19") (pinfunction "P$19_19") (pintype "bidirectional"))
      (node (ref "U$44") (pin "2") (pinfunction "P$2_2") (pintype "bidirectional"))
      (node (ref "U$44") (pin "3") (pinfunction "P$3_3") (pintype "bidirectional"))
      (node (ref "U$44") (pin "4") (pinfunction "P$4_4") (pintype "bidirectional"))
      (node (ref "U$44") (pin "5") (pinfunction "P$5_5") (pintype "bidirectional"))
      (node (ref "U$44") (pin "6") (pinfunction "P$6_6") (pintype "bidirectional"))
      (node (ref "U$44") (pin "7") (pinfunction "P$7_7") (pintype "bidirectional"))
      (node (ref "U$44") (pin "8") (pinfunction "P$8_8") (pintype "bidirectional"))
      (node (ref "U$44") (pin "9") (pinfunction "P$9_9") (pintype "bidirectional"))
      (node (ref "U$44") (pin "ANTENNA") (pinfunction "ANT_ANTENNA") (pintype "bidirectional"))
    )
    (net (code "139") (name "Net-(U$47-LX)") (class "Default")
      (node (ref "L24") (pin "1") (pinfunction "1_1") (pintype "passive"))
      (node (ref "U$47") (pin "7") (pinfunction "LX_7") (pintype "bidirectional"))
    )
    (net (code "140") (name "Net-(U$47-SHDN)") (class "Default")
      (node (ref "R130") (pin "1") (pinfunction "1_1") (pintype "passive"))
      (node (ref "U$47") (pin "5") (pinfunction "SHDN_5") (pintype "bidirectional"))
    )
    (net (code "141") (name "unconnected-(GPS1-GPIO1{slash}RXD1-Pad3)") (class "Default")
      (node (ref "GPS1") (pin "3") (pinfunction "GPIO1/RXD1_3") (pintype "bidirectional"))
    )
    (net (code "142") (name "unconnected-(GPS1-GPIO2{slash}TXD1-Pad8)") (class "Default")
      (node (ref "GPS1") (pin "8") (pinfunction "GPIO2/TXD1_8") (pintype "bidirectional"))
    )
    (net (code "143") (name "unconnected-(GPS1-GPIO3{slash}P1PPS1-Pad40)") (class "Default")
      (node (ref "GPS1") (pin "40") (pinfunction "GPIO3/P1PPS1_40") (pintype "bidirectional"))
    )
    (net (code "144") (name "unconnected-(GPS1-GPIO4{slash}SCL-Pad37)") (class "Default")
      (node (ref "GPS1") (pin "37") (pinfunction "GPIO4/SCL_37") (pintype "bidirectional"))
    )
    (net (code "145") (name "unconnected-(GPS1-GPIO5{slash}SDA-Pad14)") (class "Default")
      (node (ref "GPS1") (pin "14") (pinfunction "GPIO5/SDA_14") (pintype "bidirectional"))
    )
    (net (code "146") (name "unconnected-(GPS1-GPIO6{slash}M_CSN2-Pad13)") (class "Default")
      (node (ref "GPS1") (pin "13") (pinfunction "GPIO6/M_CSN2_13") (pintype "bidirectional"))
    )
    (net (code "147") (name "unconnected-(GPS1-GPIO7{slash}P1PPS2-Pad12)") (class "Default")
      (node (ref "GPS1") (pin "12") (pinfunction "GPIO7/P1PPS2_12") (pintype "bidirectional"))
    )
    (net (code "148") (name "unconnected-(GPS1-GPIO8-Pad51)") (class "Default")
      (node (ref "GPS1") (pin "51") (pinfunction "GPIO8_51") (pintype "bidirectional"))
    )
    (net (code "149") (name "unconnected-(GPS1-GPIO9-Pad47)") (class "Default")
      (node (ref "GPS1") (pin "47") (pinfunction "GPIO9_47") (pintype "bidirectional"))
    )
    (net (code "150") (name "unconnected-(GPS1-GPIO10-Pad59)") (class "Default")
      (node (ref "GPS1") (pin "59") (pinfunction "GPIO10_59") (pintype "bidirectional"))
    )
    (net (code "151") (name "unconnected-(GPS1-GPIO11-Pad63)") (class "Default")
      (node (ref "GPS1") (pin "63") (pinfunction "GPIO11_63") (pintype "bidirectional"))
    )
    (net (code "152") (name "unconnected-(GPS1-GPIO12-Pad55)") (class "Default")
      (node (ref "GPS1") (pin "55") (pinfunction "GPIO12_55") (pintype "bidirectional"))
    )
    (net (code "153") (name "unconnected-(GPS1-GPIO13-Pad50)") (class "Default")
      (node (ref "GPS1") (pin "50") (pinfunction "GPIO13_50") (pintype "bidirectional"))
    )
    (net (code "154") (name "unconnected-(GPS1-GPIO14-Pad45)") (class "Default")
      (node (ref "GPS1") (pin "45") (pinfunction "GPIO14_45") (pintype "bidirectional"))
    )
    (net (code "155") (name "unconnected-(GPS1-GPIO15-Pad53)") (class "Default")
      (node (ref "GPS1") (pin "53") (pinfunction "GPIO15_53") (pintype "bidirectional"))
    )
    (net (code "156") (name "unconnected-(GPS1-GPIO16-Pad48)") (class "Default")
      (node (ref "GPS1") (pin "48") (pinfunction "GPIO16_48") (pintype "bidirectional"))
    )
    (net (code "157") (name "unconnected-(GPS1-GPIO20-Pad54)") (class "Default")
      (node (ref "GPS1") (pin "54") (pinfunction "GPIO20_54") (pintype "bidirectional"))
    )
    (net (code "158") (name "unconnected-(GPS1-GPIO21-Pad57)") (class "Default")
      (node (ref "GPS1") (pin "57") (pinfunction "GPIO21_57") (pintype "bidirectional"))
    )
    (net (code "159") (name "unconnected-(GPS1-GPIO22-Pad46)") (class "Default")
      (node (ref "GPS1") (pin "46") (pinfunction "GPIO22_46") (pintype "bidirectional"))
    )
    (net (code "160") (name "unconnected-(GPS1-GPIO23{slash}M_CSN0-Pad16)") (class "Default")
      (node (ref "GPS1") (pin "16") (pinfunction "GPIO23/M_CSN0_16") (pintype "bidirectional"))
    )
    (net (code "161") (name "unconnected-(GPS1-GPIO24{slash}M_SCK-Pad5)") (class "Default")
      (node (ref "GPS1") (pin "5") (pinfunction "GPIO24/M_SCK_5") (pintype "bidirectional"))
    )
    (net (code "162") (name "unconnected-(GPS1-GPIO25{slash}M_MISO-Pad4)") (class "Default")
      (node (ref "GPS1") (pin "4") (pinfunction "GPIO25/M_MISO_4") (pintype "bidirectional"))
    )
    (net (code "163") (name "unconnected-(GPS1-GPIO26{slash}M_MOSI-Pad6)") (class "Default")
      (node (ref "GPS1") (pin "6") (pinfunction "GPIO26/M_MOSI_6") (pintype "bidirectional"))
    )
    (net (code "164") (name "unconnected-(GPS1-GPIO27-Pad52)") (class "Default")
      (node (ref "GPS1") (pin "52") (pinfunction "GPIO27_52") (pintype "bidirectional"))
    )
    (net (code "165") (name "unconnected-(GPS1-GPIO28{slash}MS_CSN-Pad43)") (class "Default")
      (node (ref "GPS1") (pin "43") (pinfunction "GPIO28/MS_CSN_43") (pintype "bidirectional"))
    )
    (net (code "166") (name "unconnected-(GPS1-GPIO29{slash}MS_SCK-Pad41)") (class "Default")
      (node (ref "GPS1") (pin "41") (pinfunction "GPIO29/MS_SCK_41") (pintype "bidirectional"))
    )
    (net (code "167") (name "unconnected-(GPS1-GPIO30{slash}MS_MOSI-Pad38)") (class "Default")
      (node (ref "GPS1") (pin "38") (pinfunction "GPIO30/MS_MOSI_38") (pintype "bidirectional"))
    )
    (net (code "168") (name "unconnected-(GPS1-GPIO31{slash}MS_MISO-Pad39)") (class "Default")
      (node (ref "GPS1") (pin "39") (pinfunction "GPIO31/MS_MISO_39") (pintype "bidirectional"))
    )
    (net (code "169") (name "unconnected-(GPS1-NC-Pad17)") (class "Default")
      (node (ref "GPS1") (pin "17") (pinfunction "NC_17") (pintype "bidirectional"))
    )
    (net (code "170") (name "unconnected-(GPS1-NC-Pad20)") (class "Default")
      (node (ref "GPS1") (pin "20") (pinfunction "NC_20") (pintype "bidirectional"))
    )
    (net (code "171") (name "unconnected-(GPS1-NC-Pad23)") (class "Default")
      (node (ref "GPS1") (pin "23") (pinfunction "NC_23") (pintype "bidirectional"))
    )
    (net (code "172") (name "unconnected-(GPS1-NC-Pad26)") (class "Default")
      (node (ref "GPS1") (pin "26") (pinfunction "NC_26") (pintype "bidirectional"))
    )
    (net (code "173") (name "unconnected-(GPS1-NC-Pad30)") (class "Default")
      (node (ref "GPS1") (pin "30") (pinfunction "NC_30") (pintype "bidirectional"))
    )
    (net (code "174") (name "unconnected-(GPS1-NC-Pad34)") (class "Default")
      (node (ref "GPS1") (pin "34") (pinfunction "NC_34") (pintype "bidirectional"))
    )
    (net (code "175") (name "unconnected-(GPS1-NC-Pad35)") (class "Default")
      (node (ref "GPS1") (pin "35") (pinfunction "NC_35") (pintype "bidirectional"))
    )
    (net (code "176") (name "unconnected-(GPS1-NC-Pad36)") (class "Default")
      (node (ref "GPS1") (pin "36") (pinfunction "NC_36") (pintype "bidirectional"))
    )
    (net (code "177") (name "unconnected-(GPS1-NC-Pad56)") (class "Default")
      (node (ref "GPS1") (pin "56") (pinfunction "NC_56") (pintype "bidirectional"))
    )
    (net (code "178") (name "unconnected-(GPS1-NC-Pad66)") (class "Default")
      (node (ref "GPS1") (pin "66") (pinfunction "NC_66") (pintype "bidirectional"))
    )
    (net (code "179") (name "unconnected-(GPS1-NC-Pad67)") (class "Default")
      (node (ref "GPS1") (pin "67") (pinfunction "NC_67") (pintype "bidirectional"))
    )
    (net (code "180") (name "unconnected-(GPS1-NC-Pad68)") (class "Default")
      (node (ref "GPS1") (pin "68") (pinfunction "NC_68") (pintype "bidirectional"))
    )
    (net (code "181") (name "unconnected-(GPS2-GPIO1{slash}RXD1-Pad3)") (class "Default")
      (node (ref "GPS2") (pin "3") (pinfunction "GPIO1/RXD1_3") (pintype "bidirectional"))
    )
    (net (code "182") (name "unconnected-(GPS2-GPIO2{slash}TXD1-Pad8)") (class "Default")
      (node (ref "GPS2") (pin "8") (pinfunction "GPIO2/TXD1_8") (pintype "bidirectional"))
    )
    (net (code "183") (name "unconnected-(GPS2-GPIO3{slash}P1PPS1-Pad40)") (class "Default")
      (node (ref "GPS2") (pin "40") (pinfunction "GPIO3/P1PPS1_40") (pintype "bidirectional"))
    )
    (net (code "184") (name "unconnected-(GPS2-GPIO4{slash}SCL-Pad37)") (class "Default")
      (node (ref "GPS2") (pin "37") (pinfunction "GPIO4/SCL_37") (pintype "bidirectional"))
    )
    (net (code "185") (name "unconnected-(GPS2-GPIO5{slash}SDA-Pad14)") (class "Default")
      (node (ref "GPS2") (pin "14") (pinfunction "GPIO5/SDA_14") (pintype "bidirectional"))
    )
    (net (code "186") (name "unconnected-(GPS2-GPIO6{slash}M_CSN2-Pad13)") (class "Default")
      (node (ref "GPS2") (pin "13") (pinfunction "GPIO6/M_CSN2_13") (pintype "bidirectional"))
    )
    (net (code "187") (name "unconnected-(GPS2-GPIO7{slash}P1PPS2-Pad12)") (class "Default")
      (node (ref "GPS2") (pin "12") (pinfunction "GPIO7/P1PPS2_12") (pintype "bidirectional"))
    )
    (net (code "188") (name "unconnected-(GPS2-GPIO8-Pad51)") (class "Default")
      (node (ref "GPS2") (pin "51") (pinfunction "GPIO8_51") (pintype "bidirectional"))
    )
    (net (code "189") (name "unconnected-(GPS2-GPIO9-Pad47)") (class "Default")
      (node (ref "GPS2") (pin "47") (pinfunction "GPIO9_47") (pintype "bidirectional"))
    )
    (net (code "190") (name "unconnected-(GPS2-GPIO10-Pad59)") (class "Default")
      (node (ref "GPS2") (pin "59") (pinfunction "GPIO10_59") (pintype "bidirectional"))
    )
    (net (code "191") (name "unconnected-(GPS2-GPIO11-Pad63)") (class "Default")
      (node (ref "GPS2") (pin "63") (pinfunction "GPIO11_63") (pintype "bidirectional"))
    )
    (net (code "192") (name "unconnected-(GPS2-GPIO12-Pad55)") (class "Default")
      (node (ref "GPS2") (pin "55") (pinfunction "GPIO12_55") (pintype "bidirectional"))
    )
    (net (code "193") (name "unconnected-(GPS2-GPIO13-Pad50)") (class "Default")
      (node (ref "GPS2") (pin "50") (pinfunction "GPIO13_50") (pintype "bidirectional"))
    )
    (net (code "194") (name "unconnected-(GPS2-GPIO14-Pad45)") (class "Default")
      (node (ref "GPS2") (pin "45") (pinfunction "GPIO14_45") (pintype "bidirectional"))
    )
    (net (code "195") (name "unconnected-(GPS2-GPIO15-Pad53)") (class "Default")
      (node (ref "GPS2") (pin "53") (pinfunction "GPIO15_53") (pintype "bidirectional"))
    )
    (net (code "196") (name "unconnected-(GPS2-GPIO16-Pad48)") (class "Default")
      (node (ref "GPS2") (pin "48") (pinfunction "GPIO16_48") (pintype "bidirectional"))
    )
    (net (code "197") (name "unconnected-(GPS2-GPIO20-Pad54)") (class "Default")
      (node (ref "GPS2") (pin "54") (pinfunction "GPIO20_54") (pintype "bidirectional"))
    )
    (net (code "198") (name "unconnected-(GPS2-GPIO21-Pad57)") (class "Default")
      (node (ref "GPS2") (pin "57") (pinfunction "GPIO21_57") (pintype "bidirectional"))
    )
    (net (code "199") (name "unconnected-(GPS2-GPIO22-Pad46)") (class "Default")
      (node (ref "GPS2") (pin "46") (pinfunction "GPIO22_46") (pintype "bidirectional"))
    )
    (net (code "200") (name "unconnected-(GPS2-GPIO23{slash}M_CSN0-Pad16)") (class "Default")
      (node (ref "GPS2") (pin "16") (pinfunction "GPIO23/M_CSN0_16") (pintype "bidirectional"))
    )
    (net (code "201") (name "unconnected-(GPS2-GPIO24{slash}M_SCK-Pad5)") (class "Default")
      (node (ref "GPS2") (pin "5") (pinfunction "GPIO24/M_SCK_5") (pintype "bidirectional"))
    )
    (net (code "202") (name "unconnected-(GPS2-GPIO25{slash}M_MISO-Pad4)") (class "Default")
      (node (ref "GPS2") (pin "4") (pinfunction "GPIO25/M_MISO_4") (pintype "bidirectional"))
    )
    (net (code "203") (name "unconnected-(GPS2-GPIO26{slash}M_MOSI-Pad6)") (class "Default")
      (node (ref "GPS2") (pin "6") (pinfunction "GPIO26/M_MOSI_6") (pintype "bidirectional"))
    )
    (net (code "204") (name "unconnected-(GPS2-GPIO27-Pad52)") (class "Default")
      (node (ref "GPS2") (pin "52") (pinfunction "GPIO27_52") (pintype "bidirectional"))
    )
    (net (code "205") (name "unconnected-(GPS2-GPIO28{slash}MS_CSN-Pad43)") (class "Default")
      (node (ref "GPS2") (pin "43") (pinfunction "GPIO28/MS_CSN_43") (pintype "bidirectional"))
    )
    (net (code "206") (name "unconnected-(GPS2-GPIO29{slash}MS_SCK-Pad41)") (class "Default")
      (node (ref "GPS2") (pin "41") (pinfunction "GPIO29/MS_SCK_41") (pintype "bidirectional"))
    )
    (net (code "207") (name "unconnected-(GPS2-GPIO30{slash}MS_MOSI-Pad38)") (class "Default")
      (node (ref "GPS2") (pin "38") (pinfunction "GPIO30/MS_MOSI_38") (pintype "bidirectional"))
    )
    (net (code "208") (name "unconnected-(GPS2-GPIO31{slash}MS_MISO-Pad39)") (class "Default")
      (node (ref "GPS2") (pin "39") (pinfunction "GPIO31/MS_MISO_39") (pintype "bidirectional"))
    )
    (net (code "209") (name "unconnected-(GPS2-NC-Pad17)") (class "Default")
      (node (ref "GPS2") (pin "17") (pinfunction "NC_17") (pintype "bidirectional"))
    )
    (net (code "210") (name "unconnected-(GPS2-NC-Pad20)") (class "Default")
      (node (ref "GPS2") (pin "20") (pinfunction "NC_20") (pintype "bidirectional"))
    )
    (net (code "211") (name "unconnected-(GPS2-NC-Pad23)") (class "Default")
      (node (ref "GPS2") (pin "23") (pinfunction "NC_23") (pintype "bidirectional"))
    )
    (net (code "212") (name "unconnected-(GPS2-NC-Pad26)") (class "Default")
      (node (ref "GPS2") (pin "26") (pinfunction "NC_26") (pintype "bidirectional"))
    )
    (net (code "213") (name "unconnected-(GPS2-NC-Pad30)") (class "Default")
      (node (ref "GPS2") (pin "30") (pinfunction "NC_30") (pintype "bidirectional"))
    )
    (net (code "214") (name "unconnected-(GPS2-NC-Pad34)") (class "Default")
      (node (ref "GPS2") (pin "34") (pinfunction "NC_34") (pintype "bidirectional"))
    )
    (net (code "215") (name "unconnected-(GPS2-NC-Pad35)") (class "Default")
      (node (ref "GPS2") (pin "35") (pinfunction "NC_35") (pintype "bidirectional"))
    )
    (net (code "216") (name "unconnected-(GPS2-NC-Pad36)") (class "Default")
      (node (ref "GPS2") (pin "36") (pinfunction "NC_36") (pintype "bidirectional"))
    )
    (net (code "217") (name "unconnected-(GPS2-NC-Pad56)") (class "Default")
      (node (ref "GPS2") (pin "56") (pinfunction "NC_56") (pintype "bidirectional"))
    )
    (net (code "218") (name "unconnected-(GPS2-NC-Pad66)") (class "Default")
      (node (ref "GPS2") (pin "66") (pinfunction "NC_66") (pintype "bidirectional"))
    )
    (net (code "219") (name "unconnected-(GPS2-NC-Pad67)") (class "Default")
      (node (ref "GPS2") (pin "67") (pinfunction "NC_67") (pintype "bidirectional"))
    )
    (net (code "220") (name "unconnected-(GPS2-NC-Pad68)") (class "Default")
      (node (ref "GPS2") (pin "68") (pinfunction "NC_68") (pintype "bidirectional"))
    )
    (net (code "221") (name "unconnected-(GPS3-GPIO1{slash}RXD1-Pad3)") (class "Default")
      (node (ref "GPS3") (pin "3") (pinfunction "GPIO1/RXD1_3") (pintype "bidirectional"))
    )
    (net (code "222") (name "unconnected-(GPS3-GPIO2{slash}TXD1-Pad8)") (class "Default")
      (node (ref "GPS3") (pin "8") (pinfunction "GPIO2/TXD1_8") (pintype "bidirectional"))
    )
    (net (code "223") (name "unconnected-(GPS3-GPIO3{slash}P1PPS1-Pad40)") (class "Default")
      (node (ref "GPS3") (pin "40") (pinfunction "GPIO3/P1PPS1_40") (pintype "bidirectional"))
    )
    (net (code "224") (name "unconnected-(GPS3-GPIO4{slash}SCL-Pad37)") (class "Default")
      (node (ref "GPS3") (pin "37") (pinfunction "GPIO4/SCL_37") (pintype "bidirectional"))
    )
    (net (code "225") (name "unconnected-(GPS3-GPIO5{slash}SDA-Pad14)") (class "Default")
      (node (ref "GPS3") (pin "14") (pinfunction "GPIO5/SDA_14") (pintype "bidirectional"))
    )
    (net (code "226") (name "unconnected-(GPS3-GPIO6{slash}M_CSN2-Pad13)") (class "Default")
      (node (ref "GPS3") (pin "13") (pinfunction "GPIO6/M_CSN2_13") (pintype "bidirectional"))
    )
    (net (code "227") (name "unconnected-(GPS3-GPIO7{slash}P1PPS2-Pad12)") (class "Default")
      (node (ref "GPS3") (pin "12") (pinfunction "GPIO7/P1PPS2_12") (pintype "bidirectional"))
    )
    (net (code "228") (name "unconnected-(GPS3-GPIO8-Pad51)") (class "Default")
      (node (ref "GPS3") (pin "51") (pinfunction "GPIO8_51") (pintype "bidirectional"))
    )
    (net (code "229") (name "unconnected-(GPS3-GPIO9-Pad47)") (class "Default")
      (node (ref "GPS3") (pin "47") (pinfunction "GPIO9_47") (pintype "bidirectional"))
    )
    (net (code "230") (name "unconnected-(GPS3-GPIO10-Pad59)") (class "Default")
      (node (ref "GPS3") (pin "59") (pinfunction "GPIO10_59") (pintype "bidirectional"))
    )
    (net (code "231") (name "unconnected-(GPS3-GPIO11-Pad63)") (class "Default")
      (node (ref "GPS3") (pin "63") (pinfunction "GPIO11_63") (pintype "bidirectional"))
    )
    (net (code "232") (name "unconnected-(GPS3-GPIO12-Pad55)") (class "Default")
      (node (ref "GPS3") (pin "55") (pinfunction "GPIO12_55") (pintype "bidirectional"))
    )
    (net (code "233") (name "unconnected-(GPS3-GPIO13-Pad50)") (class "Default")
      (node (ref "GPS3") (pin "50") (pinfunction "GPIO13_50") (pintype "bidirectional"))
    )
    (net (code "234") (name "unconnected-(GPS3-GPIO14-Pad45)") (class "Default")
      (node (ref "GPS3") (pin "45") (pinfunction "GPIO14_45") (pintype "bidirectional"))
    )
    (net (code "235") (name "unconnected-(GPS3-GPIO15-Pad53)") (class "Default")
      (node (ref "GPS3") (pin "53") (pinfunction "GPIO15_53") (pintype "bidirectional"))
    )
    (net (code "236") (name "unconnected-(GPS3-GPIO16-Pad48)") (class "Default")
      (node (ref "GPS3") (pin "48") (pinfunction "GPIO16_48") (pintype "bidirectional"))
    )
    (net (code "237") (name "unconnected-(GPS3-GPIO20-Pad54)") (class "Default")
      (node (ref "GPS3") (pin "54") (pinfunction "GPIO20_54") (pintype "bidirectional"))
    )
    (net (code "238") (name "unconnected-(GPS3-GPIO21-Pad57)") (class "Default")
      (node (ref "GPS3") (pin "57") (pinfunction "GPIO21_57") (pintype "bidirectional"))
    )
    (net (code "239") (name "unconnected-(GPS3-GPIO22-Pad46)") (class "Default")
      (node (ref "GPS3") (pin "46") (pinfunction "GPIO22_46") (pintype "bidirectional"))
    )
    (net (code "240") (name "unconnected-(GPS3-GPIO23{slash}M_CSN0-Pad16)") (class "Default")
      (node (ref "GPS3") (pin "16") (pinfunction "GPIO23/M_CSN0_16") (pintype "bidirectional"))
    )
    (net (code "241") (name "unconnected-(GPS3-GPIO24{slash}M_SCK-Pad5)") (class "Default")
      (node (ref "GPS3") (pin "5") (pinfunction "GPIO24/M_SCK_5") (pintype "bidirectional"))
    )
    (net (code "242") (name "unconnected-(GPS3-GPIO25{slash}M_MISO-Pad4)") (class "Default")
      (node (ref "GPS3") (pin "4") (pinfunction "GPIO25/M_MISO_4") (pintype "bidirectional"))
    )
    (net (code "243") (name "unconnected-(GPS3-GPIO26{slash}M_MOSI-Pad6)") (class "Default")
      (node (ref "GPS3") (pin "6") (pinfunction "GPIO26/M_MOSI_6") (pintype "bidirectional"))
    )
    (net (code "244") (name "unconnected-(GPS3-GPIO27-Pad52)") (class "Default")
      (node (ref "GPS3") (pin "52") (pinfunction "GPIO27_52") (pintype "bidirectional"))
    )
    (net (code "245") (name "unconnected-(GPS3-GPIO28{slash}MS_CSN-Pad43)") (class "Default")
      (node (ref "GPS3") (pin "43") (pinfunction "GPIO28/MS_CSN_43") (pintype "bidirectional"))
    )
    (net (code "246") (name "unconnected-(GPS3-GPIO29{slash}MS_SCK-Pad41)") (class "Default")
      (node (ref "GPS3") (pin "41") (pinfunction "GPIO29/MS_SCK_41") (pintype "bidirectional"))
    )
    (net (code "247") (name "unconnected-(GPS3-GPIO30{slash}MS_MOSI-Pad38)") (class "Default")
      (node (ref "GPS3") (pin "38") (pinfunction "GPIO30/MS_MOSI_38") (pintype "bidirectional"))
    )
    (net (code "248") (name "unconnected-(GPS3-GPIO31{slash}MS_MISO-Pad39)") (class "Default")
      (node (ref "GPS3") (pin "39") (pinfunction "GPIO31/MS_MISO_39") (pintype "bidirectional"))
    )
    (net (code "249") (name "unconnected-(GPS3-NC-Pad17)") (class "Default")
      (node (ref "GPS3") (pin "17") (pinfunction "NC_17") (pintype "bidirectional"))
    )
    (net (code "250") (name "unconnected-(GPS3-NC-Pad20)") (class "Default")
      (node (ref "GPS3") (pin "20") (pinfunction "NC_20") (pintype "bidirectional"))
    )
    (net (code "251") (name "unconnected-(GPS3-NC-Pad23)") (class "Default")
      (node (ref "GPS3") (pin "23") (pinfunction "NC_23") (pintype "bidirectional"))
    )
    (net (code "252") (name "unconnected-(GPS3-NC-Pad26)") (class "Default")
      (node (ref "GPS3") (pin "26") (pinfunction "NC_26") (pintype "bidirectional"))
    )
    (net (code "253") (name "unconnected-(GPS3-NC-Pad30)") (class "Default")
      (node (ref "GPS3") (pin "30") (pinfunction "NC_30") (pintype "bidirectional"))
    )
    (net (code "254") (name "unconnected-(GPS3-NC-Pad34)") (class "Default")
      (node (ref "GPS3") (pin "34") (pinfunction "NC_34") (pintype "bidirectional"))
    )
    (net (code "255") (name "unconnected-(GPS3-NC-Pad35)") (class "Default")
      (node (ref "GPS3") (pin "35") (pinfunction "NC_35") (pintype "bidirectional"))
    )
    (net (code "256") (name "unconnected-(GPS3-NC-Pad36)") (class "Default")
      (node (ref "GPS3") (pin "36") (pinfunction "NC_36") (pintype "bidirectional"))
    )
    (net (code "257") (name "unconnected-(GPS3-NC-Pad56)") (class "Default")
      (node (ref "GPS3") (pin "56") (pinfunction "NC_56") (pintype "bidirectional"))
    )
    (net (code "258") (name "unconnected-(GPS3-NC-Pad66)") (class "Default")
      (node (ref "GPS3") (pin "66") (pinfunction "NC_66") (pintype "bidirectional"))
    )
    (net (code "259") (name "unconnected-(GPS3-NC-Pad67)") (class "Default")
      (node (ref "GPS3") (pin "67") (pinfunction "NC_67") (pintype "bidirectional"))
    )
    (net (code "260") (name "unconnected-(GPS3-NC-Pad68)") (class "Default")
      (node (ref "GPS3") (pin "68") (pinfunction "NC_68") (pintype "bidirectional"))
    )
    (net (code "261") (name "unconnected-(GPS5-GPIO1{slash}RXD1-Pad3)") (class "Default")
      (node (ref "GPS5") (pin "3") (pinfunction "GPIO1/RXD1_3") (pintype "bidirectional"))
    )
    (net (code "262") (name "unconnected-(GPS5-GPIO2{slash}TXD1-Pad8)") (class "Default")
      (node (ref "GPS5") (pin "8") (pinfunction "GPIO2/TXD1_8") (pintype "bidirectional"))
    )
    (net (code "263") (name "unconnected-(GPS5-GPIO3{slash}P1PPS1-Pad40)") (class "Default")
      (node (ref "GPS5") (pin "40") (pinfunction "GPIO3/P1PPS1_40") (pintype "bidirectional"))
    )
    (net (code "264") (name "unconnected-(GPS5-GPIO4{slash}SCL-Pad37)") (class "Default")
      (node (ref "GPS5") (pin "37") (pinfunction "GPIO4/SCL_37") (pintype "bidirectional"))
    )
    (net (code "265") (name "unconnected-(GPS5-GPIO5{slash}SDA-Pad14)") (class "Default")
      (node (ref "GPS5") (pin "14") (pinfunction "GPIO5/SDA_14") (pintype "bidirectional"))
    )
    (net (code "266") (name "unconnected-(GPS5-GPIO6{slash}M_CSN2-Pad13)") (class "Default")
      (node (ref "GPS5") (pin "13") (pinfunction "GPIO6/M_CSN2_13") (pintype "bidirectional"))
    )
    (net (code "267") (name "unconnected-(GPS5-GPIO7{slash}P1PPS2-Pad12)") (class "Default")
      (node (ref "GPS5") (pin "12") (pinfunction "GPIO7/P1PPS2_12") (pintype "bidirectional"))
    )
    (net (code "268") (name "unconnected-(GPS5-GPIO8-Pad51)") (class "Default")
      (node (ref "GPS5") (pin "51") (pinfunction "GPIO8_51") (pintype "bidirectional"))
    )
    (net (code "269") (name "unconnected-(GPS5-GPIO9-Pad47)") (class "Default")
      (node (ref "GPS5") (pin "47") (pinfunction "GPIO9_47") (pintype "bidirectional"))
    )
    (net (code "270") (name "unconnected-(GPS5-GPIO10-Pad59)") (class "Default")
      (node (ref "GPS5") (pin "59") (pinfunction "GPIO10_59") (pintype "bidirectional"))
    )
    (net (code "271") (name "unconnected-(GPS5-GPIO11-Pad63)") (class "Default")
      (node (ref "GPS5") (pin "63") (pinfunction "GPIO11_63") (pintype "bidirectional"))
    )
    (net (code "272") (name "unconnected-(GPS5-GPIO12-Pad55)") (class "Default")
      (node (ref "GPS5") (pin "55") (pinfunction "GPIO12_55") (pintype "bidirectional"))
    )
    (net (code "273") (name "unconnected-(GPS5-GPIO13-Pad50)") (class "Default")
      (node (ref "GPS5") (pin "50") (pinfunction "GPIO13_50") (pintype "bidirectional"))
    )
    (net (code "274") (name "unconnected-(GPS5-GPIO14-Pad45)") (class "Default")
      (node (ref "GPS5") (pin "45") (pinfunction "GPIO14_45") (pintype "bidirectional"))
    )
    (net (code "275") (name "unconnected-(GPS5-GPIO15-Pad53)") (class "Default")
      (node (ref "GPS5") (pin "53") (pinfunction "GPIO15_53") (pintype "bidirectional"))
    )
    (net (code "276") (name "unconnected-(GPS5-GPIO16-Pad48)") (class "Default")
      (node (ref "GPS5") (pin "48") (pinfunction "GPIO16_48") (pintype "bidirectional"))
    )
    (net (code "277") (name "unconnected-(GPS5-GPIO20-Pad54)") (class "Default")
      (node (ref "GPS5") (pin "54") (pinfunction "GPIO20_54") (pintype "bidirectional"))
    )
    (net (code "278") (name "unconnected-(GPS5-GPIO21-Pad57)") (class "Default")
      (node (ref "GPS5") (pin "57") (pinfunction "GPIO21_57") (pintype "bidirectional"))
    )
    (net (code "279") (name "unconnected-(GPS5-GPIO22-Pad46)") (class "Default")
      (node (ref "GPS5") (pin "46") (pinfunction "GPIO22_46") (pintype "bidirectional"))
    )
    (net (code "280") (name "unconnected-(GPS5-GPIO23{slash}M_CSN0-Pad16)") (class "Default")
      (node (ref "GPS5") (pin "16") (pinfunction "GPIO23/M_CSN0_16") (pintype "bidirectional"))
    )
    (net (code "281") (name "unconnected-(GPS5-GPIO24{slash}M_SCK-Pad5)") (class "Default")
      (node (ref "GPS5") (pin "5") (pinfunction "GPIO24/M_SCK_5") (pintype "bidirectional"))
    )
    (net (code "282") (name "unconnected-(GPS5-GPIO25{slash}M_MISO-Pad4)") (class "Default")
      (node (ref "GPS5") (pin "4") (pinfunction "GPIO25/M_MISO_4") (pintype "bidirectional"))
    )
    (net (code "283") (name "unconnected-(GPS5-GPIO26{slash}M_MOSI-Pad6)") (class "Default")
      (node (ref "GPS5") (pin "6") (pinfunction "GPIO26/M_MOSI_6") (pintype "bidirectional"))
    )
    (net (code "284") (name "unconnected-(GPS5-GPIO27-Pad52)") (class "Default")
      (node (ref "GPS5") (pin "52") (pinfunction "GPIO27_52") (pintype "bidirectional"))
    )
    (net (code "285") (name "unconnected-(GPS5-GPIO28{slash}MS_CSN-Pad43)") (class "Default")
      (node (ref "GPS5") (pin "43") (pinfunction "GPIO28/MS_CSN_43") (pintype "bidirectional"))
    )
    (net (code "286") (name "unconnected-(GPS5-GPIO29{slash}MS_SCK-Pad41)") (class "Default")
      (node (ref "GPS5") (pin "41") (pinfunction "GPIO29/MS_SCK_41") (pintype "bidirectional"))
    )
    (net (code "287") (name "unconnected-(GPS5-GPIO30{slash}MS_MOSI-Pad38)") (class "Default")
      (node (ref "GPS5") (pin "38") (pinfunction "GPIO30/MS_MOSI_38") (pintype "bidirectional"))
    )
    (net (code "288") (name "unconnected-(GPS5-GPIO31{slash}MS_MISO-Pad39)") (class "Default")
      (node (ref "GPS5") (pin "39") (pinfunction "GPIO31/MS_MISO_39") (pintype "bidirectional"))
    )
    (net (code "289") (name "unconnected-(GPS5-NC-Pad17)") (class "Default")
      (node (ref "GPS5") (pin "17") (pinfunction "NC_17") (pintype "bidirectional"))
    )
    (net (code "290") (name "unconnected-(GPS5-NC-Pad20)") (class "Default")
      (node (ref "GPS5") (pin "20") (pinfunction "NC_20") (pintype "bidirectional"))
    )
    (net (code "291") (name "unconnected-(GPS5-NC-Pad23)") (class "Default")
      (node (ref "GPS5") (pin "23") (pinfunction "NC_23") (pintype "bidirectional"))
    )
    (net (code "292") (name "unconnected-(GPS5-NC-Pad26)") (class "Default")
      (node (ref "GPS5") (pin "26") (pinfunction "NC_26") (pintype "bidirectional"))
    )
    (net (code "293") (name "unconnected-(GPS5-NC-Pad30)") (class "Default")
      (node (ref "GPS5") (pin "30") (pinfunction "NC_30") (pintype "bidirectional"))
    )
    (net (code "294") (name "unconnected-(GPS5-NC-Pad34)") (class "Default")
      (node (ref "GPS5") (pin "34") (pinfunction "NC_34") (pintype "bidirectional"))
    )
    (net (code "295") (name "unconnected-(GPS5-NC-Pad35)") (class "Default")
      (node (ref "GPS5") (pin "35") (pinfunction "NC_35") (pintype "bidirectional"))
    )
    (net (code "296") (name "unconnected-(GPS5-NC-Pad36)") (class "Default")
      (node (ref "GPS5") (pin "36") (pinfunction "NC_36") (pintype "bidirectional"))
    )
    (net (code "297") (name "unconnected-(GPS5-NC-Pad56)") (class "Default")
      (node (ref "GPS5") (pin "56") (pinfunction "NC_56") (pintype "bidirectional"))
    )
    (net (code "298") (name "unconnected-(GPS5-NC-Pad66)") (class "Default")
      (node (ref "GPS5") (pin "66") (pinfunction "NC_66") (pintype "bidirectional"))
    )
    (net (code "299") (name "unconnected-(GPS5-NC-Pad67)") (class "Default")
      (node (ref "GPS5") (pin "67") (pinfunction "NC_67") (pintype "bidirectional"))
    )
    (net (code "300") (name "unconnected-(GPS5-NC-Pad68)") (class "Default")
      (node (ref "GPS5") (pin "68") (pinfunction "NC_68") (pintype "bidirectional"))
    )
    (net (code "301") (name "unconnected-(IMU1-DEN_A{slash}G-Pad13)") (class "Default")
      (node (ref "IMU1") (pin "13") (pinfunction "DEN_A/G_13") (pintype "bidirectional"))
    )
    (net (code "302") (name "unconnected-(IMU1-INT_M-Pad10)") (class "Default")
      (node (ref "IMU1") (pin "10") (pinfunction "INT_M_10") (pintype "bidirectional"))
    )
    (net (code "303") (name "unconnected-(IMU2-DEN_A{slash}G-Pad13)") (class "Default")
      (node (ref "IMU2") (pin "13") (pinfunction "DEN_A/G_13") (pintype "bidirectional"))
    )
    (net (code "304") (name "unconnected-(IMU2-INT_M-Pad10)") (class "Default")
      (node (ref "IMU2") (pin "10") (pinfunction "INT_M_10") (pintype "bidirectional"))
    )
    (net (code "305") (name "unconnected-(IMU3-DEN_A{slash}G-Pad13)") (class "Default")
      (node (ref "IMU3") (pin "13") (pinfunction "DEN_A/G_13") (pintype "bidirectional"))
    )
    (net (code "306") (name "unconnected-(IMU3-INT_M-Pad10)") (class "Default")
      (node (ref "IMU3") (pin "10") (pinfunction "INT_M_10") (pintype "bidirectional"))
    )
    (net (code "307") (name "unconnected-(IMU5-DEN_A{slash}G-Pad13)") (class "Default")
      (node (ref "IMU5") (pin "13") (pinfunction "DEN_A/G_13") (pintype "bidirectional"))
    )
    (net (code "308") (name "unconnected-(IMU5-INT_M-Pad10)") (class "Default")
      (node (ref "IMU5") (pin "10") (pinfunction "INT_M_10") (pintype "bidirectional"))
    )
    (net (code "309") (name "unconnected-(MICROCONTROLLER1-Pad14)") (class "Default")
      (node (ref "MICROCONTROLLER1") (pin "14") (pinfunction "14_14") (pintype "bidirectional"))
    )
    (net (code "310") (name "unconnected-(MICROCONTROLLER1-Pad15)") (class "Default")
      (node (ref "MICROCONTROLLER1") (pin "15") (pinfunction "15_15") (pintype "bidirectional"))
    )
    (net (code "311") (name "unconnected-(MICROCONTROLLER1-Pad16)") (class "Default")
      (node (ref "MICROCONTROLLER1") (pin "16") (pinfunction "16_16") (pintype "bidirectional"))
    )
    (net (code "312") (name "unconnected-(MICROCONTROLLER1-Pad17)") (class "Default")
      (node (ref "MICROCONTROLLER1") (pin "17") (pinfunction "17_17") (pintype "bidirectional"))
    )
    (net (code "313") (name "unconnected-(MICROCONTROLLER1-Pad21)") (class "Default")
      (node (ref "MICROCONTROLLER1") (pin "21") (pinfunction "21_21") (pintype "bidirectional"))
    )
    (net (code "314") (name "unconnected-(MICROCONTROLLER1-Pad29)") (class "Default")
      (node (ref "MICROCONTROLLER1") (pin "29") (pinfunction "29_29") (pintype "bidirectional"))
    )
    (net (code "315") (name "unconnected-(MICROCONTROLLER1-Pad30)") (class "Default")
      (node (ref "MICROCONTROLLER1") (pin "30") (pinfunction "30_30") (pintype "bidirectional"))
    )
    (net (code "316") (name "unconnected-(MICROCONTROLLER1-Pad31)") (class "Default")
      (node (ref "MICROCONTROLLER1") (pin "31") (pinfunction "31_31") (pintype "bidirectional"))
    )
    (net (code "317") (name "unconnected-(MICROCONTROLLER1-Pad38)") (class "Default")
      (node (ref "MICROCONTROLLER1") (pin "38") (pinfunction "38_38") (pintype "bidirectional"))
    )
    (net (code "318") (name "unconnected-(MICROCONTROLLER1-Pad39)") (class "Default")
      (node (ref "MICROCONTROLLER1") (pin "39") (pinfunction "39_39") (pintype "input"))
    )
    (net (code "319") (name "unconnected-(MICROCONTROLLER1-Pad42)") (class "Default")
      (node (ref "MICROCONTROLLER1") (pin "42") (pinfunction "42_42") (pintype "bidirectional"))
    )
    (net (code "320") (name "unconnected-(MICROCONTROLLER1-Pad43)") (class "Default")
      (node (ref "MICROCONTROLLER1") (pin "43") (pinfunction "43_43") (pintype "bidirectional"))
    )
    (net (code "321") (name "unconnected-(MICROCONTROLLER2-Pad14)") (class "Default")
      (node (ref "MICROCONTROLLER2") (pin "14") (pinfunction "14_14") (pintype "bidirectional"))
    )
    (net (code "322") (name "unconnected-(MICROCONTROLLER2-Pad15)") (class "Default")
      (node (ref "MICROCONTROLLER2") (pin "15") (pinfunction "15_15") (pintype "bidirectional"))
    )
    (net (code "323") (name "unconnected-(MICROCONTROLLER2-Pad16)") (class "Default")
      (node (ref "MICROCONTROLLER2") (pin "16") (pinfunction "16_16") (pintype "bidirectional"))
    )
    (net (code "324") (name "unconnected-(MICROCONTROLLER2-Pad17)") (class "Default")
      (node (ref "MICROCONTROLLER2") (pin "17") (pinfunction "17_17") (pintype "bidirectional"))
    )
    (net (code "325") (name "unconnected-(MICROCONTROLLER2-Pad21)") (class "Default")
      (node (ref "MICROCONTROLLER2") (pin "21") (pinfunction "21_21") (pintype "bidirectional"))
    )
    (net (code "326") (name "unconnected-(MICROCONTROLLER2-Pad29)") (class "Default")
      (node (ref "MICROCONTROLLER2") (pin "29") (pinfunction "29_29") (pintype "bidirectional"))
    )
    (net (code "327") (name "unconnected-(MICROCONTROLLER2-Pad30)") (class "Default")
      (node (ref "MICROCONTROLLER2") (pin "30") (pinfunction "30_30") (pintype "bidirectional"))
    )
    (net (code "328") (name "unconnected-(MICROCONTROLLER2-Pad31)") (class "Default")
      (node (ref "MICROCONTROLLER2") (pin "31") (pinfunction "31_31") (pintype "bidirectional"))
    )
    (net (code "329") (name "unconnected-(MICROCONTROLLER2-Pad38)") (class "Default")
      (node (ref "MICROCONTROLLER2") (pin "38") (pinfunction "38_38") (pintype "bidirectional"))
    )
    (net (code "330") (name "unconnected-(MICROCONTROLLER2-Pad39)") (class "Default")
      (node (ref "MICROCONTROLLER2") (pin "39") (pinfunction "39_39") (pintype "input"))
    )
    (net (code "331") (name "unconnected-(MICROCONTROLLER2-Pad42)") (class "Default")
      (node (ref "MICROCONTROLLER2") (pin "42") (pinfunction "42_42") (pintype "bidirectional"))
    )
    (net (code "332") (name "unconnected-(MICROCONTROLLER2-Pad43)") (class "Default")
      (node (ref "MICROCONTROLLER2") (pin "43") (pinfunction "43_43") (pintype "bidirectional"))
    )
    (net (code "333") (name "unconnected-(MICROCONTROLLER3-Pad14)") (class "Default")
      (node (ref "MICROCONTROLLER3") (pin "14") (pinfunction "14_14") (pintype "bidirectional"))
    )
    (net (code "334") (name "unconnected-(MICROCONTROLLER3-Pad15)") (class "Default")
      (node (ref "MICROCONTROLLER3") (pin "15") (pinfunction "15_15") (pintype "bidirectional"))
    )
    (net (code "335") (name "unconnected-(MICROCONTROLLER3-Pad16)") (class "Default")
      (node (ref "MICROCONTROLLER3") (pin "16") (pinfunction "16_16") (pintype "bidirectional"))
    )
    (net (code "336") (name "unconnected-(MICROCONTROLLER3-Pad17)") (class "Default")
      (node (ref "MICROCONTROLLER3") (pin "17") (pinfunction "17_17") (pintype "bidirectional"))
    )
    (net (code "337") (name "unconnected-(MICROCONTROLLER3-Pad21)") (class "Default")
      (node (ref "MICROCONTROLLER3") (pin "21") (pinfunction "21_21") (pintype "bidirectional"))
    )
    (net (code "338") (name "unconnected-(MICROCONTROLLER3-Pad29)") (class "Default")
      (node (ref "MICROCONTROLLER3") (pin "29") (pinfunction "29_29") (pintype "bidirectional"))
    )
    (net (code "339") (name "unconnected-(MICROCONTROLLER3-Pad30)") (class "Default")
      (node (ref "MICROCONTROLLER3") (pin "30") (pinfunction "30_30") (pintype "bidirectional"))
    )
    (net (code "340") (name "unconnected-(MICROCONTROLLER3-Pad31)") (class "Default")
      (node (ref "MICROCONTROLLER3") (pin "31") (pinfunction "31_31") (pintype "bidirectional"))
    )
    (net (code "341") (name "unconnected-(MICROCONTROLLER3-Pad38)") (class "Default")
      (node (ref "MICROCONTROLLER3") (pin "38") (pinfunction "38_38") (pintype "bidirectional"))
    )
    (net (code "342") (name "unconnected-(MICROCONTROLLER3-Pad39)") (class "Default")
      (node (ref "MICROCONTROLLER3") (pin "39") (pinfunction "39_39") (pintype "input"))
    )
    (net (code "343") (name "unconnected-(MICROCONTROLLER3-Pad42)") (class "Default")
      (node (ref "MICROCONTROLLER3") (pin "42") (pinfunction "42_42") (pintype "bidirectional"))
    )
    (net (code "344") (name "unconnected-(MICROCONTROLLER3-Pad43)") (class "Default")
      (node (ref "MICROCONTROLLER3") (pin "43") (pinfunction "43_43") (pintype "bidirectional"))
    )
    (net (code "345") (name "unconnected-(MICROCONTROLLER5-Pad14)") (class "Default")
      (node (ref "MICROCONTROLLER5") (pin "14") (pinfunction "14_14") (pintype "bidirectional"))
    )
    (net (code "346") (name "unconnected-(MICROCONTROLLER5-Pad15)") (class "Default")
      (node (ref "MICROCONTROLLER5") (pin "15") (pinfunction "15_15") (pintype "bidirectional"))
    )
    (net (code "347") (name "unconnected-(MICROCONTROLLER5-Pad16)") (class "Default")
      (node (ref "MICROCONTROLLER5") (pin "16") (pinfunction "16_16") (pintype "bidirectional"))
    )
    (net (code "348") (name "unconnected-(MICROCONTROLLER5-Pad17)") (class "Default")
      (node (ref "MICROCONTROLLER5") (pin "17") (pinfunction "17_17") (pintype "bidirectional"))
    )
    (net (code "349") (name "unconnected-(MICROCONTROLLER5-Pad21)") (class "Default")
      (node (ref "MICROCONTROLLER5") (pin "21") (pinfunction "21_21") (pintype "bidirectional"))
    )
    (net (code "350") (name "unconnected-(MICROCONTROLLER5-Pad29)") (class "Default")
      (node (ref "MICROCONTROLLER5") (pin "29") (pinfunction "29_29") (pintype "bidirectional"))
    )
    (net (code "351") (name "unconnected-(MICROCONTROLLER5-Pad30)") (class "Default")
      (node (ref "MICROCONTROLLER5") (pin "30") (pinfunction "30_30") (pintype "bidirectional"))
    )
    (net (code "352") (name "unconnected-(MICROCONTROLLER5-Pad31)") (class "Default")
      (node (ref "MICROCONTROLLER5") (pin "31") (pinfunction "31_31") (pintype "bidirectional"))
    )
    (net (code "353") (name "unconnected-(MICROCONTROLLER5-Pad38)") (class "Default")
      (node (ref "MICROCONTROLLER5") (pin "38") (pinfunction "38_38") (pintype "bidirectional"))
    )
    (net (code "354") (name "unconnected-(MICROCONTROLLER5-Pad39)") (class "Default")
      (node (ref "MICROCONTROLLER5") (pin "39") (pinfunction "39_39") (pintype "input"))
    )
    (net (code "355") (name "unconnected-(MICROCONTROLLER5-Pad42)") (class "Default")
      (node (ref "MICROCONTROLLER5") (pin "42") (pinfunction "42_42") (pintype "bidirectional"))
    )
    (net (code "356") (name "unconnected-(MICROCONTROLLER5-Pad43)") (class "Default")
      (node (ref "MICROCONTROLLER5") (pin "43") (pinfunction "43_43") (pintype "bidirectional"))
    )
    (net (code "357") (name "unconnected-(U$10-PadNC)") (class "Default")
      (node (ref "U$10") (pin "NC") (pinfunction "NC_NC") (pintype "bidirectional"))
    )
    (net (code "358") (name "unconnected-(U$15-LBI-Pad2)") (class "Default")
      (node (ref "U$15") (pin "2") (pinfunction "LBI_2") (pintype "bidirectional"))
    )
    (net (code "359") (name "unconnected-(U$15-LBO-Pad3)") (class "Default")
      (node (ref "U$15") (pin "3") (pinfunction "LBO_3") (pintype "bidirectional"))
    )
    (net (code "360") (name "unconnected-(U$15-REF-Pad4)") (class "Default")
      (node (ref "U$15") (pin "4") (pinfunction "REF_4") (pintype "bidirectional"))
    )
    (net (code "361") (name "unconnected-(U$18-PadNC)") (class "Default")
      (node (ref "U$18") (pin "NC") (pinfunction "NC_NC") (pintype "bidirectional"))
    )
    (net (code "362") (name "unconnected-(U$23-LBI-Pad2)") (class "Default")
      (node (ref "U$23") (pin "2") (pinfunction "LBI_2") (pintype "bidirectional"))
    )
    (net (code "363") (name "unconnected-(U$23-LBO-Pad3)") (class "Default")
      (node (ref "U$23") (pin "3") (pinfunction "LBO_3") (pintype "bidirectional"))
    )
    (net (code "364") (name "unconnected-(U$23-REF-Pad4)") (class "Default")
      (node (ref "U$23") (pin "4") (pinfunction "REF_4") (pintype "bidirectional"))
    )
    (net (code "365") (name "unconnected-(U$26-PadNC)") (class "Default")
      (node (ref "U$26") (pin "NC") (pinfunction "NC_NC") (pintype "bidirectional"))
    )
    (net (code "366") (name "unconnected-(U$31-LBI-Pad2)") (class "Default")
      (node (ref "U$31") (pin "2") (pinfunction "LBI_2") (pintype "bidirectional"))
    )
    (net (code "367") (name "unconnected-(U$31-LBO-Pad3)") (class "Default")
      (node (ref "U$31") (pin "3") (pinfunction "LBO_3") (pintype "bidirectional"))
    )
    (net (code "368") (name "unconnected-(U$31-REF-Pad4)") (class "Default")
      (node (ref "U$31") (pin "4") (pinfunction "REF_4") (pintype "bidirectional"))
    )
    (net (code "369") (name "unconnected-(U$42-PadNC)") (class "Default")
      (node (ref "U$42") (pin "NC") (pinfunction "NC_NC") (pintype "bidirectional"))
    )
    (net (code "370") (name "unconnected-(U$47-LBI-Pad2)") (class "Default")
      (node (ref "U$47") (pin "2") (pinfunction "LBI_2") (pintype "bidirectional"))
    )
    (net (code "371") (name "unconnected-(U$47-LBO-Pad3)") (class "Default")
      (node (ref "U$47") (pin "3") (pinfunction "LBO_3") (pintype "bidirectional"))
    )
    (net (code "372") (name "unconnected-(U$47-REF-Pad4)") (class "Default")
      (node (ref "U$47") (pin "4") (pinfunction "REF_4") (pintype "bidirectional"))
    )
  )
)
